# rt1060r1.net
KiCad netlist of a schematic drawn in EAGLE
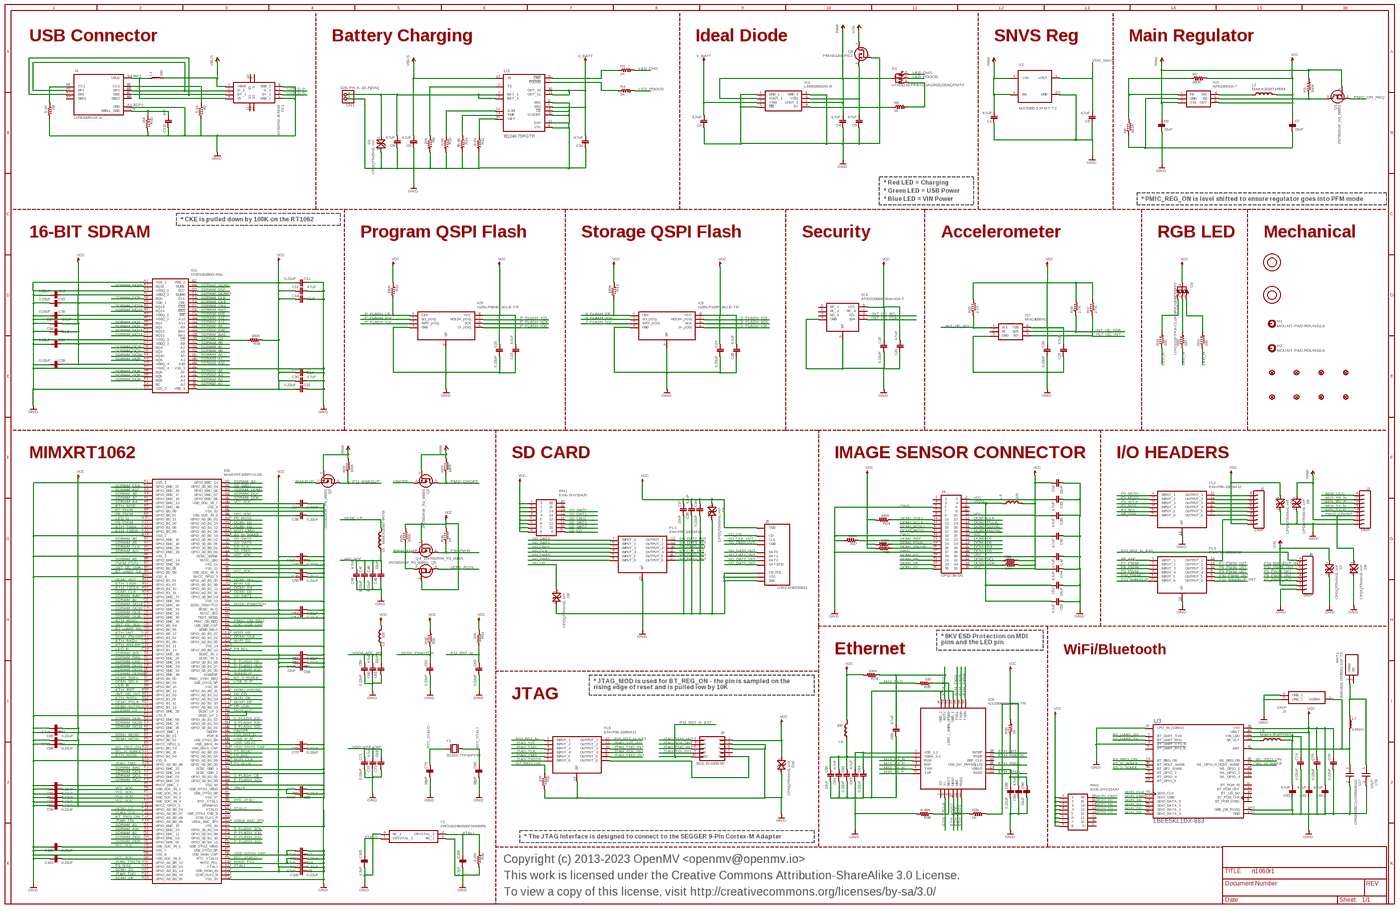
[diagram p0: schematic, sheet 1, overview]
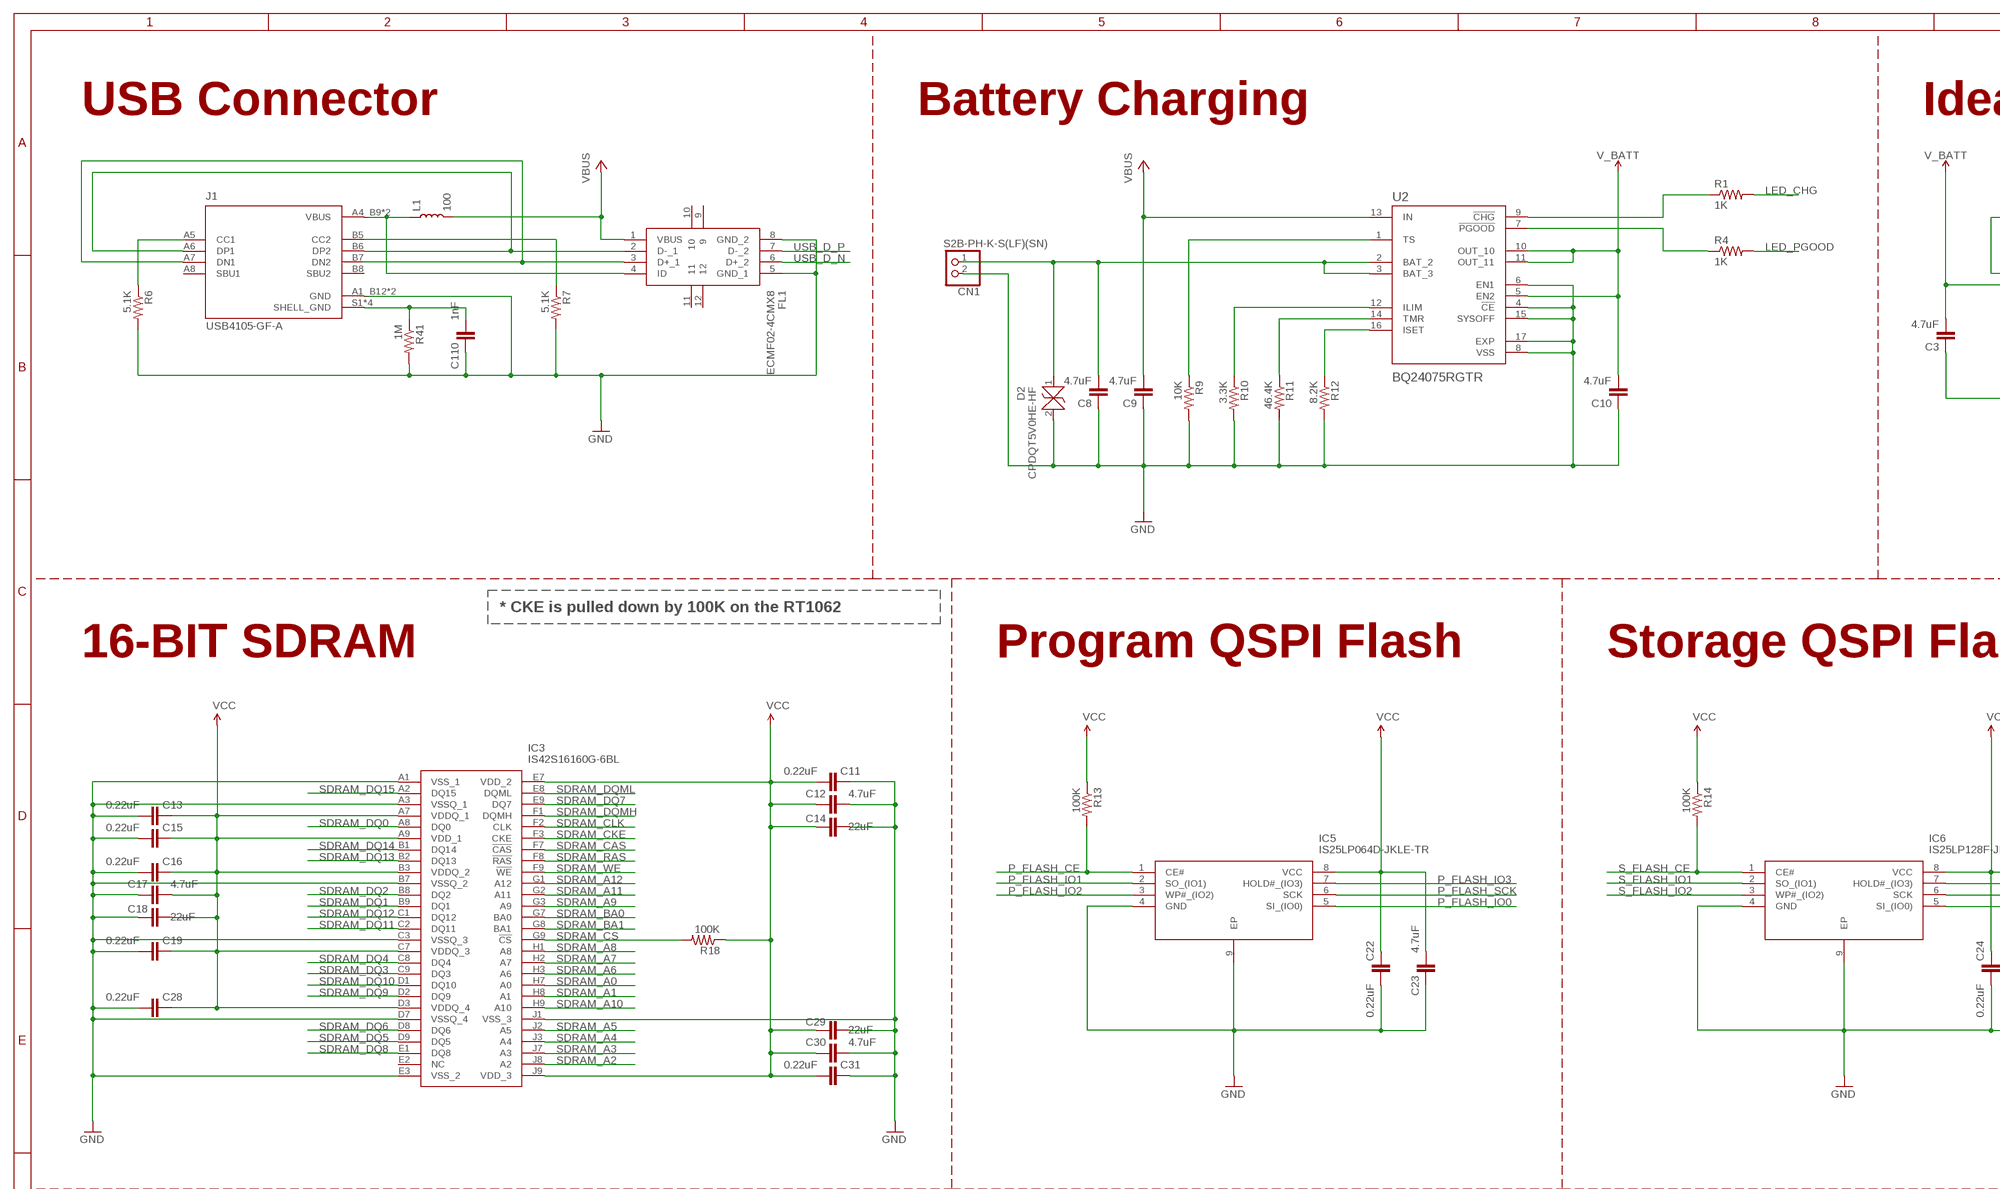
[diagram p1: schematic, sheet 1, part 1 of 4]
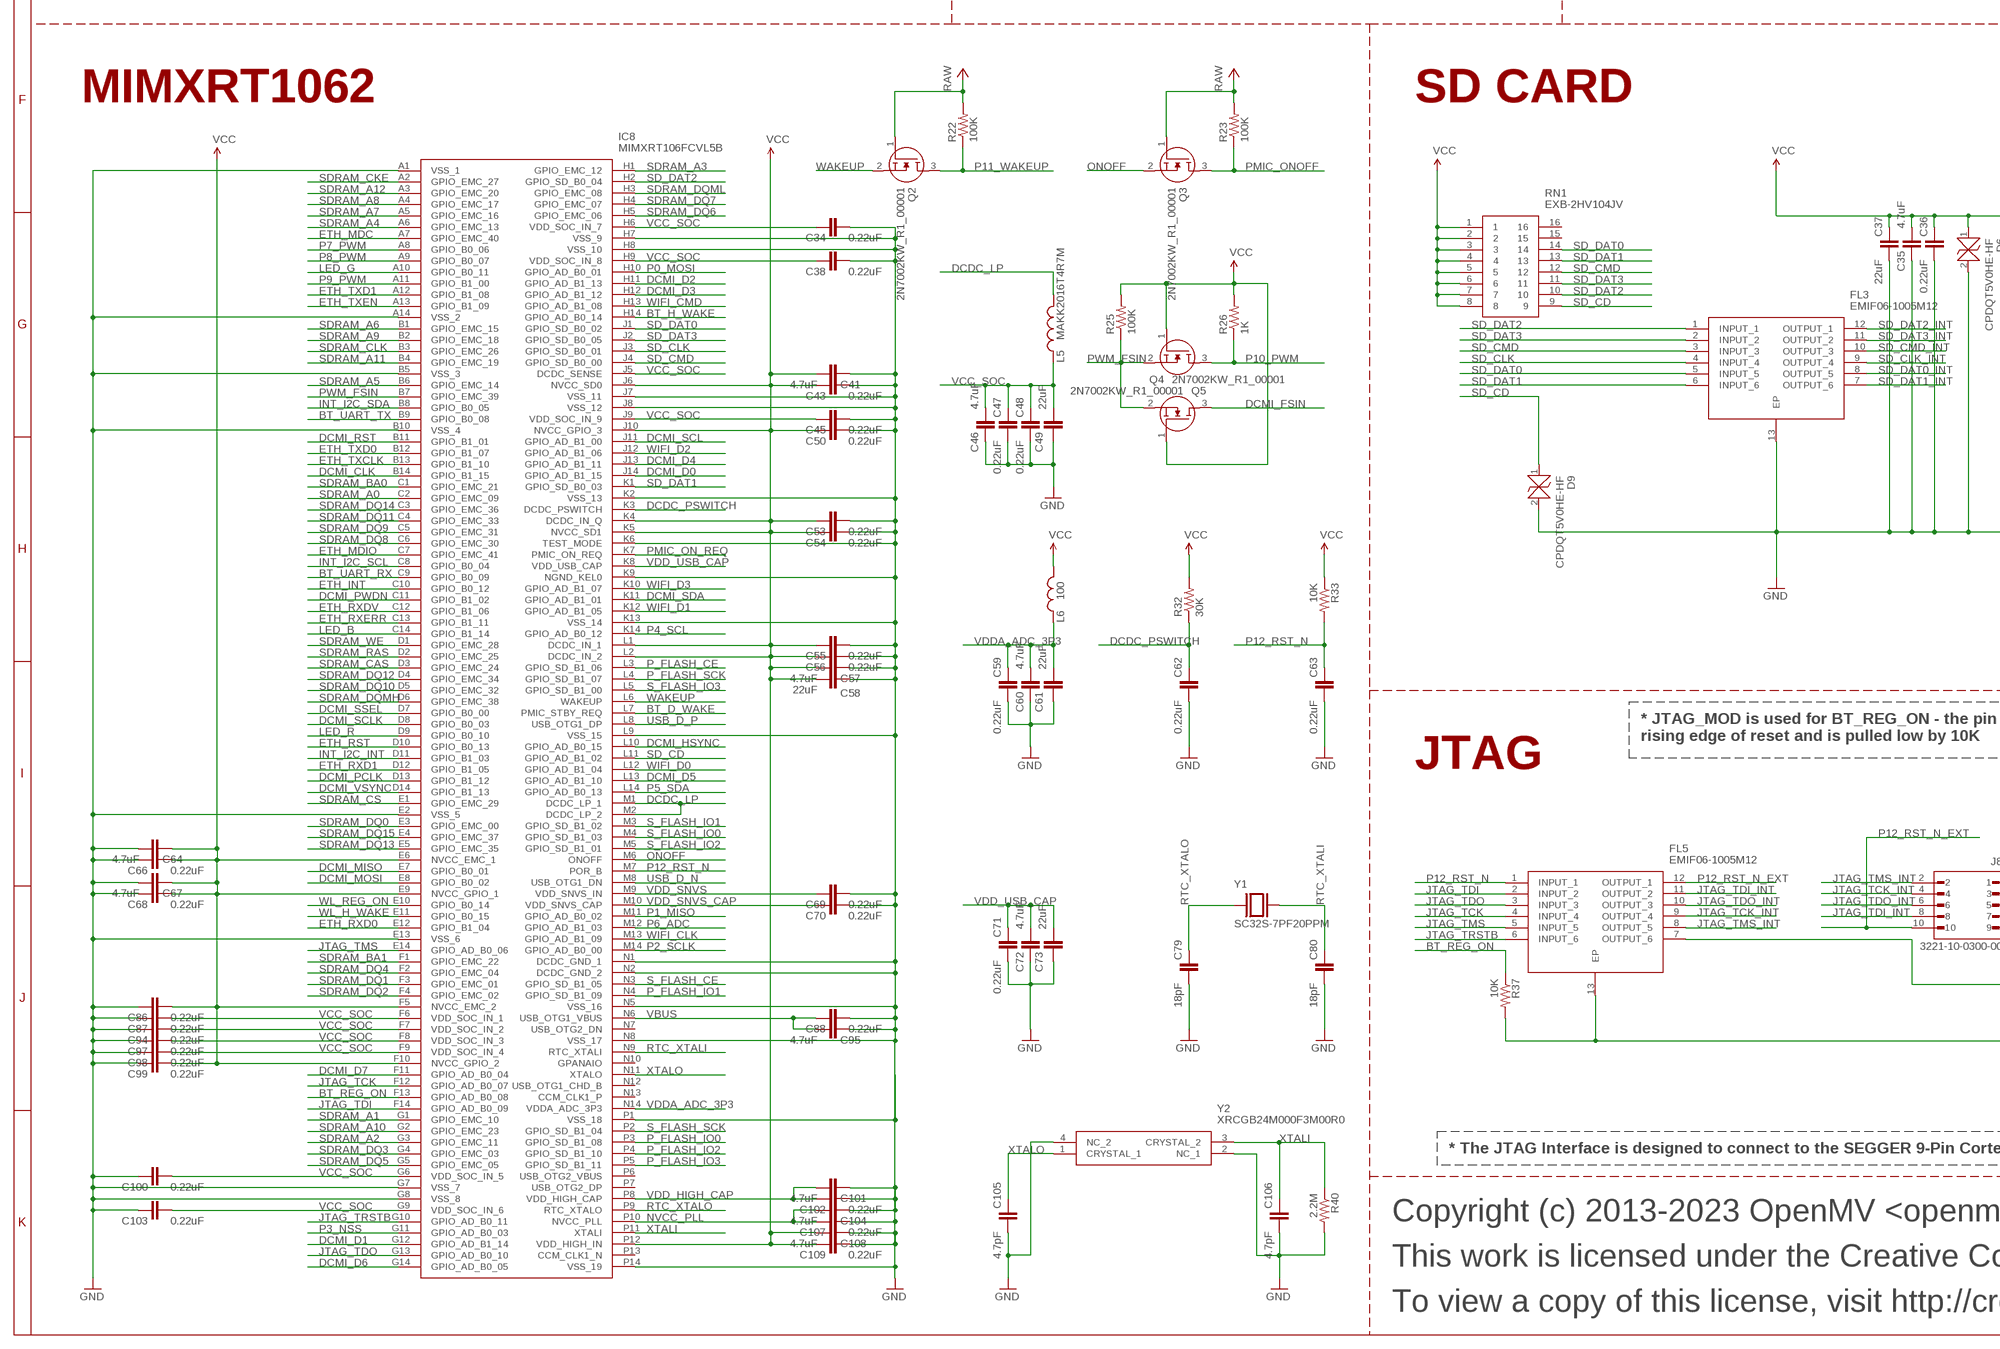
[diagram p2: schematic, sheet 1, part 2 of 4]
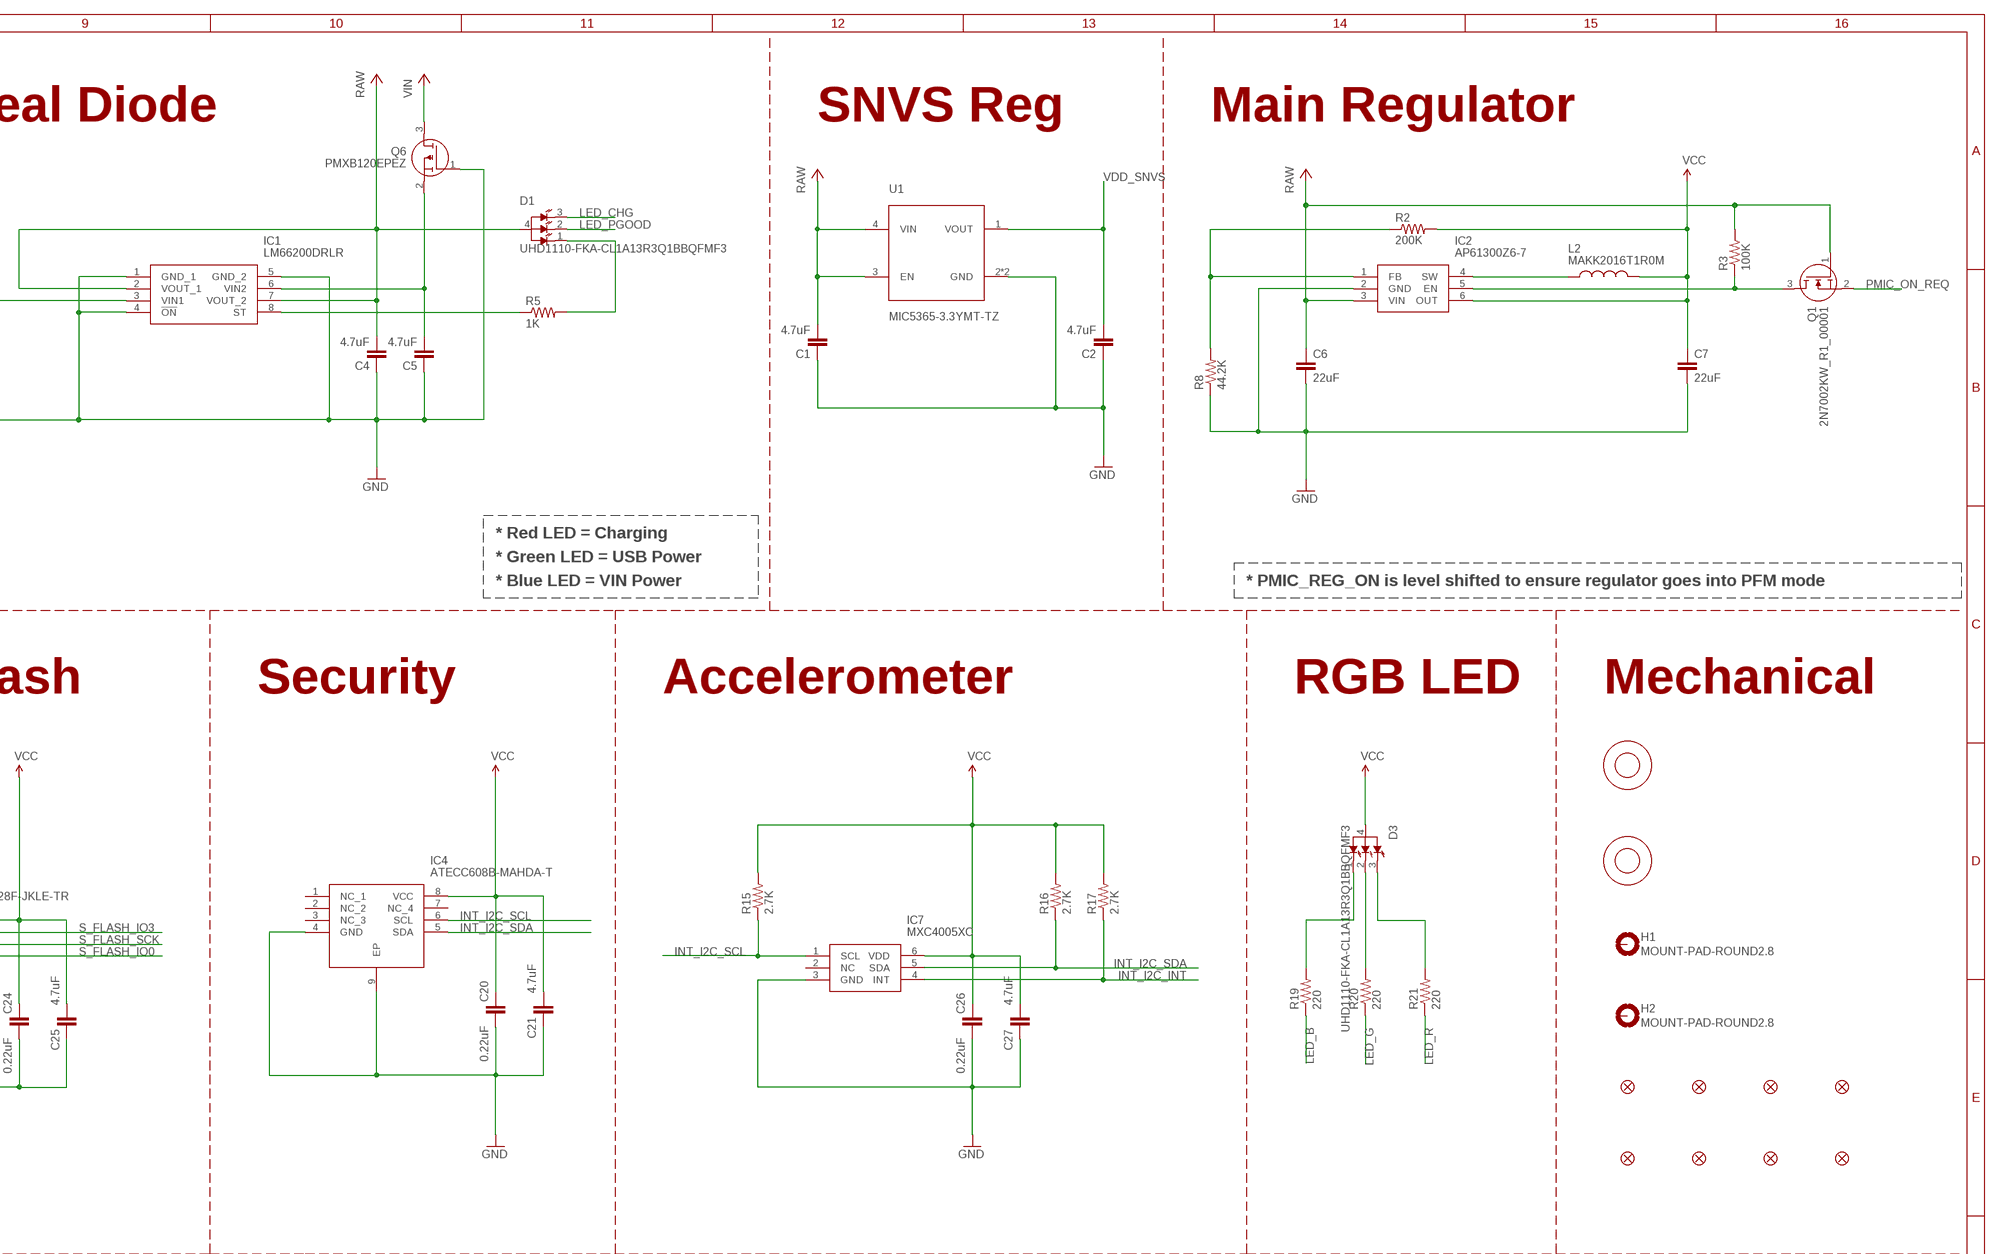
[diagram p3: schematic, sheet 1, part 3 of 4]
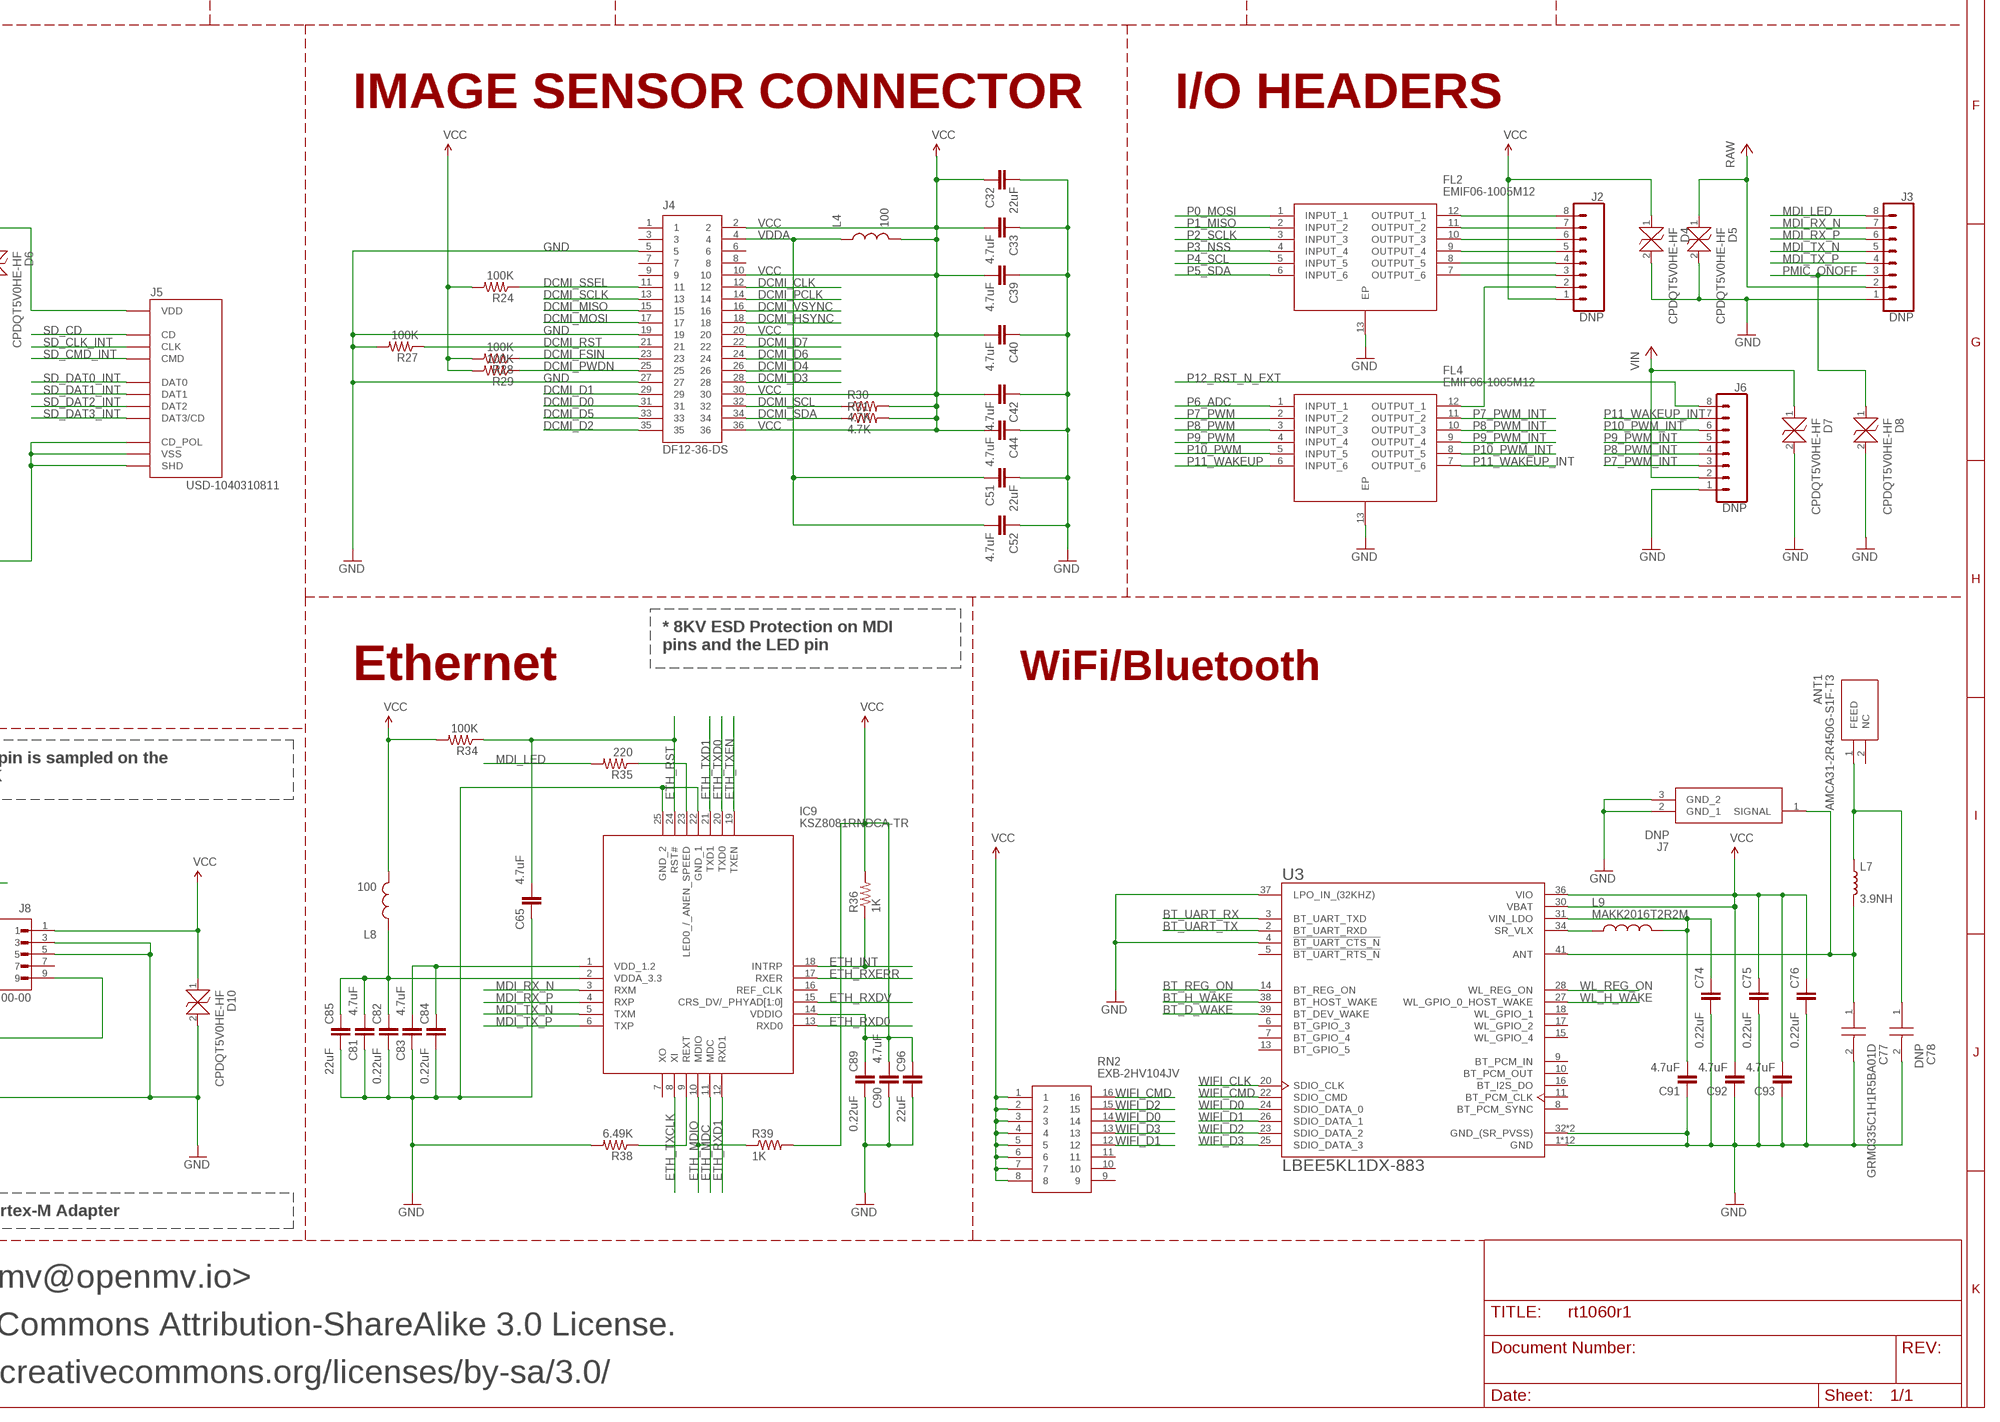
[diagram p4: schematic, sheet 1, part 4 of 4]

(export (version "E")
  (design (tool "Eeschema 10.0.6"))
  (components
    (comp (ref "ANT1")
      (value "AMCA31-2R450G-S1F-T3")
      (footprint "eagle-import:ANTC3216X140N")
      (fields (field (name "MOUSER_PART_NUMBER") "815-CA312R450GS1FT3"))
      (libsource (lib "eagle-import") (part "AMCA31-2R450G-S1F-T3"))
    )
    (comp (ref "C1")
      (value "4.7uF")
      (footprint "eagle-import:0402-CAP")
      (fields (field (name "MPN") "JMK105BBJ475MV-F"))
      (libsource (lib "eagle-import") (part "CAP0402-CAP"))
    )
    (comp (ref "C2")
      (value "4.7uF")
      (footprint "eagle-import:0402-CAP")
      (fields (field (name "MPN") "JMK105BBJ475MV-F"))
      (libsource (lib "eagle-import") (part "CAP0402-CAP"))
    )
    (comp (ref "C3")
      (value "4.7uF")
      (footprint "eagle-import:0402-CAP")
      (fields (field (name "MPN") "JMK105BBJ475MV-F"))
      (libsource (lib "eagle-import") (part "CAP0402-CAP"))
    )
    (comp (ref "C4")
      (value "4.7uF")
      (footprint "eagle-import:0402-CAP")
      (fields (field (name "MPN") "JMK105BBJ475MV-F"))
      (libsource (lib "eagle-import") (part "CAP0402-CAP"))
    )
    (comp (ref "C5")
      (value "4.7uF")
      (footprint "eagle-import:0402-CAP")
      (fields (field (name "MPN") "JMK105BBJ475MV-F"))
      (libsource (lib "eagle-import") (part "CAP0402-CAP"))
    )
    (comp (ref "C6")
      (value "22uF")
      (footprint "eagle-import:0805")
      (fields (field (name "MPN") "CL21A226MQQNNNE"))
      (libsource (lib "eagle-import") (part "22UF-0805-6.3V-20%"))
    )
    (comp (ref "C7")
      (value "22uF")
      (footprint "eagle-import:0805")
      (fields (field (name "MPN") "CL21A226MQQNNNE"))
      (libsource (lib "eagle-import") (part "22UF-0805-6.3V-20%"))
    )
    (comp (ref "C8")
      (value "4.7uF")
      (footprint "eagle-import:0402-CAP")
      (fields (field (name "MPN") "JMK105BBJ475MV-F"))
      (libsource (lib "eagle-import") (part "CAP0402-CAP"))
    )
    (comp (ref "C9")
      (value "4.7uF")
      (footprint "eagle-import:0402-CAP")
      (fields (field (name "MPN") "JMK105BBJ475MV-F"))
      (libsource (lib "eagle-import") (part "CAP0402-CAP"))
    )
    (comp (ref "C10")
      (value "4.7uF")
      (footprint "eagle-import:0402-CAP")
      (fields (field (name "MPN") "JMK105BBJ475MV-F"))
      (libsource (lib "eagle-import") (part "CAP0402-CAP"))
    )
    (comp (ref "C11")
      (value "0.22uF")
      (footprint "eagle-import:C0201")
      (fields (field (name "MPN") "GRM033R60J224ME15D"))
      (libsource (lib "eagle-import") (part "C-EUC0201"))
    )
    (comp (ref "C12")
      (value "4.7uF")
      (footprint "eagle-import:0402-CAP")
      (fields (field (name "MPN") "JMK105BBJ475MV-F"))
      (libsource (lib "eagle-import") (part "CAP0402-CAP"))
    )
    (comp (ref "C13")
      (value "0.22uF")
      (footprint "eagle-import:C0201")
      (fields (field (name "MPN") "GRM033R60J224ME15D"))
      (libsource (lib "eagle-import") (part "C-EUC0201"))
    )
    (comp (ref "C14")
      (value "22uF")
      (footprint "eagle-import:0805")
      (fields (field (name "MPN") "CL21A226MQQNNNE"))
      (libsource (lib "eagle-import") (part "22UF-0805-6.3V-20%"))
    )
    (comp (ref "C15")
      (value "0.22uF")
      (footprint "eagle-import:C0201")
      (fields (field (name "MPN") "GRM033R60J224ME15D"))
      (libsource (lib "eagle-import") (part "C-EUC0201"))
    )
    (comp (ref "C16")
      (value "0.22uF")
      (footprint "eagle-import:C0201")
      (fields (field (name "MPN") "GRM033R60J224ME15D"))
      (libsource (lib "eagle-import") (part "C-EUC0201"))
    )
    (comp (ref "C17")
      (value "4.7uF")
      (footprint "eagle-import:0402-CAP")
      (fields (field (name "MPN") "JMK105BBJ475MV-F"))
      (libsource (lib "eagle-import") (part "CAP0402-CAP"))
    )
    (comp (ref "C18")
      (value "22uF")
      (footprint "eagle-import:0805")
      (fields (field (name "MPN") "CL21A226MQQNNNE"))
      (libsource (lib "eagle-import") (part "22UF-0805-6.3V-20%"))
    )
    (comp (ref "C19")
      (value "0.22uF")
      (footprint "eagle-import:C0201")
      (fields (field (name "MPN") "GRM033R60J224ME15D"))
      (libsource (lib "eagle-import") (part "C-EUC0201"))
    )
    (comp (ref "C20")
      (value "0.22uF")
      (footprint "eagle-import:C0201")
      (fields (field (name "MPN") "GRM033R60J224ME15D"))
      (libsource (lib "eagle-import") (part "C-EUC0201"))
    )
    (comp (ref "C21")
      (value "4.7uF")
      (footprint "eagle-import:0402-CAP")
      (fields (field (name "MPN") "JMK105BBJ475MV-F"))
      (libsource (lib "eagle-import") (part "CAP0402-CAP"))
    )
    (comp (ref "C22")
      (value "0.22uF")
      (footprint "eagle-import:C0201")
      (fields (field (name "MPN") "GRM033R60J224ME15D"))
      (libsource (lib "eagle-import") (part "C-EUC0201"))
    )
    (comp (ref "C23")
      (value "4.7uF")
      (footprint "eagle-import:0402-CAP")
      (fields (field (name "MPN") "JMK105BBJ475MV-F"))
      (libsource (lib "eagle-import") (part "CAP0402-CAP"))
    )
    (comp (ref "C24")
      (value "0.22uF")
      (footprint "eagle-import:C0201")
      (fields (field (name "MPN") "GRM033R60J224ME15D"))
      (libsource (lib "eagle-import") (part "C-EUC0201"))
    )
    (comp (ref "C25")
      (value "4.7uF")
      (footprint "eagle-import:0402-CAP")
      (fields (field (name "MPN") "JMK105BBJ475MV-F"))
      (libsource (lib "eagle-import") (part "CAP0402-CAP"))
    )
    (comp (ref "C26")
      (value "0.22uF")
      (footprint "eagle-import:C0201")
      (fields (field (name "MPN") "GRM033R60J224ME15D"))
      (libsource (lib "eagle-import") (part "C-EUC0201"))
    )
    (comp (ref "C27")
      (value "4.7uF")
      (footprint "eagle-import:0402-CAP")
      (fields (field (name "MPN") "JMK105BBJ475MV-F"))
      (libsource (lib "eagle-import") (part "CAP0402-CAP"))
    )
    (comp (ref "C28")
      (value "0.22uF")
      (footprint "eagle-import:C0201")
      (fields (field (name "MPN") "GRM033R60J224ME15D"))
      (libsource (lib "eagle-import") (part "C-EUC0201"))
    )
    (comp (ref "C29")
      (value "22uF")
      (footprint "eagle-import:0805")
      (fields (field (name "MPN") "CL21A226MQQNNNE"))
      (libsource (lib "eagle-import") (part "22UF-0805-6.3V-20%"))
    )
    (comp (ref "C30")
      (value "4.7uF")
      (footprint "eagle-import:0402-CAP")
      (fields (field (name "MPN") "JMK105BBJ475MV-F"))
      (libsource (lib "eagle-import") (part "CAP0402-CAP"))
    )
    (comp (ref "C31")
      (value "0.22uF")
      (footprint "eagle-import:C0201")
      (fields (field (name "MPN") "GRM033R60J224ME15D"))
      (libsource (lib "eagle-import") (part "C-EUC0201"))
    )
    (comp (ref "C32")
      (value "22uF")
      (footprint "eagle-import:0805")
      (fields (field (name "MPN") "CL21A226MQQNNNE"))
      (libsource (lib "eagle-import") (part "22UF-0805-6.3V-20%"))
    )
    (comp (ref "C33")
      (value "4.7uF")
      (footprint "eagle-import:0402-CAP")
      (fields (field (name "MPN") "JMK105BBJ475MV-F"))
      (libsource (lib "eagle-import") (part "CAP0402-CAP"))
    )
    (comp (ref "C34")
      (value "0.22uF")
      (footprint "eagle-import:C0201")
      (fields (field (name "MPN") "GRM033R60J224ME15D"))
      (libsource (lib "eagle-import") (part "C-EUC0201"))
    )
    (comp (ref "C35")
      (value "4.7uF")
      (footprint "eagle-import:0402-CAP")
      (fields (field (name "MPN") "JMK105BBJ475MV-F"))
      (libsource (lib "eagle-import") (part "CAP0402-CAP"))
    )
    (comp (ref "C36")
      (value "0.22uF")
      (footprint "eagle-import:C0201")
      (fields (field (name "MPN") "GRM033R60J224ME15D"))
      (libsource (lib "eagle-import") (part "C-EUC0201"))
    )
    (comp (ref "C37")
      (value "22uF")
      (footprint "eagle-import:0805")
      (fields (field (name "MPN") "CL21A226MQQNNNE"))
      (libsource (lib "eagle-import") (part "22UF-0805-6.3V-20%"))
    )
    (comp (ref "C38")
      (value "0.22uF")
      (footprint "eagle-import:C0201")
      (fields (field (name "MPN") "GRM033R60J224ME15D"))
      (libsource (lib "eagle-import") (part "C-EUC0201"))
    )
    (comp (ref "C39")
      (value "4.7uF")
      (footprint "eagle-import:0402-CAP")
      (fields (field (name "MPN") "JMK105BBJ475MV-F"))
      (libsource (lib "eagle-import") (part "CAP0402-CAP"))
    )
    (comp (ref "C40")
      (value "4.7uF")
      (footprint "eagle-import:0402-CAP")
      (fields (field (name "MPN") "JMK105BBJ475MV-F"))
      (libsource (lib "eagle-import") (part "CAP0402-CAP"))
    )
    (comp (ref "C41")
      (value "4.7uF")
      (footprint "eagle-import:0402-CAP")
      (fields (field (name "MPN") "JMK105BBJ475MV-F"))
      (libsource (lib "eagle-import") (part "CAP0402-CAP"))
    )
    (comp (ref "C42")
      (value "4.7uF")
      (footprint "eagle-import:0402-CAP")
      (fields (field (name "MPN") "JMK105BBJ475MV-F"))
      (libsource (lib "eagle-import") (part "CAP0402-CAP"))
    )
    (comp (ref "C43")
      (value "0.22uF")
      (footprint "eagle-import:C0201")
      (fields (field (name "MPN") "GRM033R60J224ME15D"))
      (libsource (lib "eagle-import") (part "C-EUC0201"))
    )
    (comp (ref "C44")
      (value "4.7uF")
      (footprint "eagle-import:0402-CAP")
      (fields (field (name "MPN") "JMK105BBJ475MV-F"))
      (libsource (lib "eagle-import") (part "CAP0402-CAP"))
    )
    (comp (ref "C45")
      (value "0.22uF")
      (footprint "eagle-import:C0201")
      (fields (field (name "MPN") "GRM033R60J224ME15D"))
      (libsource (lib "eagle-import") (part "C-EUC0201"))
    )
    (comp (ref "C46")
      (value "4.7uF")
      (footprint "eagle-import:0402-CAP")
      (fields (field (name "MPN") "JMK105BBJ475MV-F"))
      (libsource (lib "eagle-import") (part "CAP0402-CAP"))
    )
    (comp (ref "C47")
      (value "0.22uF")
      (footprint "eagle-import:C0201")
      (fields (field (name "MPN") "GRM033R60J224ME15D"))
      (libsource (lib "eagle-import") (part "C-EUC0201"))
    )
    (comp (ref "C48")
      (value "0.22uF")
      (footprint "eagle-import:C0201")
      (fields (field (name "MPN") "GRM033R60J224ME15D"))
      (libsource (lib "eagle-import") (part "C-EUC0201"))
    )
    (comp (ref "C49")
      (value "22uF")
      (footprint "eagle-import:0805")
      (fields (field (name "MPN") "CL21A226MQQNNNE"))
      (libsource (lib "eagle-import") (part "22UF-0805-6.3V-20%"))
    )
    (comp (ref "C50")
      (value "0.22uF")
      (footprint "eagle-import:C0201")
      (fields (field (name "MPN") "GRM033R60J224ME15D"))
      (libsource (lib "eagle-import") (part "C-EUC0201"))
    )
    (comp (ref "C51")
      (value "22uF")
      (footprint "eagle-import:0805")
      (fields (field (name "MPN") "CL21A226MQQNNNE"))
      (libsource (lib "eagle-import") (part "22UF-0805-6.3V-20%"))
    )
    (comp (ref "C52")
      (value "4.7uF")
      (footprint "eagle-import:0402-CAP")
      (fields (field (name "MPN") "JMK105BBJ475MV-F"))
      (libsource (lib "eagle-import") (part "CAP0402-CAP"))
    )
    (comp (ref "C53")
      (value "0.22uF")
      (footprint "eagle-import:C0201")
      (fields (field (name "MPN") "GRM033R60J224ME15D"))
      (libsource (lib "eagle-import") (part "C-EUC0201"))
    )
    (comp (ref "C54")
      (value "0.22uF")
      (footprint "eagle-import:C0201")
      (fields (field (name "MPN") "GRM033R60J224ME15D"))
      (libsource (lib "eagle-import") (part "C-EUC0201"))
    )
    (comp (ref "C55")
      (value "0.22uF")
      (footprint "eagle-import:C0201")
      (fields (field (name "MPN") "GRM033R60J224ME15D"))
      (libsource (lib "eagle-import") (part "C-EUC0201"))
    )
    (comp (ref "C56")
      (value "0.22uF")
      (footprint "eagle-import:C0201")
      (fields (field (name "MPN") "GRM033R60J224ME15D"))
      (libsource (lib "eagle-import") (part "C-EUC0201"))
    )
    (comp (ref "C57")
      (value "4.7uF")
      (footprint "eagle-import:0402-CAP")
      (fields (field (name "MPN") "JMK105BBJ475MV-F"))
      (libsource (lib "eagle-import") (part "CAP0402-CAP"))
    )
    (comp (ref "C58")
      (value "22uF")
      (footprint "eagle-import:0805")
      (fields (field (name "MPN") "CL21A226MQQNNNE"))
      (libsource (lib "eagle-import") (part "22UF-0805-6.3V-20%"))
    )
    (comp (ref "C59")
      (value "0.22uF")
      (footprint "eagle-import:C0201")
      (fields (field (name "MPN") "GRM033R60J224ME15D"))
      (libsource (lib "eagle-import") (part "C-EUC0201"))
    )
    (comp (ref "C60")
      (value "4.7uF")
      (footprint "eagle-import:0402-CAP")
      (fields (field (name "MPN") "JMK105BBJ475MV-F"))
      (libsource (lib "eagle-import") (part "CAP0402-CAP"))
    )
    (comp (ref "C61")
      (value "22uF")
      (footprint "eagle-import:0805")
      (fields (field (name "MPN") "CL21A226MQQNNNE"))
      (libsource (lib "eagle-import") (part "22UF-0805-6.3V-20%"))
    )
    (comp (ref "C62")
      (value "0.22uF")
      (footprint "eagle-import:C0201")
      (fields (field (name "MPN") "GRM033R60J224ME15D"))
      (libsource (lib "eagle-import") (part "C-EUC0201"))
    )
    (comp (ref "C63")
      (value "0.22uF")
      (footprint "eagle-import:C0201")
      (fields (field (name "MPN") "GRM033R60J224ME15D"))
      (libsource (lib "eagle-import") (part "C-EUC0201"))
    )
    (comp (ref "C64")
      (value "4.7uF")
      (footprint "eagle-import:0402-CAP")
      (fields (field (name "MPN") "JMK105BBJ475MV-F"))
      (libsource (lib "eagle-import") (part "CAP0402-CAP"))
    )
    (comp (ref "C65")
      (value "4.7uF")
      (footprint "eagle-import:0402-CAP")
      (fields (field (name "MPN") "JMK105BBJ475MV-F"))
      (libsource (lib "eagle-import") (part "CAP0402-CAP"))
    )
    (comp (ref "C66")
      (value "0.22uF")
      (footprint "eagle-import:C0201")
      (fields (field (name "MPN") "GRM033R60J224ME15D"))
      (libsource (lib "eagle-import") (part "C-EUC0201"))
    )
    (comp (ref "C67")
      (value "4.7uF")
      (footprint "eagle-import:0402-CAP")
      (fields (field (name "MPN") "JMK105BBJ475MV-F"))
      (libsource (lib "eagle-import") (part "CAP0402-CAP"))
    )
    (comp (ref "C68")
      (value "0.22uF")
      (footprint "eagle-import:C0201")
      (fields (field (name "MPN") "GRM033R60J224ME15D"))
      (libsource (lib "eagle-import") (part "C-EUC0201"))
    )
    (comp (ref "C69")
      (value "0.22uF")
      (footprint "eagle-import:C0201")
      (fields (field (name "MPN") "GRM033R60J224ME15D"))
      (libsource (lib "eagle-import") (part "C-EUC0201"))
    )
    (comp (ref "C70")
      (value "0.22uF")
      (footprint "eagle-import:C0201")
      (fields (field (name "MPN") "GRM033R60J224ME15D"))
      (libsource (lib "eagle-import") (part "C-EUC0201"))
    )
    (comp (ref "C71")
      (value "0.22uF")
      (footprint "eagle-import:C0201")
      (fields (field (name "MPN") "GRM033R60J224ME15D"))
      (libsource (lib "eagle-import") (part "C-EUC0201"))
    )
    (comp (ref "C72")
      (value "4.7uF")
      (footprint "eagle-import:0402-CAP")
      (fields (field (name "MPN") "JMK105BBJ475MV-F"))
      (libsource (lib "eagle-import") (part "CAP0402-CAP"))
    )
    (comp (ref "C73")
      (value "22uF")
      (footprint "eagle-import:0805")
      (fields (field (name "MPN") "CL21A226MQQNNNE"))
      (libsource (lib "eagle-import") (part "22UF-0805-6.3V-20%"))
    )
    (comp (ref "C74")
      (value "0.22uF")
      (footprint "eagle-import:C0201")
      (fields (field (name "MPN") "GRM033R60J224ME15D"))
      (libsource (lib "eagle-import") (part "C-EUC0201"))
    )
    (comp (ref "C75")
      (value "0.22uF")
      (footprint "eagle-import:C0201")
      (fields (field (name "MPN") "GRM033R60J224ME15D"))
      (libsource (lib "eagle-import") (part "C-EUC0201"))
    )
    (comp (ref "C76")
      (value "0.22uF")
      (footprint "eagle-import:C0201")
      (fields (field (name "MPN") "GRM033R60J224ME15D"))
      (libsource (lib "eagle-import") (part "C-EUC0201"))
    )
    (comp (ref "C77")
      (value "GRM0335C1H1R5BA01D")
      (footprint "eagle-import:CAPC0603X33N")
      (fields (field (name "MOUSER_PART_NUMBER") "81-GRM0335C1H1R5BA1D"))
      (libsource (lib "eagle-import") (part "GRM0335C1H1R5BA01D"))
    )
    (comp (ref "C78")
      (value "DNP")
      (footprint "eagle-import:CAPC0603X33N")
      (fields
        (field (name "MANUFACTURER_PART_NUMBER") "GRM0335C1H1R5BA01D")
        (field (name "MOUSER_PART_NUMBER") "81-GRM0335C1H1R5BA1D")
      )
      (libsource (lib "eagle-import") (part "GRM0335C1H1R5BA01D"))
    )
    (comp (ref "C79")
      (value "18pF")
      (footprint "eagle-import:C0201")
      (fields (field (name "MPN") "GRM0335C1E180JA01D"))
      (libsource (lib "eagle-import") (part "C-EUC0201"))
    )
    (comp (ref "C80")
      (value "18pF")
      (footprint "eagle-import:C0201")
      (fields (field (name "MPN") "GRM0335C1E180JA01D"))
      (libsource (lib "eagle-import") (part "C-EUC0201"))
    )
    (comp (ref "C81")
      (value "4.7uF")
      (footprint "eagle-import:0402-CAP")
      (fields (field (name "MPN") "JMK105BBJ475MV-F"))
      (libsource (lib "eagle-import") (part "CAP0402-CAP"))
    )
    (comp (ref "C82")
      (value "0.22uF")
      (footprint "eagle-import:C0201")
      (fields (field (name "MPN") "GRM033R60J224ME15D"))
      (libsource (lib "eagle-import") (part "C-EUC0201"))
    )
    (comp (ref "C83")
      (value "4.7uF")
      (footprint "eagle-import:0402-CAP")
      (fields (field (name "MPN") "JMK105BBJ475MV-F"))
      (libsource (lib "eagle-import") (part "CAP0402-CAP"))
    )
    (comp (ref "C84")
      (value "0.22uF")
      (footprint "eagle-import:C0201")
      (fields (field (name "MPN") "GRM033R60J224ME15D"))
      (libsource (lib "eagle-import") (part "C-EUC0201"))
    )
    (comp (ref "C85")
      (value "22uF")
      (footprint "eagle-import:0805")
      (fields (field (name "MPN") "CL21A226MQQNNNE"))
      (libsource (lib "eagle-import") (part "22UF-0805-6.3V-20%"))
    )
    (comp (ref "C86")
      (value "0.22uF")
      (footprint "eagle-import:C0201")
      (fields (field (name "MPN") "GRM033R60J224ME15D"))
      (libsource (lib "eagle-import") (part "C-EUC0201"))
    )
    (comp (ref "C87")
      (value "0.22uF")
      (footprint "eagle-import:C0201")
      (fields (field (name "MPN") "GRM033R60J224ME15D"))
      (libsource (lib "eagle-import") (part "C-EUC0201"))
    )
    (comp (ref "C88")
      (value "0.22uF")
      (footprint "eagle-import:C0201")
      (fields (field (name "MPN") "GRM033R60J224ME15D"))
      (libsource (lib "eagle-import") (part "C-EUC0201"))
    )
    (comp (ref "C89")
      (value "0.22uF")
      (footprint "eagle-import:C0201")
      (fields (field (name "MPN") "GRM033R60J224ME15D"))
      (libsource (lib "eagle-import") (part "C-EUC0201"))
    )
    (comp (ref "C90")
      (value "4.7uF")
      (footprint "eagle-import:0402-CAP")
      (fields (field (name "MPN") "JMK105BBJ475MV-F"))
      (libsource (lib "eagle-import") (part "CAP0402-CAP"))
    )
    (comp (ref "C91")
      (value "4.7uF")
      (footprint "eagle-import:0402-CAP")
      (fields (field (name "MPN") "JMK105BBJ475MV-F"))
      (libsource (lib "eagle-import") (part "CAP0402-CAP"))
    )
    (comp (ref "C92")
      (value "4.7uF")
      (footprint "eagle-import:0402-CAP")
      (fields (field (name "MPN") "JMK105BBJ475MV-F"))
      (libsource (lib "eagle-import") (part "CAP0402-CAP"))
    )
    (comp (ref "C93")
      (value "4.7uF")
      (footprint "eagle-import:0402-CAP")
      (fields (field (name "MPN") "JMK105BBJ475MV-F"))
      (libsource (lib "eagle-import") (part "CAP0402-CAP"))
    )
    (comp (ref "C94")
      (value "0.22uF")
      (footprint "eagle-import:C0201")
      (fields (field (name "MPN") "GRM033R60J224ME15D"))
      (libsource (lib "eagle-import") (part "C-EUC0201"))
    )
    (comp (ref "C95")
      (value "4.7uF")
      (footprint "eagle-import:0402-CAP")
      (fields (field (name "MPN") "JMK105BBJ475MV-F"))
      (libsource (lib "eagle-import") (part "CAP0402-CAP"))
    )
    (comp (ref "C96")
      (value "22uF")
      (footprint "eagle-import:0805")
      (fields (field (name "MPN") "CL21A226MQQNNNE"))
      (libsource (lib "eagle-import") (part "22UF-0805-6.3V-20%"))
    )
    (comp (ref "C97")
      (value "0.22uF")
      (footprint "eagle-import:C0201")
      (fields (field (name "MPN") "GRM033R60J224ME15D"))
      (libsource (lib "eagle-import") (part "C-EUC0201"))
    )
    (comp (ref "C98")
      (value "0.22uF")
      (footprint "eagle-import:C0201")
      (fields (field (name "MPN") "GRM033R60J224ME15D"))
      (libsource (lib "eagle-import") (part "C-EUC0201"))
    )
    (comp (ref "C99")
      (value "0.22uF")
      (footprint "eagle-import:C0201")
      (fields (field (name "MPN") "GRM033R60J224ME15D"))
      (libsource (lib "eagle-import") (part "C-EUC0201"))
    )
    (comp (ref "C100")
      (value "0.22uF")
      (footprint "eagle-import:C0201")
      (fields (field (name "MPN") "GRM033R60J224ME15D"))
      (libsource (lib "eagle-import") (part "C-EUC0201"))
    )
    (comp (ref "C101")
      (value "4.7uF")
      (footprint "eagle-import:0402-CAP")
      (fields (field (name "MPN") "JMK105BBJ475MV-F"))
      (libsource (lib "eagle-import") (part "CAP0402-CAP"))
    )
    (comp (ref "C102")
      (value "0.22uF")
      (footprint "eagle-import:C0201")
      (fields (field (name "MPN") "GRM033R60J224ME15D"))
      (libsource (lib "eagle-import") (part "C-EUC0201"))
    )
    (comp (ref "C103")
      (value "0.22uF")
      (footprint "eagle-import:C0201")
      (fields (field (name "MPN") "GRM033R60J224ME15D"))
      (libsource (lib "eagle-import") (part "C-EUC0201"))
    )
    (comp (ref "C104")
      (value "4.7uF")
      (footprint "eagle-import:0402-CAP")
      (fields (field (name "MPN") "JMK105BBJ475MV-F"))
      (libsource (lib "eagle-import") (part "CAP0402-CAP"))
    )
    (comp (ref "C105")
      (value "4.7pF")
      (footprint "eagle-import:C0201")
      (fields (field (name "MPN") "GRM0335C1E4R7CA01D"))
      (libsource (lib "eagle-import") (part "C-EUC0201"))
    )
    (comp (ref "C106")
      (value "4.7pF")
      (footprint "eagle-import:C0201")
      (fields (field (name "MPN") "GRM0335C1E4R7CA01D"))
      (libsource (lib "eagle-import") (part "C-EUC0201"))
    )
    (comp (ref "C107")
      (value "0.22uF")
      (footprint "eagle-import:C0201")
      (fields (field (name "MPN") "GRM033R60J224ME15D"))
      (libsource (lib "eagle-import") (part "C-EUC0201"))
    )
    (comp (ref "C108")
      (value "4.7uF")
      (footprint "eagle-import:0402-CAP")
      (fields (field (name "MPN") "JMK105BBJ475MV-F"))
      (libsource (lib "eagle-import") (part "CAP0402-CAP"))
    )
    (comp (ref "C109")
      (value "0.22uF")
      (footprint "eagle-import:C0201")
      (fields (field (name "MPN") "GRM033R60J224ME15D"))
      (libsource (lib "eagle-import") (part "C-EUC0201"))
    )
    (comp (ref "C110")
      (value "1nF")
      (footprint "eagle-import:0402-CAP")
      (fields (field (name "MPN") "VJ0402Y102JXACW1BC"))
      (libsource (lib "eagle-import") (part "CAP0402-CAP"))
    )
    (comp (ref "CN1")
      (value "S2B-PH-K-S(LF)(SN)")
      (footprint "eagle-import:JST-PH-2-THM-RA")
      (libsource (lib "eagle-import") (part "JST_2PIN-THM-RA"))
    )
    (comp (ref "D1")
      (value "UHD1110-FKA-CL1A13R3Q1BBQFMF3")
      (footprint "eagle-import:LED_UHD1110-FKA-CL1A13R3Q1BBQFMF3")
      (fields (field (name "MF") "Cree Inc.") (field (name "MPN") "UHD1110-FKA-CL1A13r3q1BBQFMF3"))
      (libsource (lib "eagle-import") (part "UHD1110-FKA-CL1A13R3Q1BBQFMF3"))
    )
    (comp (ref "D2")
      (value "CPDQT5V0HE-HF")
      (footprint "eagle-import:CPDQT5V0HEHF")
      (libsource (lib "eagle-import") (part "CPDQT5V0HE-HF"))
    )
    (comp (ref "D3")
      (value "UHD1110-FKA-CL1A13R3Q1BBQFMF3")
      (footprint "eagle-import:LED_UHD1110-FKA-CL1A13R3Q1BBQFMF3")
      (fields (field (name "MF") "Cree Inc.") (field (name "MPN") "UHD1110-FKA-CL1A13r3q1BBQFMF3"))
      (libsource (lib "eagle-import") (part "UHD1110-FKA-CL1A13R3Q1BBQFMF3"))
    )
    (comp (ref "D4")
      (value "CPDQT5V0HE-HF")
      (footprint "eagle-import:CPDQT5V0HEHF")
      (libsource (lib "eagle-import") (part "CPDQT5V0HE-HF"))
    )
    (comp (ref "D5")
      (value "CPDQT5V0HE-HF")
      (footprint "eagle-import:CPDQT5V0HEHF")
      (libsource (lib "eagle-import") (part "CPDQT5V0HE-HF"))
    )
    (comp (ref "D6")
      (value "CPDQT5V0HE-HF")
      (footprint "eagle-import:CPDQT5V0HEHF")
      (libsource (lib "eagle-import") (part "CPDQT5V0HE-HF"))
    )
    (comp (ref "D7")
      (value "CPDQT5V0HE-HF")
      (footprint "eagle-import:CPDQT5V0HEHF")
      (libsource (lib "eagle-import") (part "CPDQT5V0HE-HF"))
    )
    (comp (ref "D8")
      (value "CPDQT5V0HE-HF")
      (footprint "eagle-import:CPDQT5V0HEHF")
      (libsource (lib "eagle-import") (part "CPDQT5V0HE-HF"))
    )
    (comp (ref "D9")
      (value "CPDQT5V0HE-HF")
      (footprint "eagle-import:CPDQT5V0HEHF")
      (libsource (lib "eagle-import") (part "CPDQT5V0HE-HF"))
    )
    (comp (ref "D10")
      (value "CPDQT5V0HE-HF")
      (footprint "eagle-import:CPDQT5V0HEHF")
      (libsource (lib "eagle-import") (part "CPDQT5V0HE-HF"))
    )
    (comp (ref "FD1")
      (value "FIDUCIAL1X2")
      (footprint "eagle-import:FIDUCIAL-1X2")
      (libsource (lib "eagle-import") (part "FIDUCIAL1X2"))
    )
    (comp (ref "FD2")
      (value "FIDUCIAL1X2")
      (footprint "eagle-import:FIDUCIAL-1X2")
      (libsource (lib "eagle-import") (part "FIDUCIAL1X2"))
    )
    (comp (ref "FD3")
      (value "FIDUCIAL1X2")
      (footprint "eagle-import:FIDUCIAL-1X2")
      (libsource (lib "eagle-import") (part "FIDUCIAL1X2"))
    )
    (comp (ref "FD4")
      (value "FIDUCIAL1X2")
      (footprint "eagle-import:FIDUCIAL-1X2")
      (libsource (lib "eagle-import") (part "FIDUCIAL1X2"))
    )
    (comp (ref "FD5")
      (value "FIDUCIAL1X2")
      (footprint "eagle-import:FIDUCIAL-1X2")
      (libsource (lib "eagle-import") (part "FIDUCIAL1X2"))
    )
    (comp (ref "FD6")
      (value "FIDUCIAL1X2")
      (footprint "eagle-import:FIDUCIAL-1X2")
      (libsource (lib "eagle-import") (part "FIDUCIAL1X2"))
    )
    (comp (ref "FD7")
      (value "FIDUCIAL1X2")
      (footprint "eagle-import:FIDUCIAL-1X2")
      (libsource (lib "eagle-import") (part "FIDUCIAL1X2"))
    )
    (comp (ref "FD8")
      (value "FIDUCIAL1X2")
      (footprint "eagle-import:FIDUCIAL-1X2")
      (libsource (lib "eagle-import") (part "FIDUCIAL1X2"))
    )
    (comp (ref "FL1")
      (value "ECMF02-4CMX8")
      (footprint "eagle-import:ECMF024CMX8")
      (fields (field (name "MOUSER_PART_NUMBER") "511-ECMF02-4CMX8"))
      (libsource (lib "eagle-import") (part "ECMF02-4CMX8"))
    )
    (comp (ref "FL2")
      (value "EMIF06-1005M12")
      (footprint "eagle-import:SON40P150X250X65-13N")
      (fields (field (name "MOUSER_PART_NUMBER") "511-EMIF06-1005M12"))
      (libsource (lib "eagle-import") (part "EMIF06-1005M12"))
    )
    (comp (ref "FL3")
      (value "EMIF06-1005M12")
      (footprint "eagle-import:SON40P150X250X65-13N")
      (fields (field (name "MOUSER_PART_NUMBER") "511-EMIF06-1005M12"))
      (libsource (lib "eagle-import") (part "EMIF06-1005M12"))
    )
    (comp (ref "FL4")
      (value "EMIF06-1005M12")
      (footprint "eagle-import:SON40P150X250X65-13N")
      (fields (field (name "MOUSER_PART_NUMBER") "511-EMIF06-1005M12"))
      (libsource (lib "eagle-import") (part "EMIF06-1005M12"))
    )
    (comp (ref "FL5")
      (value "EMIF06-1005M12")
      (footprint "eagle-import:SON40P150X250X65-13N")
      (fields (field (name "MOUSER_PART_NUMBER") "511-EMIF06-1005M12"))
      (libsource (lib "eagle-import") (part "EMIF06-1005M12"))
    )
    (comp (ref "H1")
      (value "MOUNT-PAD-ROUND2.8")
      (footprint "eagle-import:2,8-PAD")
      (libsource (lib "eagle-import") (part "MOUNT-PAD-ROUND2.8"))
    )
    (comp (ref "H2")
      (value "MOUNT-PAD-ROUND2.8")
      (footprint "eagle-import:2,8-PAD")
      (libsource (lib "eagle-import") (part "MOUNT-PAD-ROUND2.8"))
    )
    (comp (ref "IC1")
      (value "LM66200DRLR")
      (footprint "eagle-import:SOTFL50P160X60-8N")
      (fields (field (name "MOUSER_PART_NUMBER") "595-LM66200DRLR"))
      (libsource (lib "eagle-import") (part "LM66200DRLR"))
    )
    (comp (ref "IC2")
      (value "AP61300Z6-7")
      (footprint "eagle-import:SOTFL50P162X60-6N")
      (fields (field (name "MOUSER_PART_NUMBER") "621-AP61300Z6-7"))
      (libsource (lib "eagle-import") (part "AP61300Z6-7"))
    )
    (comp (ref "IC3")
      (value "IS42S16160G-6BL")
      (footprint "eagle-import:BGA54C80P9X9_800X800X120")
      (fields (field (name "MOUSER_PART_NUMBER") "870-IS42S16160G-6BL"))
      (libsource (lib "eagle-import") (part "IS42S16160G-6BL"))
    )
    (comp (ref "IC4")
      (value "ATECC608B-MAHDA-T")
      (footprint "eagle-import:SON50P300X200X60-9N")
      (fields (field (name "MOUSER_PART_NUMBER") "579-TECC608B-MAHDA-T"))
      (libsource (lib "eagle-import") (part "ATECC608B-MAHDA-T"))
    )
    (comp (ref "IC5")
      (value "IS25LP064D-JKLE-TR")
      (footprint "eagle-import:SON127P500X595X80-9N")
      (fields (field (name "MOUSER_PART_NUMBER") "870-5LP064D-JKLE-TR"))
      (libsource (lib "eagle-import") (part "IS25LP064D-JKLE-TR"))
    )
    (comp (ref "IC6")
      (value "IS25LP128F-JKLE-TR")
      (footprint "eagle-import:SON127P500X595X80-9N")
      (fields (field (name "MOUSER_PART_NUMBER") "870-IS25LP128FJKLETR"))
      (libsource (lib "eagle-import") (part "IS25LP128F-JKLE-TR"))
    )
    (comp (ref "IC7")
      (value "MXC4005XC")
      (footprint "eagle-import:MXC4005XC")
      (fields (field (name "MOUSER_PART_NUMBER") "438-MXC4005XC"))
      (libsource (lib "eagle-import") (part "MXC4005XC"))
    )
    (comp (ref "IC8")
      (value "MIMXRT106FCVL5B")
      (footprint "eagle-import:BGA196C65P14X14_1000X1000X143")
      (description "Processors - Application Specialized MIMXRT106FCVL5B/LFBGA196///STANDARD MARKING * TRAY")
      (fields
        (field (name "MANUFACTURER_PART_NUMBER") "MIMXRT1052DVL6B")
        (field (name "MOUSER_PART_NUMBER") "771-MIMXRT1052DVL6B")
        (field (name "MANUFACTURER_PART_NUMBER_1") "MIMXRT106FCVL5B")
        (field (name "MOUSER_PART_NUMBER_1") "771-MIMXRT106FCVL5B")
        (field (name "MOUSER_PRICE-STOCK") "https://www.mouser.co.uk/ProductDetail/NXP-Semiconductors/MIMXRT106FCVL5B")
      )
      (libsource (lib "eagle-import") (part "MIMXRT1052DVL6B"))
    )
    (comp (ref "IC9")
      (value "KSZ8081RNDCA-TR")
      (footprint "eagle-import:QFN50P400X400X90-25N")
      (fields (field (name "MOUSER_PART_NUMBER") "998-KSZ8081RNDCATR"))
      (libsource (lib "eagle-import") (part "KSZ8081RNDCA-TR"))
    )
    (comp (ref "J1")
      (value "USB4105-GF-A")
      (footprint "eagle-import:GCT_USB4105-GF-A")
      (fields (field (name "MF") "GCT"))
      (libsource (lib "eagle-import") (part "USB4105-GF-A"))
    )
    (comp (ref "J2")
      (value "DNP")
      (footprint "eagle-import:1X08")
      (libsource (lib "eagle-import") (part "CONN_08{dblquote}"))
    )
    (comp (ref "J3")
      (value "DNP")
      (footprint "eagle-import:1X08")
      (libsource (lib "eagle-import") (part "CONN_08{dblquote}"))
    )
    (comp (ref "J4")
      (value "DF12-36-DS")
      (footprint "eagle-import:DF12-36-DS")
      (fields (field (name "MPN") "DF12NB-36DS-0.5V(51)"))
      (libsource (lib "eagle-import") (part "DF12-36-DS"))
    )
    (comp (ref "J5")
      (value "USD-1040310811")
      (footprint "eagle-import:1040310811")
      (fields (field (name "MPN") "104031-0811"))
      (libsource (lib "eagle-import") (part "USD-1040310811"))
    )
    (comp (ref "J6")
      (value "DNP")
      (footprint "eagle-import:1X08")
      (libsource (lib "eagle-import") (part "CONN_08{dblquote}"))
    )
    (comp (ref "J7")
      (value "DNP")
      (footprint "eagle-import:23370191")
      (fields
        (field (name "MANUFACTURER_PART_NUMBER") "2337019-1")
        (field (name "MOUSER_PART_NUMBER") "571-2337019-1")
      )
      (libsource (lib "eagle-import") (part "2337019-1"))
    )
    (comp (ref "J8")
      (value "3221-10-0300-00")
      (footprint "eagle-import:CNC_3221-10-0300-00")
      (fields (field (name "MF") "CNC Tech"))
      (libsource (lib "eagle-import") (part "3221-10-0300-00"))
    )
    (comp (ref "L1")
      (value "100")
      (footprint "eagle-import:0603")
      (fields (field (name "MPN") "MFBM1V1608-101-R"))
      (libsource (lib "eagle-import") (part "INDUCTOR-0603-33NH"))
    )
    (comp (ref "L2")
      (value "MAKK2016T1R0M")
      (footprint "eagle-import:INDC2016X100N")
      (fields (field (name "MF") "Taiyo Yuden"))
      (libsource (lib "eagle-import") (part "MAKK2016T1R0M"))
    )
    (comp (ref "L4")
      (value "100")
      (footprint "eagle-import:C0402")
      (fields (field (name "MPN") "MFBM1V1005-101-R"))
      (libsource (lib "eagle-import") (part "INDUCTOR0402"))
    )
    (comp (ref "L5")
      (value "MAKK2016T4R7M")
      (footprint "eagle-import:INDC2016X100N")
      (fields (field (name "MF") "Taiyo Yuden"))
      (libsource (lib "eagle-import") (part "MAKK2016T4R7M"))
    )
    (comp (ref "L6")
      (value "100")
      (footprint "eagle-import:C0402")
      (fields (field (name "MPN") "MFBM1V1005-101-R"))
      (libsource (lib "eagle-import") (part "INDUCTOR0402"))
    )
    (comp (ref "L7")
      (value "3.9NH")
      (footprint "eagle-import:0402")
      (fields (field (name "MPN") "L-07C3N9SV6T"))
      (libsource (lib "eagle-import") (part "INDUCTOR-0402-3.9NH"))
    )
    (comp (ref "L8")
      (value "100")
      (footprint "eagle-import:C0402")
      (fields (field (name "MPN") "MFBM1V1005-101-R"))
      (libsource (lib "eagle-import") (part "INDUCTOR0402"))
    )
    (comp (ref "L9")
      (value "MAKK2016T2R2M")
      (footprint "eagle-import:INDC2016X100N")
      (fields (field (name "MF") "Taiyo Yuden"))
      (libsource (lib "eagle-import") (part "MAKK2016T2R2M"))
    )
    (comp (ref "M1")
      (value "9774030151R")
      (footprint "eagle-import:9774030151R")
      (libsource (lib "eagle-import") (part "9774030151R"))
    )
    (comp (ref "M2")
      (value "9774030151R")
      (footprint "eagle-import:9774030151R")
      (libsource (lib "eagle-import") (part "9774030151R"))
    )
    (comp (ref "Q1")
      (value "2N7002KW_R1_00001")
      (footprint "eagle-import:SOT65P210X110-3N")
      (fields (field (name "MOUSER_PART_NUMBER") "241-2N7002KWR100001"))
      (libsource (lib "eagle-import") (part "2N7002KW_R1_00001"))
    )
    (comp (ref "Q2")
      (value "2N7002KW_R1_00001")
      (footprint "eagle-import:SOT65P210X110-3N")
      (fields (field (name "MOUSER_PART_NUMBER") "241-2N7002KWR100001"))
      (libsource (lib "eagle-import") (part "2N7002KW_R1_00001"))
    )
    (comp (ref "Q3")
      (value "2N7002KW_R1_00001")
      (footprint "eagle-import:SOT65P210X110-3N")
      (fields (field (name "MOUSER_PART_NUMBER") "241-2N7002KWR100001"))
      (libsource (lib "eagle-import") (part "2N7002KW_R1_00001"))
    )
    (comp (ref "Q4")
      (value "2N7002KW_R1_00001")
      (footprint "eagle-import:SOT65P210X110-3N")
      (fields (field (name "MOUSER_PART_NUMBER") "241-2N7002KWR100001"))
      (libsource (lib "eagle-import") (part "2N7002KW_R1_00001"))
    )
    (comp (ref "Q5")
      (value "2N7002KW_R1_00001")
      (footprint "eagle-import:SOT65P210X110-3N")
      (fields (field (name "MOUSER_PART_NUMBER") "241-2N7002KWR100001"))
      (libsource (lib "eagle-import") (part "2N7002KW_R1_00001"))
    )
    (comp (ref "Q6")
      (value "PMXB120EPEZ")
      (footprint "eagle-import:PMXB120EPEZ")
      (fields (field (name "MOUSER_PART_NUMBER") "771-PMXB120EPEZ"))
      (libsource (lib "eagle-import") (part "PMXB120EPEZ"))
    )
    (comp (ref "R1")
      (value "1K")
      (footprint "eagle-import:0402-RES")
      (fields (field (name "MPN") "CRCW04021K00FKEDC"))
      (libsource (lib "eagle-import") (part "RESISTOR0402-RES"))
    )
    (comp (ref "R2")
      (value "200K")
      (footprint "eagle-import:0402-RES")
      (fields (field (name "MPN") "CRCW0402200KFKEDC"))
      (libsource (lib "eagle-import") (part "RESISTOR0402-RES"))
    )
    (comp (ref "R3")
      (value "100K")
      (footprint "eagle-import:0402-RES")
      (fields (field (name "MPN") "AC0402FR-07100KL"))
      (libsource (lib "eagle-import") (part "RESISTOR0402-RES"))
    )
    (comp (ref "R4")
      (value "1K")
      (footprint "eagle-import:0402-RES")
      (fields (field (name "MPN") "CRCW04021K00FKEDC"))
      (libsource (lib "eagle-import") (part "RESISTOR0402-RES"))
    )
    (comp (ref "R5")
      (value "1K")
      (footprint "eagle-import:0402-RES")
      (fields (field (name "MPN") "CRCW04021K00FKEDC"))
      (libsource (lib "eagle-import") (part "RESISTOR0402-RES"))
    )
    (comp (ref "R6")
      (value "5.1K")
      (footprint "eagle-import:0402-RES")
      (fields (field (name "MPN") "RC0402JR-075K1L"))
      (libsource (lib "eagle-import") (part "RESISTOR0402-RES"))
    )
    (comp (ref "R7")
      (value "5.1K")
      (footprint "eagle-import:0402-RES")
      (fields (field (name "MPN") "RC0402JR-075K1L"))
      (libsource (lib "eagle-import") (part "RESISTOR0402-RES"))
    )
    (comp (ref "R8")
      (value "44.2K")
      (footprint "eagle-import:0402-RES")
      (fields (field (name "MPN") "AC0402FR-0744K2L"))
      (libsource (lib "eagle-import") (part "RESISTOR0402-RES"))
    )
    (comp (ref "R9")
      (value "10K")
      (footprint "eagle-import:0402-RES")
      (fields (field (name "MPN") "AC0402FR-1310KL"))
      (libsource (lib "eagle-import") (part "RESISTOR0402-RES"))
    )
    (comp (ref "R10")
      (value "3.3K")
      (footprint "eagle-import:0402-RES")
      (fields (field (name "MPN") "CRCW04023K30FKEDC"))
      (libsource (lib "eagle-import") (part "RESISTOR0402-RES"))
    )
    (comp (ref "R11")
      (value "46.4K")
      (footprint "eagle-import:0402-RES")
      (fields (field (name "MPN") "WR04X4642FTL"))
      (libsource (lib "eagle-import") (part "RESISTOR0402-RES"))
    )
    (comp (ref "R12")
      (value "8.2K")
      (footprint "eagle-import:0402-RES")
      (fields (field (name "MPN") "RC0402JR-078K2L"))
      (libsource (lib "eagle-import") (part "RESISTOR0402-RES"))
    )
    (comp (ref "R13")
      (value "100K")
      (footprint "eagle-import:0402-RES")
      (fields (field (name "MPN") "AC0402FR-07100KL"))
      (libsource (lib "eagle-import") (part "RESISTOR0402-RES"))
    )
    (comp (ref "R14")
      (value "100K")
      (footprint "eagle-import:0402-RES")
      (fields (field (name "MPN") "AC0402FR-07100KL"))
      (libsource (lib "eagle-import") (part "RESISTOR0402-RES"))
    )
    (comp (ref "R15")
      (value "2.7K")
      (footprint "eagle-import:0402-RES")
      (fields (field (name "MPN") "AC0402JR-072K7L"))
      (libsource (lib "eagle-import") (part "RESISTOR0402-RES"))
    )
    (comp (ref "R16")
      (value "2.7K")
      (footprint "eagle-import:0402-RES")
      (fields (field (name "MPN") "AC0402JR-072K7L"))
      (libsource (lib "eagle-import") (part "RESISTOR0402-RES"))
    )
    (comp (ref "R17")
      (value "2.7K")
      (footprint "eagle-import:0402-RES")
      (fields (field (name "MPN") "AC0402JR-072K7L"))
      (libsource (lib "eagle-import") (part "RESISTOR0402-RES"))
    )
    (comp (ref "R18")
      (value "100K")
      (footprint "eagle-import:0402-RES")
      (fields (field (name "MPN") "AC0402FR-07100KL"))
      (libsource (lib "eagle-import") (part "RESISTOR0402-RES"))
    )
    (comp (ref "R19")
      (value "220")
      (footprint "eagle-import:0402-RES")
      (fields (field (name "MPN") "CRGCQ0402F220R"))
      (libsource (lib "eagle-import") (part "RESISTOR0402-RES"))
    )
    (comp (ref "R20")
      (value "220")
      (footprint "eagle-import:0402-RES")
      (fields (field (name "MPN") "CRGCQ0402F220R"))
      (libsource (lib "eagle-import") (part "RESISTOR0402-RES"))
    )
    (comp (ref "R21")
      (value "220")
      (footprint "eagle-import:0402-RES")
      (fields (field (name "MPN") "CRGCQ0402F220R"))
      (libsource (lib "eagle-import") (part "RESISTOR0402-RES"))
    )
    (comp (ref "R22")
      (value "100K")
      (footprint "eagle-import:0402-RES")
      (fields (field (name "MPN") "AC0402FR-07100KL"))
      (libsource (lib "eagle-import") (part "RESISTOR0402-RES"))
    )
    (comp (ref "R23")
      (value "100K")
      (footprint "eagle-import:0402-RES")
      (fields (field (name "MPN") "AC0402FR-07100KL"))
      (libsource (lib "eagle-import") (part "RESISTOR0402-RES"))
    )
    (comp (ref "R24")
      (value "100K")
      (footprint "eagle-import:0402-RES")
      (fields (field (name "MPN") "AC0402FR-07100KL"))
      (libsource (lib "eagle-import") (part "RESISTOR0402-RES"))
    )
    (comp (ref "R25")
      (value "100K")
      (footprint "eagle-import:0402-RES")
      (fields (field (name "MPN") "AC0402FR-07100KL"))
      (libsource (lib "eagle-import") (part "RESISTOR0402-RES"))
    )
    (comp (ref "R26")
      (value "1K")
      (footprint "eagle-import:0402-RES")
      (fields (field (name "MPN") "CRCW04021K00FKEDC"))
      (libsource (lib "eagle-import") (part "RESISTOR0402-RES"))
    )
    (comp (ref "R27")
      (value "100K")
      (footprint "eagle-import:0402-RES")
      (fields (field (name "MPN") "AC0402FR-07100KL"))
      (libsource (lib "eagle-import") (part "RESISTOR0402-RES"))
    )
    (comp (ref "R28")
      (value "100K")
      (footprint "eagle-import:0402-RES")
      (fields (field (name "MPN") "AC0402FR-07100KL"))
      (libsource (lib "eagle-import") (part "RESISTOR0402-RES"))
    )
    (comp (ref "R29")
      (value "100K")
      (footprint "eagle-import:0402-RES")
      (fields (field (name "MPN") "AC0402FR-07100KL"))
      (libsource (lib "eagle-import") (part "RESISTOR0402-RES"))
    )
    (comp (ref "R30")
      (value "4.7K")
      (footprint "eagle-import:0402-RES")
      (fields (field (name "MPN") "AC0402FR-074K7L"))
      (libsource (lib "eagle-import") (part "RESISTOR0402-RES"))
    )
    (comp (ref "R31")
      (value "4.7K")
      (footprint "eagle-import:0402-RES")
      (fields (field (name "MPN") "AC0402FR-074K7L"))
      (libsource (lib "eagle-import") (part "RESISTOR0402-RES"))
    )
    (comp (ref "R32")
      (value "30K")
      (footprint "eagle-import:0402-RES")
      (fields (field (name "MPN") "0402WGF3002TCE"))
      (libsource (lib "eagle-import") (part "RESISTOR0402-RES"))
    )
    (comp (ref "R33")
      (value "10K")
      (footprint "eagle-import:0402-RES")
      (fields (field (name "MPN") "AC0402FR-1310KL"))
      (libsource (lib "eagle-import") (part "RESISTOR0402-RES"))
    )
    (comp (ref "R34")
      (value "100K")
      (footprint "eagle-import:0402-RES")
      (fields (field (name "MPN") "AC0402FR-07100KL"))
      (libsource (lib "eagle-import") (part "RESISTOR0402-RES"))
    )
    (comp (ref "R35")
      (value "220")
      (footprint "eagle-import:0402-RES")
      (fields (field (name "MPN") "CRGCQ0402F220R"))
      (libsource (lib "eagle-import") (part "RESISTOR0402-RES"))
    )
    (comp (ref "R36")
      (value "1K")
      (footprint "eagle-import:0402-RES")
      (fields (field (name "MPN") "CRCW04021K00FKEDC"))
      (libsource (lib "eagle-import") (part "RESISTOR0402-RES"))
    )
    (comp (ref "R37")
      (value "10K")
      (footprint "eagle-import:0402-RES")
      (fields (field (name "MPN") "AC0402FR-1310KL"))
      (libsource (lib "eagle-import") (part "RESISTOR0402-RES"))
    )
    (comp (ref "R38")
      (value "6.49K")
      (footprint "eagle-import:0402-RES")
      (fields (field (name "MPN") "CR0402-FX-6491GLF"))
      (libsource (lib "eagle-import") (part "RESISTOR0402-RES"))
    )
    (comp (ref "R39")
      (value "1K")
      (footprint "eagle-import:0402-RES")
      (fields (field (name "MPN") "CRCW04021K00FKEDC"))
      (libsource (lib "eagle-import") (part "RESISTOR0402-RES"))
    )
    (comp (ref "R40")
      (value "2.2M")
      (footprint "eagle-import:0402-RES")
      (fields (field (name "MPN") "RC0402FR-072M2L"))
      (libsource (lib "eagle-import") (part "RESISTOR0402-RES"))
    )
    (comp (ref "R41")
      (value "1M")
      (footprint "eagle-import:0402-RES")
      (fields (field (name "MPN") "CRCW04021M00FKEDC"))
      (libsource (lib "eagle-import") (part "RESISTOR0402-RES"))
    )
    (comp (ref "RN1")
      (value "EXB-2HV104JV")
      (footprint "eagle-import:EXB2HV104JV")
      (fields (field (name "MOUSER_PART_NUMBER") "667-EXB-2HV104JV"))
      (libsource (lib "eagle-import") (part "EXB-2HV104JV"))
    )
    (comp (ref "RN2")
      (value "EXB-2HV104JV")
      (footprint "eagle-import:EXB2HV104JV")
      (fields (field (name "MOUSER_PART_NUMBER") "667-EXB-2HV104JV"))
      (libsource (lib "eagle-import") (part "EXB-2HV104JV"))
    )
    (comp (ref "U1")
      (value "MIC5365-3.3YMT-TZ")
      (footprint "eagle-import:VREG_MIC5365-3.3YMT-TZ")
      (libsource (lib "eagle-import") (part "MIC5365-3.3YMT-TZ"))
    )
    (comp (ref "U2")
      (value "BQ24075RGTR")
      (footprint "eagle-import:QFN50P300X300X100-17N")
      (fields (field (name "MF") "Texas Instruments"))
      (libsource (lib "eagle-import") (part "BQ24075RGTR"))
    )
    (comp (ref "U3")
      (value "LBEE5KL1DX-883")
      (footprint "eagle-import:XCVR_LBEE5KL1DX-TEMP")
      (fields (field (name "MF") "Murata Electronics") (field (name "MP") "LBEE5KL1DX-TEMP"))
      (libsource (lib "eagle-import") (part "LBEE5KL1DX-TEMP"))
    )
    (comp (ref "Y1")
      (value "SC32S-7PF20PPM")
      (footprint "eagle-import:XTAL_ABS07-32.768KHZ-7-T")
      (fields (field (name "MF") "Abracon") (field (name "MP") "ABS07-32.768KHZ-7-T"))
      (libsource (lib "eagle-import") (part "ABS07-32.768KHZ-7-T"))
    )
    (comp (ref "Y2")
      (value "XRCGB24M000F3M00R0")
      (footprint "eagle-import:XRCGB24M000F3M00R0")
      (fields (field (name "MOUSER_PART_NUMBER") "81-XRCGB24M000F3M0R0"))
      (libsource (lib "eagle-import") (part "XRCGB24M000F3M00R0"))
    )
  )
  (nets
    (net (code "1") (name "/BT_D_WAKE") (class "Default")
      (node (ref "IC8") (pin "L7") (pinfunction "PMIC_STBY_REQ_L7") (pintype "bidirectional"))
      (node (ref "U3") (pin "39") (pinfunction "BT_DEV_WAKE_39") (pintype "bidirectional"))
    )
    (net (code "2") (name "/BT_H_WAKE") (class "Default")
      (node (ref "IC8") (pin "H14") (pinfunction "GPIO_AD_B0_14_H14") (pintype "bidirectional"))
      (node (ref "U3") (pin "38") (pinfunction "BT_HOST_WAKE_38") (pintype "bidirectional"))
    )
    (net (code "3") (name "/BT_REG_ON") (class "Default")
      (node (ref "IC8") (pin "F13") (pinfunction "GPIO_AD_B0_08_F13") (pintype "bidirectional"))
      (node (ref "R37") (pin "1") (pinfunction "1_1") (pintype "passive"))
      (node (ref "U3") (pin "14") (pinfunction "BT_REG_ON_14") (pintype "input"))
    )
    (net (code "4") (name "/BT_UART_RX") (class "Default")
      (node (ref "IC8") (pin "C9") (pinfunction "GPIO_B0_09_C9") (pintype "bidirectional"))
      (node (ref "U3") (pin "3") (pinfunction "BT_UART_TXD_3") (pintype "output"))
    )
    (net (code "5") (name "/BT_UART_TX") (class "Default")
      (node (ref "IC8") (pin "B9") (pinfunction "GPIO_B0_08_B9") (pintype "bidirectional"))
      (node (ref "U3") (pin "2") (pinfunction "BT_UART_RXD_2") (pintype "input"))
    )
    (net (code "6") (name "/DCDC_LP") (class "Default")
      (node (ref "IC8") (pin "M1") (pinfunction "DCDC_LP_1_M1") (pintype "bidirectional"))
      (node (ref "IC8") (pin "M2") (pinfunction "DCDC_LP_2_M2") (pintype "bidirectional"))
      (node (ref "L5") (pin "2") (pinfunction "2_2") (pintype "passive"))
    )
    (net (code "7") (name "/DCDC_PSWITCH") (class "Default")
      (node (ref "C62") (pin "1") (pinfunction "1_1") (pintype "passive"))
      (node (ref "IC8") (pin "K3") (pinfunction "DCDC_PSWITCH_K3") (pintype "bidirectional"))
      (node (ref "R32") (pin "1") (pinfunction "1_1") (pintype "passive"))
    )
    (net (code "8") (name "/DCMI_CLK") (class "Default")
      (node (ref "IC8") (pin "B14") (pinfunction "GPIO_B1_15_B14") (pintype "bidirectional"))
      (node (ref "J4") (pin "12") (pinfunction "12_12") (pintype "bidirectional"))
    )
    (net (code "9") (name "/DCMI_D0") (class "Default")
      (node (ref "IC8") (pin "J14") (pinfunction "GPIO_AD_B1_15_J14") (pintype "bidirectional"))
      (node (ref "J4") (pin "31") (pinfunction "31_31") (pintype "bidirectional"))
    )
    (net (code "10") (name "/DCMI_D1") (class "Default")
      (node (ref "IC8") (pin "G12") (pinfunction "GPIO_AD_B1_14_G12") (pintype "bidirectional"))
      (node (ref "J4") (pin "29") (pinfunction "29_29") (pintype "bidirectional"))
    )
    (net (code "11") (name "/DCMI_D2") (class "Default")
      (node (ref "IC8") (pin "H11") (pinfunction "GPIO_AD_B1_13_H11") (pintype "bidirectional"))
      (node (ref "J4") (pin "35") (pinfunction "35_35") (pintype "bidirectional"))
    )
    (net (code "12") (name "/DCMI_D3") (class "Default")
      (node (ref "IC8") (pin "H12") (pinfunction "GPIO_AD_B1_12_H12") (pintype "bidirectional"))
      (node (ref "J4") (pin "28") (pinfunction "28_28") (pintype "bidirectional"))
    )
    (net (code "13") (name "/DCMI_D4") (class "Default")
      (node (ref "IC8") (pin "J13") (pinfunction "GPIO_AD_B1_11_J13") (pintype "bidirectional"))
      (node (ref "J4") (pin "26") (pinfunction "26_26") (pintype "bidirectional"))
    )
    (net (code "14") (name "/DCMI_D5") (class "Default")
      (node (ref "IC8") (pin "L13") (pinfunction "GPIO_AD_B1_10_L13") (pintype "bidirectional"))
      (node (ref "J4") (pin "33") (pinfunction "33_33") (pintype "bidirectional"))
    )
    (net (code "15") (name "/DCMI_D6") (class "Default")
      (node (ref "IC8") (pin "G14") (pinfunction "GPIO_AD_B0_05_G14") (pintype "bidirectional"))
      (node (ref "J4") (pin "24") (pinfunction "24_24") (pintype "bidirectional"))
    )
    (net (code "16") (name "/DCMI_D7") (class "Default")
      (node (ref "IC8") (pin "F11") (pinfunction "GPIO_AD_B0_04_F11") (pintype "bidirectional"))
      (node (ref "J4") (pin "22") (pinfunction "22_22") (pintype "bidirectional"))
    )
    (net (code "17") (name "/DCMI_FSIN") (class "Default")
      (node (ref "J4") (pin "23") (pinfunction "23_23") (pintype "bidirectional"))
      (node (ref "Q5") (pin "3") (pinfunction "D_3") (pintype "bidirectional"))
      (node (ref "R28") (pin "1") (pinfunction "1_1") (pintype "passive"))
    )
    (net (code "18") (name "/DCMI_HSYNC") (class "Default")
      (node (ref "IC8") (pin "L10") (pinfunction "GPIO_AD_B0_15_L10") (pintype "bidirectional"))
      (node (ref "J4") (pin "18") (pinfunction "18_18") (pintype "bidirectional"))
    )
    (net (code "19") (name "/DCMI_MISO") (class "Default")
      (node (ref "IC8") (pin "E7") (pinfunction "GPIO_B0_01_E7") (pintype "bidirectional"))
      (node (ref "J4") (pin "15") (pinfunction "15_15") (pintype "bidirectional"))
    )
    (net (code "20") (name "/DCMI_MOSI") (class "Default")
      (node (ref "IC8") (pin "E8") (pinfunction "GPIO_B0_02_E8") (pintype "bidirectional"))
      (node (ref "J4") (pin "17") (pinfunction "17_17") (pintype "bidirectional"))
    )
    (net (code "21") (name "/DCMI_PCLK") (class "Default")
      (node (ref "IC8") (pin "D13") (pinfunction "GPIO_B1_12_D13") (pintype "bidirectional"))
      (node (ref "J4") (pin "14") (pinfunction "14_14") (pintype "bidirectional"))
    )
    (net (code "22") (name "/DCMI_PWDN") (class "Default")
      (node (ref "IC8") (pin "C11") (pinfunction "GPIO_B1_02_C11") (pintype "bidirectional"))
      (node (ref "J4") (pin "25") (pinfunction "25_25") (pintype "bidirectional"))
      (node (ref "R29") (pin "1") (pinfunction "1_1") (pintype "passive"))
    )
    (net (code "23") (name "/DCMI_RST") (class "Default")
      (node (ref "IC8") (pin "B11") (pinfunction "GPIO_B1_01_B11") (pintype "bidirectional"))
      (node (ref "J4") (pin "21") (pinfunction "21_21") (pintype "bidirectional"))
      (node (ref "R27") (pin "1") (pinfunction "1_1") (pintype "passive"))
    )
    (net (code "24") (name "/DCMI_SCL") (class "Default")
      (node (ref "IC8") (pin "J11") (pinfunction "GPIO_AD_B1_00_J11") (pintype "bidirectional"))
      (node (ref "J4") (pin "32") (pinfunction "32_32") (pintype "bidirectional"))
      (node (ref "R30") (pin "1") (pinfunction "1_1") (pintype "passive"))
    )
    (net (code "25") (name "/DCMI_SCLK") (class "Default")
      (node (ref "IC8") (pin "D8") (pinfunction "GPIO_B0_03_D8") (pintype "bidirectional"))
      (node (ref "J4") (pin "13") (pinfunction "13_13") (pintype "bidirectional"))
    )
    (net (code "26") (name "/DCMI_SDA") (class "Default")
      (node (ref "IC8") (pin "K11") (pinfunction "GPIO_AD_B1_01_K11") (pintype "bidirectional"))
      (node (ref "J4") (pin "34") (pinfunction "34_34") (pintype "bidirectional"))
      (node (ref "R31") (pin "1") (pinfunction "1_1") (pintype "passive"))
    )
    (net (code "27") (name "/DCMI_SSEL") (class "Default")
      (node (ref "IC8") (pin "D7") (pinfunction "GPIO_B0_00_D7") (pintype "bidirectional"))
      (node (ref "J4") (pin "11") (pinfunction "11_11") (pintype "bidirectional"))
      (node (ref "R24") (pin "1") (pinfunction "1_1") (pintype "passive"))
    )
    (net (code "28") (name "/DCMI_VSYNC") (class "Default")
      (node (ref "IC8") (pin "D14") (pinfunction "GPIO_B1_13_D14") (pintype "bidirectional"))
      (node (ref "J4") (pin "16") (pinfunction "16_16") (pintype "bidirectional"))
    )
    (net (code "29") (name "/ETH_INT") (class "Default")
      (node (ref "IC8") (pin "C10") (pinfunction "GPIO_B0_12_C10") (pintype "bidirectional"))
      (node (ref "IC9") (pin "18") (pinfunction "INTRP_18") (pintype "bidirectional"))
      (node (ref "R36") (pin "1") (pinfunction "1_1") (pintype "passive"))
    )
    (net (code "30") (name "/ETH_MDC") (class "Default")
      (node (ref "IC8") (pin "A7") (pinfunction "GPIO_EMC_40_A7") (pintype "bidirectional"))
      (node (ref "IC9") (pin "11") (pinfunction "MDC_11") (pintype "bidirectional"))
    )
    (net (code "31") (name "/ETH_MDIO") (class "Default")
      (node (ref "IC8") (pin "C7") (pinfunction "GPIO_EMC_41_C7") (pintype "bidirectional"))
      (node (ref "IC9") (pin "10") (pinfunction "MDIO_10") (pintype "bidirectional"))
      (node (ref "R39") (pin "1") (pinfunction "1_1") (pintype "passive"))
    )
    (net (code "32") (name "/ETH_RST") (class "Default")
      (node (ref "C65") (pin "2") (pinfunction "2_2") (pintype "passive"))
      (node (ref "IC8") (pin "D10") (pinfunction "GPIO_B0_13_D10") (pintype "bidirectional"))
      (node (ref "IC9") (pin "24") (pinfunction "RST#_24") (pintype "bidirectional"))
      (node (ref "R34") (pin "1") (pinfunction "1_1") (pintype "passive"))
    )
    (net (code "33") (name "/ETH_RXD0") (class "Default")
      (node (ref "IC8") (pin "E12") (pinfunction "GPIO_B1_04_E12") (pintype "bidirectional"))
      (node (ref "IC9") (pin "13") (pinfunction "RXD0_13") (pintype "bidirectional"))
    )
    (net (code "34") (name "/ETH_RXD1") (class "Default")
      (node (ref "IC8") (pin "D12") (pinfunction "GPIO_B1_05_D12") (pintype "bidirectional"))
      (node (ref "IC9") (pin "12") (pinfunction "RXD1_12") (pintype "bidirectional"))
    )
    (net (code "35") (name "/ETH_RXDV") (class "Default")
      (node (ref "IC8") (pin "C12") (pinfunction "GPIO_B1_06_C12") (pintype "bidirectional"))
      (node (ref "IC9") (pin "15") (pinfunction "CRS_DV/_PHYAD[1:0]_15") (pintype "bidirectional"))
    )
    (net (code "36") (name "/ETH_RXERR") (class "Default")
      (node (ref "IC8") (pin "C13") (pinfunction "GPIO_B1_11_C13") (pintype "bidirectional"))
      (node (ref "IC9") (pin "17") (pinfunction "RXER_17") (pintype "bidirectional"))
    )
    (net (code "37") (name "/ETH_TXCLK") (class "Default")
      (node (ref "IC8") (pin "B13") (pinfunction "GPIO_B1_10_B13") (pintype "bidirectional"))
      (node (ref "IC9") (pin "8") (pinfunction "XI_8") (pintype "bidirectional"))
    )
    (net (code "38") (name "/ETH_TXD0") (class "Default")
      (node (ref "IC8") (pin "B12") (pinfunction "GPIO_B1_07_B12") (pintype "bidirectional"))
      (node (ref "IC9") (pin "20") (pinfunction "TXD0_20") (pintype "bidirectional"))
    )
    (net (code "39") (name "/ETH_TXD1") (class "Default")
      (node (ref "IC8") (pin "A12") (pinfunction "GPIO_B1_08_A12") (pintype "bidirectional"))
      (node (ref "IC9") (pin "21") (pinfunction "TXD1_21") (pintype "bidirectional"))
    )
    (net (code "40") (name "/ETH_TXEN") (class "Default")
      (node (ref "IC8") (pin "A13") (pinfunction "GPIO_B1_09_A13") (pintype "bidirectional"))
      (node (ref "IC9") (pin "19") (pinfunction "TXEN_19") (pintype "bidirectional"))
    )
    (net (code "41") (name "/INT_I2C_INT") (class "Default")
      (node (ref "IC7") (pin "4") (pinfunction "INT_4") (pintype "bidirectional"))
      (node (ref "IC8") (pin "D11") (pinfunction "GPIO_B1_03_D11") (pintype "bidirectional"))
      (node (ref "R17") (pin "1") (pinfunction "1_1") (pintype "passive"))
    )
    (net (code "42") (name "/INT_I2C_SCL") (class "Default")
      (node (ref "IC4") (pin "6") (pinfunction "SCL_6") (pintype "bidirectional"))
      (node (ref "IC7") (pin "1") (pinfunction "SCL_1") (pintype "bidirectional"))
      (node (ref "IC8") (pin "C8") (pinfunction "GPIO_B0_04_C8") (pintype "bidirectional"))
      (node (ref "R15") (pin "1") (pinfunction "1_1") (pintype "passive"))
    )
    (net (code "43") (name "/INT_I2C_SDA") (class "Default")
      (node (ref "IC4") (pin "5") (pinfunction "SDA_5") (pintype "bidirectional"))
      (node (ref "IC7") (pin "5") (pinfunction "SDA_5") (pintype "bidirectional"))
      (node (ref "IC8") (pin "B8") (pinfunction "GPIO_B0_05_B8") (pintype "bidirectional"))
      (node (ref "R16") (pin "1") (pinfunction "1_1") (pintype "passive"))
    )
    (net (code "44") (name "/JTAG_TCK") (class "Default")
      (node (ref "FL5") (pin "4") (pinfunction "INPUT_4_4") (pintype "bidirectional"))
      (node (ref "IC8") (pin "F12") (pinfunction "GPIO_AD_B0_07_F12") (pintype "bidirectional"))
    )
    (net (code "45") (name "/JTAG_TCK_INT") (class "Default")
      (node (ref "FL5") (pin "9") (pinfunction "OUTPUT_4_9") (pintype "bidirectional"))
      (node (ref "J8") (pin "4") (pinfunction "4_4") (pintype "passive"))
    )
    (net (code "46") (name "/JTAG_TDI") (class "Default")
      (node (ref "FL5") (pin "2") (pinfunction "INPUT_2_2") (pintype "bidirectional"))
      (node (ref "IC8") (pin "F14") (pinfunction "GPIO_AD_B0_09_F14") (pintype "bidirectional"))
    )
    (net (code "47") (name "/JTAG_TDI_INT") (class "Default")
      (node (ref "FL5") (pin "11") (pinfunction "OUTPUT_2_11") (pintype "bidirectional"))
      (node (ref "J8") (pin "8") (pinfunction "8_8") (pintype "passive"))
    )
    (net (code "48") (name "/JTAG_TDO") (class "Default")
      (node (ref "FL5") (pin "3") (pinfunction "INPUT_3_3") (pintype "bidirectional"))
      (node (ref "IC8") (pin "G13") (pinfunction "GPIO_AD_B0_10_G13") (pintype "bidirectional"))
    )
    (net (code "49") (name "/JTAG_TDO_INT") (class "Default")
      (node (ref "FL5") (pin "10") (pinfunction "OUTPUT_3_10") (pintype "bidirectional"))
      (node (ref "J8") (pin "6") (pinfunction "6_6") (pintype "passive"))
    )
    (net (code "50") (name "/JTAG_TMS") (class "Default")
      (node (ref "FL5") (pin "5") (pinfunction "INPUT_5_5") (pintype "bidirectional"))
      (node (ref "IC8") (pin "E14") (pinfunction "GPIO_AD_B0_06_E14") (pintype "bidirectional"))
    )
    (net (code "51") (name "/JTAG_TMS_INT") (class "Default")
      (node (ref "FL5") (pin "8") (pinfunction "OUTPUT_5_8") (pintype "bidirectional"))
      (node (ref "J8") (pin "2") (pinfunction "2_2") (pintype "passive"))
    )
    (net (code "52") (name "/JTAG_TRSTB") (class "Default")
      (node (ref "FL5") (pin "6") (pinfunction "INPUT_6_6") (pintype "bidirectional"))
      (node (ref "IC8") (pin "G10") (pinfunction "GPIO_AD_B0_11_G10") (pintype "bidirectional"))
    )
    (net (code "53") (name "/LED_B") (class "Default")
      (node (ref "IC8") (pin "C14") (pinfunction "GPIO_B1_14_C14") (pintype "bidirectional"))
      (node (ref "R19") (pin "1") (pinfunction "1_1") (pintype "passive"))
    )
    (net (code "54") (name "/LED_CHG") (class "Default")
      (node (ref "D1") (pin "3") (pinfunction "RED_3") (pintype "passive"))
      (node (ref "R1") (pin "2") (pinfunction "2_2") (pintype "passive"))
    )
    (net (code "55") (name "/LED_G") (class "Default")
      (node (ref "IC8") (pin "A10") (pinfunction "GPIO_B0_11_A10") (pintype "bidirectional"))
      (node (ref "R20") (pin "1") (pinfunction "1_1") (pintype "passive"))
    )
    (net (code "56") (name "/LED_PGOOD") (class "Default")
      (node (ref "D1") (pin "2") (pinfunction "GREEN_2") (pintype "passive"))
      (node (ref "R4") (pin "2") (pinfunction "2_2") (pintype "passive"))
    )
    (net (code "57") (name "/LED_R") (class "Default")
      (node (ref "IC8") (pin "D9") (pinfunction "GPIO_B0_10_D9") (pintype "bidirectional"))
      (node (ref "R21") (pin "1") (pinfunction "1_1") (pintype "passive"))
    )
    (net (code "58") (name "/MDI_LED") (class "Default")
      (node (ref "J3") (pin "8") (pinfunction "8_8") (pintype "passive"))
      (node (ref "R35") (pin "2") (pinfunction "2_2") (pintype "passive"))
    )
    (net (code "59") (name "/MDI_RX_N") (class "Default")
      (node (ref "IC9") (pin "3") (pinfunction "RXM_3") (pintype "bidirectional"))
      (node (ref "J3") (pin "7") (pinfunction "7_7") (pintype "passive"))
    )
    (net (code "60") (name "/MDI_RX_P") (class "Default")
      (node (ref "IC9") (pin "4") (pinfunction "RXP_4") (pintype "bidirectional"))
      (node (ref "J3") (pin "6") (pinfunction "6_6") (pintype "passive"))
    )
    (net (code "61") (name "/MDI_TX_N") (class "Default")
      (node (ref "IC9") (pin "5") (pinfunction "TXM_5") (pintype "bidirectional"))
      (node (ref "J3") (pin "5") (pinfunction "5_5") (pintype "passive"))
    )
    (net (code "62") (name "/MDI_TX_P") (class "Default")
      (node (ref "IC9") (pin "6") (pinfunction "TXP_6") (pintype "bidirectional"))
      (node (ref "J3") (pin "4") (pinfunction "4_4") (pintype "passive"))
    )
    (net (code "63") (name "/NVCC_PLL") (class "Default")
      (node (ref "C104") (pin "2") (pinfunction "2_2") (pintype "passive"))
      (node (ref "C107") (pin "1") (pinfunction "1_1") (pintype "passive"))
      (node (ref "IC8") (pin "P10") (pinfunction "NVCC_PLL_P10") (pintype "bidirectional"))
    )
    (net (code "64") (name "/ONOFF") (class "Default")
      (node (ref "IC8") (pin "M6") (pinfunction "ONOFF_M6") (pintype "bidirectional"))
      (node (ref "Q3") (pin "2") (pinfunction "S_2") (pintype "bidirectional"))
    )
    (net (code "65") (name "/P0_MOSI") (class "Default")
      (node (ref "FL2") (pin "1") (pinfunction "INPUT_1_1") (pintype "bidirectional"))
      (node (ref "IC8") (pin "H10") (pinfunction "GPIO_AD_B0_01_H10") (pintype "bidirectional"))
    )
    (net (code "66") (name "/P1_MISO") (class "Default")
      (node (ref "FL2") (pin "2") (pinfunction "INPUT_2_2") (pintype "bidirectional"))
      (node (ref "IC8") (pin "M11") (pinfunction "GPIO_AD_B0_02_M11") (pintype "bidirectional"))
    )
    (net (code "67") (name "/P2_SCLK") (class "Default")
      (node (ref "FL2") (pin "3") (pinfunction "INPUT_3_3") (pintype "bidirectional"))
      (node (ref "IC8") (pin "M14") (pinfunction "GPIO_AD_B0_00_M14") (pintype "bidirectional"))
    )
    (net (code "68") (name "/P3_NSS") (class "Default")
      (node (ref "FL2") (pin "4") (pinfunction "INPUT_4_4") (pintype "bidirectional"))
      (node (ref "IC8") (pin "G11") (pinfunction "GPIO_AD_B0_03_G11") (pintype "bidirectional"))
    )
    (net (code "69") (name "/P4_SCL") (class "Default")
      (node (ref "FL2") (pin "5") (pinfunction "INPUT_5_5") (pintype "bidirectional"))
      (node (ref "IC8") (pin "K14") (pinfunction "GPIO_AD_B0_12_K14") (pintype "bidirectional"))
    )
    (net (code "70") (name "/P5_SDA") (class "Default")
      (node (ref "FL2") (pin "6") (pinfunction "INPUT_6_6") (pintype "bidirectional"))
      (node (ref "IC8") (pin "L14") (pinfunction "GPIO_AD_B0_13_L14") (pintype "bidirectional"))
    )
    (net (code "71") (name "/P6_ADC") (class "Default")
      (node (ref "FL4") (pin "1") (pinfunction "INPUT_1_1") (pintype "bidirectional"))
      (node (ref "IC8") (pin "M12") (pinfunction "GPIO_AD_B1_03_M12") (pintype "bidirectional"))
    )
    (net (code "72") (name "/P7_PWM") (class "Default")
      (node (ref "FL4") (pin "2") (pinfunction "INPUT_2_2") (pintype "bidirectional"))
      (node (ref "IC8") (pin "A8") (pinfunction "GPIO_B0_06_A8") (pintype "bidirectional"))
    )
    (net (code "73") (name "/P7_PWM_INT") (class "Default")
      (node (ref "FL4") (pin "11") (pinfunction "OUTPUT_2_11") (pintype "bidirectional"))
      (node (ref "J6") (pin "3") (pinfunction "3_3") (pintype "passive"))
    )
    (net (code "74") (name "/P8_PWM") (class "Default")
      (node (ref "FL4") (pin "3") (pinfunction "INPUT_3_3") (pintype "bidirectional"))
      (node (ref "IC8") (pin "A9") (pinfunction "GPIO_B0_07_A9") (pintype "bidirectional"))
    )
    (net (code "75") (name "/P8_PWM_INT") (class "Default")
      (node (ref "FL4") (pin "10") (pinfunction "OUTPUT_3_10") (pintype "bidirectional"))
      (node (ref "J6") (pin "4") (pinfunction "4_4") (pintype "passive"))
    )
    (net (code "76") (name "/P9_PWM") (class "Default")
      (node (ref "FL4") (pin "4") (pinfunction "INPUT_4_4") (pintype "bidirectional"))
      (node (ref "IC8") (pin "A11") (pinfunction "GPIO_B1_00_A11") (pintype "bidirectional"))
    )
    (net (code "77") (name "/P9_PWM_INT") (class "Default")
      (node (ref "FL4") (pin "9") (pinfunction "OUTPUT_4_9") (pintype "bidirectional"))
      (node (ref "J6") (pin "5") (pinfunction "5_5") (pintype "passive"))
    )
    (net (code "78") (name "/P10_PWM") (class "Default")
      (node (ref "FL4") (pin "5") (pinfunction "INPUT_5_5") (pintype "bidirectional"))
      (node (ref "Q4") (pin "3") (pinfunction "D_3") (pintype "bidirectional"))
      (node (ref "R26") (pin "1") (pinfunction "1_1") (pintype "passive"))
    )
    (net (code "79") (name "/P10_PWM_INT") (class "Default")
      (node (ref "FL4") (pin "8") (pinfunction "OUTPUT_5_8") (pintype "bidirectional"))
      (node (ref "J6") (pin "6") (pinfunction "6_6") (pintype "passive"))
    )
    (net (code "80") (name "/P11_WAKEUP") (class "Default")
      (node (ref "FL4") (pin "6") (pinfunction "INPUT_6_6") (pintype "bidirectional"))
      (node (ref "Q2") (pin "3") (pinfunction "D_3") (pintype "bidirectional"))
      (node (ref "R22") (pin "1") (pinfunction "1_1") (pintype "passive"))
    )
    (net (code "81") (name "/P11_WAKEUP_INT") (class "Default")
      (node (ref "FL4") (pin "7") (pinfunction "OUTPUT_6_7") (pintype "bidirectional"))
      (node (ref "J6") (pin "7") (pinfunction "7_7") (pintype "passive"))
    )
    (net (code "82") (name "/P12_RST_N") (class "Default")
      (node (ref "C63") (pin "1") (pinfunction "1_1") (pintype "passive"))
      (node (ref "FL5") (pin "1") (pinfunction "INPUT_1_1") (pintype "bidirectional"))
      (node (ref "IC8") (pin "M7") (pinfunction "POR_B_M7") (pintype "bidirectional"))
      (node (ref "R33") (pin "2") (pinfunction "2_2") (pintype "passive"))
    )
    (net (code "83") (name "/P12_RST_N_EXT") (class "Default")
      (node (ref "FL5") (pin "12") (pinfunction "OUTPUT_1_12") (pintype "bidirectional"))
      (node (ref "J6") (pin "8") (pinfunction "8_8") (pintype "passive"))
      (node (ref "J8") (pin "10") (pinfunction "10_10") (pintype "passive"))
    )
    (net (code "84") (name "/PMIC_ONOFF") (class "Default")
      (node (ref "D8") (pin "1") (pinfunction "1_1") (pintype "bidirectional"))
      (node (ref "J3") (pin "3") (pinfunction "3_3") (pintype "passive"))
      (node (ref "Q3") (pin "3") (pinfunction "D_3") (pintype "bidirectional"))
      (node (ref "R23") (pin "1") (pinfunction "1_1") (pintype "passive"))
    )
    (net (code "85") (name "/PMIC_ON_REQ") (class "Default")
      (node (ref "IC8") (pin "K7") (pinfunction "PMIC_ON_REQ_K7") (pintype "bidirectional"))
      (node (ref "Q1") (pin "2") (pinfunction "S_2") (pintype "bidirectional"))
    )
    (net (code "86") (name "/PWM_FSIN") (class "Default")
      (node (ref "IC8") (pin "B7") (pinfunction "GPIO_EMC_39_B7") (pintype "bidirectional"))
      (node (ref "Q4") (pin "2") (pinfunction "S_2") (pintype "bidirectional"))
      (node (ref "Q5") (pin "2") (pinfunction "S_2") (pintype "bidirectional"))
      (node (ref "R25") (pin "1") (pinfunction "1_1") (pintype "passive"))
    )
    (net (code "87") (name "/P_FLASH_CE") (class "Default")
      (node (ref "IC5") (pin "1") (pinfunction "CE#_1") (pintype "bidirectional"))
      (node (ref "IC8") (pin "L3") (pinfunction "GPIO_SD_B1_06_L3") (pintype "bidirectional"))
      (node (ref "R13") (pin "2") (pinfunction "2_2") (pintype "passive"))
    )
    (net (code "88") (name "/P_FLASH_IO0") (class "Default")
      (node (ref "IC5") (pin "5") (pinfunction "SI_(IO0)_5") (pintype "bidirectional"))
      (node (ref "IC8") (pin "P3") (pinfunction "GPIO_SD_B1_08_P3") (pintype "bidirectional"))
    )
    (net (code "89") (name "/P_FLASH_IO1") (class "Default")
      (node (ref "IC5") (pin "2") (pinfunction "SO_(IO1)_2") (pintype "bidirectional"))
      (node (ref "IC8") (pin "N4") (pinfunction "GPIO_SD_B1_09_N4") (pintype "bidirectional"))
    )
    (net (code "90") (name "/P_FLASH_IO2") (class "Default")
      (node (ref "IC5") (pin "3") (pinfunction "WP#_(IO2)_3") (pintype "bidirectional"))
      (node (ref "IC8") (pin "P4") (pinfunction "GPIO_SD_B1_10_P4") (pintype "bidirectional"))
    )
    (net (code "91") (name "/P_FLASH_IO3") (class "Default")
      (node (ref "IC5") (pin "7") (pinfunction "HOLD#_(IO3)_7") (pintype "bidirectional"))
      (node (ref "IC8") (pin "P5") (pinfunction "GPIO_SD_B1_11_P5") (pintype "bidirectional"))
    )
    (net (code "92") (name "/P_FLASH_SCK") (class "Default")
      (node (ref "IC5") (pin "6") (pinfunction "SCK_6") (pintype "bidirectional"))
      (node (ref "IC8") (pin "L4") (pinfunction "GPIO_SD_B1_07_L4") (pintype "bidirectional"))
    )
    (net (code "93") (name "/RTC_XTALI") (class "Default")
      (node (ref "C80") (pin "1") (pinfunction "1_1") (pintype "passive"))
      (node (ref "IC8") (pin "N9") (pinfunction "RTC_XTALI_N9") (pintype "bidirectional"))
      (node (ref "Y1") (pin "2") (pinfunction "2_2") (pintype "passive"))
    )
    (net (code "94") (name "/RTC_XTALO") (class "Default")
      (node (ref "C79") (pin "1") (pinfunction "1_1") (pintype "passive"))
      (node (ref "IC8") (pin "P9") (pinfunction "RTC_XTALO_P9") (pintype "bidirectional"))
      (node (ref "Y1") (pin "1") (pinfunction "1_1") (pintype "passive"))
    )
    (net (code "95") (name "/SDRAM_A0") (class "Default")
      (node (ref "IC3") (pin "H7") (pinfunction "A0_H7") (pintype "bidirectional"))
      (node (ref "IC8") (pin "C2") (pinfunction "GPIO_EMC_09_C2") (pintype "bidirectional"))
    )
    (net (code "96") (name "/SDRAM_A1") (class "Default")
      (node (ref "IC3") (pin "H8") (pinfunction "A1_H8") (pintype "bidirectional"))
      (node (ref "IC8") (pin "G1") (pinfunction "GPIO_EMC_10_G1") (pintype "bidirectional"))
    )
    (net (code "97") (name "/SDRAM_A2") (class "Default")
      (node (ref "IC3") (pin "J8") (pinfunction "A2_J8") (pintype "bidirectional"))
      (node (ref "IC8") (pin "G3") (pinfunction "GPIO_EMC_11_G3") (pintype "bidirectional"))
    )
    (net (code "98") (name "/SDRAM_A3") (class "Default")
      (node (ref "IC3") (pin "J7") (pinfunction "A3_J7") (pintype "bidirectional"))
      (node (ref "IC8") (pin "H1") (pinfunction "GPIO_EMC_12_H1") (pintype "bidirectional"))
    )
    (net (code "99") (name "/SDRAM_A4") (class "Default")
      (node (ref "IC3") (pin "J3") (pinfunction "A4_J3") (pintype "bidirectional"))
      (node (ref "IC8") (pin "A6") (pinfunction "GPIO_EMC_13_A6") (pintype "bidirectional"))
    )
    (net (code "100") (name "/SDRAM_A5") (class "Default")
      (node (ref "IC3") (pin "J2") (pinfunction "A5_J2") (pintype "bidirectional"))
      (node (ref "IC8") (pin "B6") (pinfunction "GPIO_EMC_14_B6") (pintype "bidirectional"))
    )
    (net (code "101") (name "/SDRAM_A6") (class "Default")
      (node (ref "IC3") (pin "H3") (pinfunction "A6_H3") (pintype "bidirectional"))
      (node (ref "IC8") (pin "B1") (pinfunction "GPIO_EMC_15_B1") (pintype "bidirectional"))
    )
    (net (code "102") (name "/SDRAM_A7") (class "Default")
      (node (ref "IC3") (pin "H2") (pinfunction "A7_H2") (pintype "bidirectional"))
      (node (ref "IC8") (pin "A5") (pinfunction "GPIO_EMC_16_A5") (pintype "bidirectional"))
    )
    (net (code "103") (name "/SDRAM_A8") (class "Default")
      (node (ref "IC3") (pin "H1") (pinfunction "A8_H1") (pintype "bidirectional"))
      (node (ref "IC8") (pin "A4") (pinfunction "GPIO_EMC_17_A4") (pintype "bidirectional"))
    )
    (net (code "104") (name "/SDRAM_A9") (class "Default")
      (node (ref "IC3") (pin "G3") (pinfunction "A9_G3") (pintype "bidirectional"))
      (node (ref "IC8") (pin "B2") (pinfunction "GPIO_EMC_18_B2") (pintype "bidirectional"))
    )
    (net (code "105") (name "/SDRAM_A10") (class "Default")
      (node (ref "IC3") (pin "H9") (pinfunction "A10_H9") (pintype "bidirectional"))
      (node (ref "IC8") (pin "G2") (pinfunction "GPIO_EMC_23_G2") (pintype "bidirectional"))
    )
    (net (code "106") (name "/SDRAM_A11") (class "Default")
      (node (ref "IC3") (pin "G2") (pinfunction "A11_G2") (pintype "bidirectional"))
      (node (ref "IC8") (pin "B4") (pinfunction "GPIO_EMC_19_B4") (pintype "bidirectional"))
    )
    (net (code "107") (name "/SDRAM_A12") (class "Default")
      (node (ref "IC3") (pin "G1") (pinfunction "A12_G1") (pintype "bidirectional"))
      (node (ref "IC8") (pin "A3") (pinfunction "GPIO_EMC_20_A3") (pintype "bidirectional"))
    )
    (net (code "108") (name "/SDRAM_BA0") (class "Default")
      (node (ref "IC3") (pin "G7") (pinfunction "BA0_G7") (pintype "bidirectional"))
      (node (ref "IC8") (pin "C1") (pinfunction "GPIO_EMC_21_C1") (pintype "bidirectional"))
    )
    (net (code "109") (name "/SDRAM_BA1") (class "Default")
      (node (ref "IC3") (pin "G8") (pinfunction "BA1_G8") (pintype "bidirectional"))
      (node (ref "IC8") (pin "F1") (pinfunction "GPIO_EMC_22_F1") (pintype "bidirectional"))
    )
    (net (code "110") (name "/SDRAM_CAS") (class "Default")
      (node (ref "IC3") (pin "F7") (pinfunction "~{CAS}_F7") (pintype "bidirectional"))
      (node (ref "IC8") (pin "D3") (pinfunction "GPIO_EMC_24_D3") (pintype "bidirectional"))
    )
    (net (code "111") (name "/SDRAM_CKE") (class "Default")
      (node (ref "IC3") (pin "F3") (pinfunction "CKE_F3") (pintype "bidirectional"))
      (node (ref "IC8") (pin "A2") (pinfunction "GPIO_EMC_27_A2") (pintype "bidirectional"))
    )
    (net (code "112") (name "/SDRAM_CLK") (class "Default")
      (node (ref "IC3") (pin "F2") (pinfunction "CLK_F2") (pintype "bidirectional"))
      (node (ref "IC8") (pin "B3") (pinfunction "GPIO_EMC_26_B3") (pintype "bidirectional"))
    )
    (net (code "113") (name "/SDRAM_CS") (class "Default")
      (node (ref "IC3") (pin "G9") (pinfunction "~{CS}_G9") (pintype "bidirectional"))
      (node (ref "IC8") (pin "E1") (pinfunction "GPIO_EMC_29_E1") (pintype "bidirectional"))
      (node (ref "R18") (pin "2") (pinfunction "2_2") (pintype "passive"))
    )
    (net (code "114") (name "/SDRAM_DQ0") (class "Default")
      (node (ref "IC3") (pin "A8") (pinfunction "DQ0_A8") (pintype "bidirectional"))
      (node (ref "IC8") (pin "E3") (pinfunction "GPIO_EMC_00_E3") (pintype "bidirectional"))
    )
    (net (code "115") (name "/SDRAM_DQ1") (class "Default")
      (node (ref "IC3") (pin "B9") (pinfunction "DQ1_B9") (pintype "bidirectional"))
      (node (ref "IC8") (pin "F3") (pinfunction "GPIO_EMC_01_F3") (pintype "bidirectional"))
    )
    (net (code "116") (name "/SDRAM_DQ2") (class "Default")
      (node (ref "IC3") (pin "B8") (pinfunction "DQ2_B8") (pintype "bidirectional"))
      (node (ref "IC8") (pin "F4") (pinfunction "GPIO_EMC_02_F4") (pintype "bidirectional"))
    )
    (net (code "117") (name "/SDRAM_DQ3") (class "Default")
      (node (ref "IC3") (pin "C9") (pinfunction "DQ3_C9") (pintype "bidirectional"))
      (node (ref "IC8") (pin "G4") (pinfunction "GPIO_EMC_03_G4") (pintype "bidirectional"))
    )
    (net (code "118") (name "/SDRAM_DQ4") (class "Default")
      (node (ref "IC3") (pin "C8") (pinfunction "DQ4_C8") (pintype "bidirectional"))
      (node (ref "IC8") (pin "F2") (pinfunction "GPIO_EMC_04_F2") (pintype "bidirectional"))
    )
    (net (code "119") (name "/SDRAM_DQ5") (class "Default")
      (node (ref "IC3") (pin "D9") (pinfunction "DQ5_D9") (pintype "bidirectional"))
      (node (ref "IC8") (pin "G5") (pinfunction "GPIO_EMC_05_G5") (pintype "bidirectional"))
    )
    (net (code "120") (name "/SDRAM_DQ6") (class "Default")
      (node (ref "IC3") (pin "D8") (pinfunction "DQ6_D8") (pintype "bidirectional"))
      (node (ref "IC8") (pin "H5") (pinfunction "GPIO_EMC_06_H5") (pintype "bidirectional"))
    )
    (net (code "121") (name "/SDRAM_DQ7") (class "Default")
      (node (ref "IC3") (pin "E9") (pinfunction "DQ7_E9") (pintype "bidirectional"))
      (node (ref "IC8") (pin "H4") (pinfunction "GPIO_EMC_07_H4") (pintype "bidirectional"))
    )
    (net (code "122") (name "/SDRAM_DQ8") (class "Default")
      (node (ref "IC3") (pin "E1") (pinfunction "DQ8_E1") (pintype "bidirectional"))
      (node (ref "IC8") (pin "C6") (pinfunction "GPIO_EMC_30_C6") (pintype "bidirectional"))
    )
    (net (code "123") (name "/SDRAM_DQ9") (class "Default")
      (node (ref "IC3") (pin "D2") (pinfunction "DQ9_D2") (pintype "bidirectional"))
      (node (ref "IC8") (pin "C5") (pinfunction "GPIO_EMC_31_C5") (pintype "bidirectional"))
    )
    (net (code "124") (name "/SDRAM_DQ10") (class "Default")
      (node (ref "IC3") (pin "D1") (pinfunction "DQ10_D1") (pintype "bidirectional"))
      (node (ref "IC8") (pin "D5") (pinfunction "GPIO_EMC_32_D5") (pintype "bidirectional"))
    )
    (net (code "125") (name "/SDRAM_DQ11") (class "Default")
      (node (ref "IC3") (pin "C2") (pinfunction "DQ11_C2") (pintype "bidirectional"))
      (node (ref "IC8") (pin "C4") (pinfunction "GPIO_EMC_33_C4") (pintype "bidirectional"))
    )
    (net (code "126") (name "/SDRAM_DQ12") (class "Default")
      (node (ref "IC3") (pin "C1") (pinfunction "DQ12_C1") (pintype "bidirectional"))
      (node (ref "IC8") (pin "D4") (pinfunction "GPIO_EMC_34_D4") (pintype "bidirectional"))
    )
    (net (code "127") (name "/SDRAM_DQ13") (class "Default")
      (node (ref "IC3") (pin "B2") (pinfunction "DQ13_B2") (pintype "bidirectional"))
      (node (ref "IC8") (pin "E5") (pinfunction "GPIO_EMC_35_E5") (pintype "bidirectional"))
    )
    (net (code "128") (name "/SDRAM_DQ14") (class "Default")
      (node (ref "IC3") (pin "B1") (pinfunction "DQ14_B1") (pintype "bidirectional"))
      (node (ref "IC8") (pin "C3") (pinfunction "GPIO_EMC_36_C3") (pintype "bidirectional"))
    )
    (net (code "129") (name "/SDRAM_DQ15") (class "Default")
      (node (ref "IC3") (pin "A2") (pinfunction "DQ15_A2") (pintype "bidirectional"))
      (node (ref "IC8") (pin "E4") (pinfunction "GPIO_EMC_37_E4") (pintype "bidirectional"))
    )
    (net (code "130") (name "/SDRAM_DQMH") (class "Default")
      (node (ref "IC3") (pin "F1") (pinfunction "DQMH_F1") (pintype "bidirectional"))
      (node (ref "IC8") (pin "D6") (pinfunction "GPIO_EMC_38_D6") (pintype "bidirectional"))
    )
    (net (code "131") (name "/SDRAM_DQML") (class "Default")
      (node (ref "IC3") (pin "E8") (pinfunction "DQML_E8") (pintype "bidirectional"))
      (node (ref "IC8") (pin "H3") (pinfunction "GPIO_EMC_08_H3") (pintype "bidirectional"))
    )
    (net (code "132") (name "/SDRAM_RAS") (class "Default")
      (node (ref "IC3") (pin "F8") (pinfunction "~{RAS}_F8") (pintype "bidirectional"))
      (node (ref "IC8") (pin "D2") (pinfunction "GPIO_EMC_25_D2") (pintype "bidirectional"))
    )
    (net (code "133") (name "/SDRAM_WE") (class "Default")
      (node (ref "IC3") (pin "F9") (pinfunction "~{WE}_F9") (pintype "bidirectional"))
      (node (ref "IC8") (pin "D1") (pinfunction "GPIO_EMC_28_D1") (pintype "bidirectional"))
    )
    (net (code "134") (name "/SD_CD") (class "Default")
      (node (ref "D9") (pin "1") (pinfunction "1_1") (pintype "bidirectional"))
      (node (ref "IC8") (pin "L11") (pinfunction "GPIO_AD_B1_02_L11") (pintype "bidirectional"))
      (node (ref "J5") (pin "CD$1") (pinfunction "CD_CD$1") (pintype "power_in"))
      (node (ref "RN1") (pin "9") (pinfunction "9_9") (pintype "bidirectional"))
    )
    (net (code "135") (name "/SD_CLK") (class "Default")
      (node (ref "FL3") (pin "4") (pinfunction "INPUT_4_4") (pintype "bidirectional"))
      (node (ref "IC8") (pin "J3") (pinfunction "GPIO_SD_B0_01_J3") (pintype "bidirectional"))
    )
    (net (code "136") (name "/SD_CLK_INT") (class "Default")
      (node (ref "FL3") (pin "9") (pinfunction "OUTPUT_4_9") (pintype "bidirectional"))
      (node (ref "J5") (pin "P$5") (pinfunction "CLK_P$5") (pintype "bidirectional"))
    )
    (net (code "137") (name "/SD_CMD") (class "Default")
      (node (ref "FL3") (pin "3") (pinfunction "INPUT_3_3") (pintype "bidirectional"))
      (node (ref "IC8") (pin "J4") (pinfunction "GPIO_SD_B0_00_J4") (pintype "bidirectional"))
      (node (ref "RN1") (pin "12") (pinfunction "12_12") (pintype "bidirectional"))
    )
    (net (code "138") (name "/SD_CMD_INT") (class "Default")
      (node (ref "FL3") (pin "10") (pinfunction "OUTPUT_3_10") (pintype "bidirectional"))
      (node (ref "J5") (pin "P$3") (pinfunction "CMD_P$3") (pintype "bidirectional"))
    )
    (net (code "139") (name "/SD_DAT0") (class "Default")
      (node (ref "FL3") (pin "5") (pinfunction "INPUT_5_5") (pintype "bidirectional"))
      (node (ref "IC8") (pin "J1") (pinfunction "GPIO_SD_B0_02_J1") (pintype "bidirectional"))
      (node (ref "RN1") (pin "14") (pinfunction "14_14") (pintype "bidirectional"))
    )
    (net (code "140") (name "/SD_DAT0_INT") (class "Default")
      (node (ref "FL3") (pin "8") (pinfunction "OUTPUT_5_8") (pintype "bidirectional"))
      (node (ref "J5") (pin "P$7") (pinfunction "DAT0_P$7") (pintype "bidirectional"))
    )
    (net (code "141") (name "/SD_DAT1") (class "Default")
      (node (ref "FL3") (pin "6") (pinfunction "INPUT_6_6") (pintype "bidirectional"))
      (node (ref "IC8") (pin "K1") (pinfunction "GPIO_SD_B0_03_K1") (pintype "bidirectional"))
      (node (ref "RN1") (pin "13") (pinfunction "13_13") (pintype "bidirectional"))
    )
    (net (code "142") (name "/SD_DAT1_INT") (class "Default")
      (node (ref "FL3") (pin "7") (pinfunction "OUTPUT_6_7") (pintype "bidirectional"))
      (node (ref "J5") (pin "P$8") (pinfunction "DAT1_P$8") (pintype "bidirectional"))
    )
    (net (code "143") (name "/SD_DAT2") (class "Default")
      (node (ref "FL3") (pin "1") (pinfunction "INPUT_1_1") (pintype "bidirectional"))
      (node (ref "IC8") (pin "H2") (pinfunction "GPIO_SD_B0_04_H2") (pintype "bidirectional"))
      (node (ref "RN1") (pin "10") (pinfunction "10_10") (pintype "bidirectional"))
    )
    (net (code "144") (name "/SD_DAT2_INT") (class "Default")
      (node (ref "FL3") (pin "12") (pinfunction "OUTPUT_1_12") (pintype "bidirectional"))
      (node (ref "J5") (pin "P$1") (pinfunction "DAT2_P$1") (pintype "bidirectional"))
    )
    (net (code "145") (name "/SD_DAT3") (class "Default")
      (node (ref "FL3") (pin "2") (pinfunction "INPUT_2_2") (pintype "bidirectional"))
      (node (ref "IC8") (pin "J2") (pinfunction "GPIO_SD_B0_05_J2") (pintype "bidirectional"))
      (node (ref "RN1") (pin "11") (pinfunction "11_11") (pintype "bidirectional"))
    )
    (net (code "146") (name "/SD_DAT3_INT") (class "Default")
      (node (ref "FL3") (pin "11") (pinfunction "OUTPUT_2_11") (pintype "bidirectional"))
      (node (ref "J5") (pin "P$2") (pinfunction "DAT3/CD_P$2") (pintype "bidirectional"))
    )
    (net (code "147") (name "/S_FLASH_CE") (class "Default")
      (node (ref "IC6") (pin "1") (pinfunction "CE#_1") (pintype "bidirectional"))
      (node (ref "IC8") (pin "N3") (pinfunction "GPIO_SD_B1_05_N3") (pintype "bidirectional"))
      (node (ref "R14") (pin "2") (pinfunction "2_2") (pintype "passive"))
    )
    (net (code "148") (name "/S_FLASH_IO0") (class "Default")
      (node (ref "IC6") (pin "5") (pinfunction "SI_(IO0)_5") (pintype "bidirectional"))
      (node (ref "IC8") (pin "M4") (pinfunction "GPIO_SD_B1_03_M4") (pintype "bidirectional"))
    )
    (net (code "149") (name "/S_FLASH_IO1") (class "Default")
      (node (ref "IC6") (pin "2") (pinfunction "SO_(IO1)_2") (pintype "bidirectional"))
      (node (ref "IC8") (pin "M3") (pinfunction "GPIO_SD_B1_02_M3") (pintype "bidirectional"))
    )
    (net (code "150") (name "/S_FLASH_IO2") (class "Default")
      (node (ref "IC6") (pin "3") (pinfunction "WP#_(IO2)_3") (pintype "bidirectional"))
      (node (ref "IC8") (pin "M5") (pinfunction "GPIO_SD_B1_01_M5") (pintype "bidirectional"))
    )
    (net (code "151") (name "/S_FLASH_IO3") (class "Default")
      (node (ref "IC6") (pin "7") (pinfunction "HOLD#_(IO3)_7") (pintype "bidirectional"))
      (node (ref "IC8") (pin "L5") (pinfunction "GPIO_SD_B1_00_L5") (pintype "bidirectional"))
    )
    (net (code "152") (name "/S_FLASH_SCK") (class "Default")
      (node (ref "IC6") (pin "6") (pinfunction "SCK_6") (pintype "bidirectional"))
      (node (ref "IC8") (pin "P2") (pinfunction "GPIO_SD_B1_04_P2") (pintype "bidirectional"))
    )
    (net (code "153") (name "/USB_D_N") (class "Default")
      (node (ref "FL1") (pin "6") (pinfunction "D+_2_6") (pintype "bidirectional"))
      (node (ref "IC8") (pin "M8") (pinfunction "USB_OTG1_DN_M8") (pintype "bidirectional"))
    )
    (net (code "154") (name "/USB_D_P") (class "Default")
      (node (ref "FL1") (pin "7") (pinfunction "D-_2_7") (pintype "bidirectional"))
      (node (ref "IC8") (pin "L8") (pinfunction "USB_OTG1_DP_L8") (pintype "bidirectional"))
    )
    (net (code "155") (name "/VCC_SOC") (class "Default")
      (node (ref "C100") (pin "2") (pinfunction "2_2") (pintype "passive"))
      (node (ref "C103") (pin "2") (pinfunction "2_2") (pintype "passive"))
      (node (ref "C34") (pin "1") (pinfunction "1_1") (pintype "passive"))
      (node (ref "C38") (pin "1") (pinfunction "1_1") (pintype "passive"))
      (node (ref "C45") (pin "1") (pinfunction "1_1") (pintype "passive"))
      (node (ref "C46") (pin "2") (pinfunction "2_2") (pintype "passive"))
      (node (ref "C47") (pin "1") (pinfunction "1_1") (pintype "passive"))
      (node (ref "C48") (pin "1") (pinfunction "1_1") (pintype "passive"))
      (node (ref "C49") (pin "2") (pinfunction "2_2") (pintype "passive"))
      (node (ref "C87") (pin "2") (pinfunction "2_2") (pintype "passive"))
      (node (ref "C94") (pin "2") (pinfunction "2_2") (pintype "passive"))
      (node (ref "C97") (pin "2") (pinfunction "2_2") (pintype "passive"))
      (node (ref "C98") (pin "2") (pinfunction "2_2") (pintype "passive"))
      (node (ref "IC8") (pin "F6") (pinfunction "VDD_SOC_IN_1_F6") (pintype "bidirectional"))
      (node (ref "IC8") (pin "F7") (pinfunction "VDD_SOC_IN_2_F7") (pintype "bidirectional"))
      (node (ref "IC8") (pin "F8") (pinfunction "VDD_SOC_IN_3_F8") (pintype "bidirectional"))
      (node (ref "IC8") (pin "F9") (pinfunction "VDD_SOC_IN_4_F9") (pintype "bidirectional"))
      (node (ref "IC8") (pin "G6") (pinfunction "VDD_SOC_IN_5_G6") (pintype "bidirectional"))
      (node (ref "IC8") (pin "G9") (pinfunction "VDD_SOC_IN_6_G9") (pintype "bidirectional"))
      (node (ref "IC8") (pin "H6") (pinfunction "VDD_SOC_IN_7_H6") (pintype "bidirectional"))
      (node (ref "IC8") (pin "H9") (pinfunction "VDD_SOC_IN_8_H9") (pintype "bidirectional"))
      (node (ref "IC8") (pin "J5") (pinfunction "DCDC_SENSE_J5") (pintype "bidirectional"))
      (node (ref "IC8") (pin "J9") (pinfunction "VDD_SOC_IN_9_J9") (pintype "bidirectional"))
      (node (ref "L5") (pin "1") (pinfunction "1_1") (pintype "passive"))
    )
    (net (code "156") (name "/VDDA") (class "Default")
      (node (ref "C51") (pin "1") (pinfunction "1_1") (pintype "passive"))
      (node (ref "C52") (pin "2") (pinfunction "2_2") (pintype "passive"))
      (node (ref "J4") (pin "4") (pinfunction "4_4") (pintype "bidirectional"))
      (node (ref "L4") (pin "1") (pinfunction "1_1") (pintype "passive"))
    )
    (net (code "157") (name "/VDDA_ADC_3P3") (class "Default")
      (node (ref "C59") (pin "1") (pinfunction "1_1") (pintype "passive"))
      (node (ref "C60") (pin "2") (pinfunction "2_2") (pintype "passive"))
      (node (ref "C61") (pin "2") (pinfunction "2_2") (pintype "passive"))
      (node (ref "IC8") (pin "N14") (pinfunction "VDDA_ADC_3P3_N14") (pintype "bidirectional"))
      (node (ref "L6") (pin "1") (pinfunction "1_1") (pintype "passive"))
    )
    (net (code "158") (name "/VDD_HIGH_CAP") (class "Default")
      (node (ref "C101") (pin "2") (pinfunction "2_2") (pintype "passive"))
      (node (ref "C102") (pin "1") (pinfunction "1_1") (pintype "passive"))
      (node (ref "IC8") (pin "P8") (pinfunction "VDD_HIGH_CAP_P8") (pintype "bidirectional"))
    )
    (net (code "159") (name "/VDD_SNVS") (class "Default")
      (node (ref "C2") (pin "2") (pinfunction "2_2") (pintype "passive"))
      (node (ref "C69") (pin "1") (pinfunction "1_1") (pintype "passive"))
      (node (ref "IC8") (pin "M9") (pinfunction "VDD_SNVS_IN_M9") (pintype "bidirectional"))
      (node (ref "U1") (pin "1") (pinfunction "VOUT_1") (pintype "bidirectional"))
    )
    (net (code "160") (name "/VDD_SNVS_CAP") (class "Default")
      (node (ref "C70") (pin "1") (pinfunction "1_1") (pintype "passive"))
      (node (ref "IC8") (pin "M10") (pinfunction "VDD_SNVS_CAP_M10") (pintype "bidirectional"))
    )
    (net (code "161") (name "/VDD_USB_CAP") (class "Default")
      (node (ref "C71") (pin "1") (pinfunction "1_1") (pintype "passive"))
      (node (ref "C72") (pin "2") (pinfunction "2_2") (pintype "passive"))
      (node (ref "C73") (pin "2") (pinfunction "2_2") (pintype "passive"))
      (node (ref "IC8") (pin "K8") (pinfunction "VDD_USB_CAP_K8") (pintype "bidirectional"))
    )
    (net (code "162") (name "/WAKEUP") (class "Default")
      (node (ref "IC8") (pin "L6") (pinfunction "WAKEUP_L6") (pintype "bidirectional"))
      (node (ref "Q2") (pin "2") (pinfunction "S_2") (pintype "bidirectional"))
    )
    (net (code "163") (name "/WIFI_CLK") (class "Default")
      (node (ref "IC8") (pin "M13") (pinfunction "GPIO_AD_B1_09_M13") (pintype "bidirectional"))
      (node (ref "U3") (pin "20") (pinfunction "SDIO_CLK_20") (pintype "input"))
    )
    (net (code "164") (name "/WIFI_CMD") (class "Default")
      (node (ref "IC8") (pin "H13") (pinfunction "GPIO_AD_B1_08_H13") (pintype "bidirectional"))
      (node (ref "RN2") (pin "16") (pinfunction "16_16") (pintype "bidirectional"))
      (node (ref "U3") (pin "22") (pinfunction "SDIO_CMD_22") (pintype "bidirectional"))
    )
    (net (code "165") (name "/WIFI_D0") (class "Default")
      (node (ref "IC8") (pin "L12") (pinfunction "GPIO_AD_B1_04_L12") (pintype "bidirectional"))
      (node (ref "RN2") (pin "14") (pinfunction "14_14") (pintype "bidirectional"))
      (node (ref "U3") (pin "24") (pinfunction "SDIO_DATA_0_24") (pintype "bidirectional"))
    )
    (net (code "166") (name "/WIFI_D1") (class "Default")
      (node (ref "IC8") (pin "K12") (pinfunction "GPIO_AD_B1_05_K12") (pintype "bidirectional"))
      (node (ref "RN2") (pin "12") (pinfunction "12_12") (pintype "bidirectional"))
      (node (ref "U3") (pin "26") (pinfunction "SDIO_DATA_1_26") (pintype "bidirectional"))
    )
    (net (code "167") (name "/WIFI_D2") (class "Default")
      (node (ref "IC8") (pin "J12") (pinfunction "GPIO_AD_B1_06_J12") (pintype "bidirectional"))
      (node (ref "RN2") (pin "15") (pinfunction "15_15") (pintype "bidirectional"))
      (node (ref "U3") (pin "23") (pinfunction "SDIO_DATA_2_23") (pintype "bidirectional"))
    )
    (net (code "168") (name "/WIFI_D3") (class "Default")
      (node (ref "IC8") (pin "K10") (pinfunction "GPIO_AD_B1_07_K10") (pintype "bidirectional"))
      (node (ref "RN2") (pin "13") (pinfunction "13_13") (pintype "bidirectional"))
      (node (ref "U3") (pin "25") (pinfunction "SDIO_DATA_3_25") (pintype "bidirectional"))
    )
    (net (code "169") (name "/WL_H_WAKE") (class "Default")
      (node (ref "IC8") (pin "E11") (pinfunction "GPIO_B0_15_E11") (pintype "bidirectional"))
      (node (ref "U3") (pin "27") (pinfunction "WL_GPIO_0_HOST_WAKE_27") (pintype "bidirectional"))
    )
    (net (code "170") (name "/WL_REG_ON") (class "Default")
      (node (ref "IC8") (pin "E10") (pinfunction "GPIO_B0_14_E10") (pintype "bidirectional"))
      (node (ref "U3") (pin "28") (pinfunction "WL_REG_ON_28") (pintype "input"))
    )
    (net (code "171") (name "/XTALI") (class "Default")
      (node (ref "C106") (pin "1") (pinfunction "1_1") (pintype "passive"))
      (node (ref "IC8") (pin "P11") (pinfunction "XTALI_P11") (pintype "bidirectional"))
      (node (ref "R40") (pin "1") (pinfunction "1_1") (pintype "passive"))
      (node (ref "Y2") (pin "3") (pinfunction "CRYSTAL_2_3") (pintype "bidirectional"))
    )
    (net (code "172") (name "/XTALO") (class "Default")
      (node (ref "C105") (pin "1") (pinfunction "1_1") (pintype "passive"))
      (node (ref "IC8") (pin "N11") (pinfunction "XTALO_N11") (pintype "bidirectional"))
      (node (ref "Y2") (pin "1") (pinfunction "CRYSTAL_1_1") (pintype "bidirectional"))
    )
    (net (code "173") (name "GND") (class "Default")
      (node (ref "C1") (pin "1") (pinfunction "1_1") (pintype "passive"))
      (node (ref "C10") (pin "1") (pinfunction "1_1") (pintype "passive"))
      (node (ref "C100") (pin "1") (pinfunction "1_1") (pintype "passive"))
      (node (ref "C101") (pin "1") (pinfunction "1_1") (pintype "passive"))
      (node (ref "C102") (pin "2") (pinfunction "2_2") (pintype "passive"))
      (node (ref "C103") (pin "1") (pinfunction "1_1") (pintype "passive"))
      (node (ref "C104") (pin "1") (pinfunction "1_1") (pintype "passive"))
      (node (ref "C105") (pin "2") (pinfunction "2_2") (pintype "passive"))
      (node (ref "C106") (pin "2") (pinfunction "2_2") (pintype "passive"))
      (node (ref "C107") (pin "2") (pinfunction "2_2") (pintype "passive"))
      (node (ref "C108") (pin "1") (pinfunction "1_1") (pintype "passive"))
      (node (ref "C109") (pin "2") (pinfunction "2_2") (pintype "passive"))
      (node (ref "C11") (pin "1") (pinfunction "1_1") (pintype "passive"))
      (node (ref "C110") (pin "1") (pinfunction "1_1") (pintype "passive"))
      (node (ref "C12") (pin "2") (pinfunction "2_2") (pintype "passive"))
      (node (ref "C13") (pin "2") (pinfunction "2_2") (pintype "passive"))
      (node (ref "C14") (pin "2") (pinfunction "2_2") (pintype "passive"))
      (node (ref "C15") (pin "2") (pinfunction "2_2") (pintype "passive"))
      (node (ref "C16") (pin "2") (pinfunction "2_2") (pintype "passive"))
      (node (ref "C17") (pin "1") (pinfunction "1_1") (pintype "passive"))
      (node (ref "C18") (pin "1") (pinfunction "1_1") (pintype "passive"))
      (node (ref "C19") (pin "2") (pinfunction "2_2") (pintype "passive"))
      (node (ref "C2") (pin "1") (pinfunction "1_1") (pintype "passive"))
      (node (ref "C20") (pin "2") (pinfunction "2_2") (pintype "passive"))
      (node (ref "C21") (pin "1") (pinfunction "1_1") (pintype "passive"))
      (node (ref "C22") (pin "2") (pinfunction "2_2") (pintype "passive"))
      (node (ref "C23") (pin "1") (pinfunction "1_1") (pintype "passive"))
      (node (ref "C24") (pin "2") (pinfunction "2_2") (pintype "passive"))
      (node (ref "C25") (pin "1") (pinfunction "1_1") (pintype "passive"))
      (node (ref "C26") (pin "2") (pinfunction "2_2") (pintype "passive"))
      (node (ref "C27") (pin "1") (pinfunction "1_1") (pintype "passive"))
      (node (ref "C28") (pin "2") (pinfunction "2_2") (pintype "passive"))
      (node (ref "C29") (pin "2") (pinfunction "2_2") (pintype "passive"))
      (node (ref "C3") (pin "1") (pinfunction "1_1") (pintype "passive"))
      (node (ref "C30") (pin "2") (pinfunction "2_2") (pintype "passive"))
      (node (ref "C31") (pin "1") (pinfunction "1_1") (pintype "passive"))
      (node (ref "C32") (pin "2") (pinfunction "2_2") (pintype "passive"))
      (node (ref "C33") (pin "1") (pinfunction "1_1") (pintype "passive"))
      (node (ref "C34") (pin "2") (pinfunction "2_2") (pintype "passive"))
      (node (ref "C35") (pin "1") (pinfunction "1_1") (pintype "passive"))
      (node (ref "C36") (pin "2") (pinfunction "2_2") (pintype "passive"))
      (node (ref "C37") (pin "2") (pinfunction "2_2") (pintype "passive"))
      (node (ref "C38") (pin "2") (pinfunction "2_2") (pintype "passive"))
      (node (ref "C39") (pin "1") (pinfunction "1_1") (pintype "passive"))
      (node (ref "C4") (pin "1") (pinfunction "1_1") (pintype "passive"))
      (node (ref "C40") (pin "1") (pinfunction "1_1") (pintype "passive"))
      (node (ref "C41") (pin "1") (pinfunction "1_1") (pintype "passive"))
      (node (ref "C42") (pin "1") (pinfunction "1_1") (pintype "passive"))
      (node (ref "C43") (pin "2") (pinfunction "2_2") (pintype "passive"))
      (node (ref "C44") (pin "1") (pinfunction "1_1") (pintype "passive"))
      (node (ref "C45") (pin "2") (pinfunction "2_2") (pintype "passive"))
      (node (ref "C46") (pin "1") (pinfunction "1_1") (pintype "passive"))
      (node (ref "C47") (pin "2") (pinfunction "2_2") (pintype "passive"))
      (node (ref "C48") (pin "2") (pinfunction "2_2") (pintype "passive"))
      (node (ref "C49") (pin "1") (pinfunction "1_1") (pintype "passive"))
      (node (ref "C5") (pin "1") (pinfunction "1_1") (pintype "passive"))
      (node (ref "C50") (pin "2") (pinfunction "2_2") (pintype "passive"))
      (node (ref "C51") (pin "2") (pinfunction "2_2") (pintype "passive"))
      (node (ref "C52") (pin "1") (pinfunction "1_1") (pintype "passive"))
      (node (ref "C53") (pin "2") (pinfunction "2_2") (pintype "passive"))
      (node (ref "C54") (pin "2") (pinfunction "2_2") (pintype "passive"))
      (node (ref "C55") (pin "2") (pinfunction "2_2") (pintype "passive"))
      (node (ref "C56") (pin "2") (pinfunction "2_2") (pintype "passive"))
      (node (ref "C57") (pin "1") (pinfunction "1_1") (pintype "passive"))
      (node (ref "C58") (pin "1") (pinfunction "1_1") (pintype "passive"))
      (node (ref "C59") (pin "2") (pinfunction "2_2") (pintype "passive"))
      (node (ref "C6") (pin "2") (pinfunction "2_2") (pintype "passive"))
      (node (ref "C60") (pin "1") (pinfunction "1_1") (pintype "passive"))
      (node (ref "C61") (pin "1") (pinfunction "1_1") (pintype "passive"))
      (node (ref "C62") (pin "2") (pinfunction "2_2") (pintype "passive"))
      (node (ref "C63") (pin "2") (pinfunction "2_2") (pintype "passive"))
      (node (ref "C64") (pin "2") (pinfunction "2_2") (pintype "passive"))
      (node (ref "C65") (pin "1") (pinfunction "1_1") (pintype "passive"))
      (node (ref "C66") (pin "1") (pinfunction "1_1") (pintype "passive"))
      (node (ref "C67") (pin "2") (pinfunction "2_2") (pintype "passive"))
      (node (ref "C68") (pin "1") (pinfunction "1_1") (pintype "passive"))
      (node (ref "C69") (pin "2") (pinfunction "2_2") (pintype "passive"))
      (node (ref "C7") (pin "2") (pinfunction "2_2") (pintype "passive"))
      (node (ref "C70") (pin "2") (pinfunction "2_2") (pintype "passive"))
      (node (ref "C71") (pin "2") (pinfunction "2_2") (pintype "passive"))
      (node (ref "C72") (pin "1") (pinfunction "1_1") (pintype "passive"))
      (node (ref "C73") (pin "1") (pinfunction "1_1") (pintype "passive"))
      (node (ref "C74") (pin "2") (pinfunction "2_2") (pintype "passive"))
      (node (ref "C75") (pin "2") (pinfunction "2_2") (pintype "passive"))
      (node (ref "C76") (pin "2") (pinfunction "2_2") (pintype "passive"))
      (node (ref "C77") (pin "2") (pinfunction "2_2") (pintype "bidirectional"))
      (node (ref "C78") (pin "2") (pinfunction "2_2") (pintype "bidirectional"))
      (node (ref "C79") (pin "2") (pinfunction "2_2") (pintype "passive"))
      (node (ref "C8") (pin "1") (pinfunction "1_1") (pintype "passive"))
      (node (ref "C80") (pin "2") (pinfunction "2_2") (pintype "passive"))
      (node (ref "C81") (pin "1") (pinfunction "1_1") (pintype "passive"))
      (node (ref "C82") (pin "2") (pinfunction "2_2") (pintype "passive"))
      (node (ref "C83") (pin "1") (pinfunction "1_1") (pintype "passive"))
      (node (ref "C84") (pin "2") (pinfunction "2_2") (pintype "passive"))
      (node (ref "C85") (pin "2") (pinfunction "2_2") (pintype "passive"))
      (node (ref "C86") (pin "1") (pinfunction "1_1") (pintype "passive"))
      (node (ref "C87") (pin "1") (pinfunction "1_1") (pintype "passive"))
      (node (ref "C88") (pin "2") (pinfunction "2_2") (pintype "passive"))
      (node (ref "C89") (pin "2") (pinfunction "2_2") (pintype "passive"))
      (node (ref "C9") (pin "1") (pinfunction "1_1") (pintype "passive"))
      (node (ref "C90") (pin "1") (pinfunction "1_1") (pintype "passive"))
      (node (ref "C91") (pin "1") (pinfunction "1_1") (pintype "passive"))
      (node (ref "C92") (pin "1") (pinfunction "1_1") (pintype "passive"))
      (node (ref "C93") (pin "1") (pinfunction "1_1") (pintype "passive"))
      (node (ref "C94") (pin "1") (pinfunction "1_1") (pintype "passive"))
      (node (ref "C95") (pin "1") (pinfunction "1_1") (pintype "passive"))
      (node (ref "C96") (pin "2") (pinfunction "2_2") (pintype "passive"))
      (node (ref "C97") (pin "1") (pinfunction "1_1") (pintype "passive"))
      (node (ref "C98") (pin "1") (pinfunction "1_1") (pintype "passive"))
      (node (ref "C99") (pin "1") (pinfunction "1_1") (pintype "passive"))
      (node (ref "CN1") (pin "2") (pinfunction "1_2") (pintype "passive"))
      (node (ref "D10") (pin "2") (pinfunction "2_2") (pintype "bidirectional"))
      (node (ref "D2") (pin "2") (pinfunction "2_2") (pintype "bidirectional"))
      (node (ref "D4") (pin "2") (pinfunction "2_2") (pintype "bidirectional"))
      (node (ref "D5") (pin "2") (pinfunction "2_2") (pintype "bidirectional"))
      (node (ref "D6") (pin "2") (pinfunction "2_2") (pintype "bidirectional"))
      (node (ref "D7") (pin "2") (pinfunction "2_2") (pintype "bidirectional"))
      (node (ref "D8") (pin "2") (pinfunction "2_2") (pintype "bidirectional"))
      (node (ref "D9") (pin "2") (pinfunction "2_2") (pintype "bidirectional"))
      (node (ref "FL1") (pin "5") (pinfunction "GND_1_5") (pintype "bidirectional"))
      (node (ref "FL1") (pin "8") (pinfunction "GND_2_8") (pintype "bidirectional"))
      (node (ref "FL2") (pin "13") (pinfunction "EP_13") (pintype "bidirectional"))
      (node (ref "FL3") (pin "13") (pinfunction "EP_13") (pintype "bidirectional"))
      (node (ref "FL4") (pin "13") (pinfunction "EP_13") (pintype "bidirectional"))
      (node (ref "FL5") (pin "13") (pinfunction "EP_13") (pintype "bidirectional"))
      (node (ref "IC1") (pin "1") (pinfunction "GND_1_1") (pintype "bidirectional"))
      (node (ref "IC1") (pin "4") (pinfunction "~{ON}_4") (pintype "bidirectional"))
      (node (ref "IC1") (pin "5") (pinfunction "GND_2_5") (pintype "bidirectional"))
      (node (ref "IC2") (pin "2") (pinfunction "GND_2") (pintype "bidirectional"))
      (node (ref "IC3") (pin "A1") (pinfunction "VSS_1_A1") (pintype "bidirectional"))
      (node (ref "IC3") (pin "A3") (pinfunction "VSSQ_1_A3") (pintype "bidirectional"))
      (node (ref "IC3") (pin "B7") (pinfunction "VSSQ_2_B7") (pintype "bidirectional"))
      (node (ref "IC3") (pin "C3") (pinfunction "VSSQ_3_C3") (pintype "bidirectional"))
      (node (ref "IC3") (pin "D7") (pinfunction "VSSQ_4_D7") (pintype "bidirectional"))
      (node (ref "IC3") (pin "E3") (pinfunction "VSS_2_E3") (pintype "bidirectional"))
      (node (ref "IC3") (pin "J1") (pinfunction "VSS_3_J1") (pintype "bidirectional"))
      (node (ref "IC4") (pin "4") (pinfunction "GND_4") (pintype "bidirectional"))
      (node (ref "IC4") (pin "9") (pinfunction "EP_9") (pintype "bidirectional"))
      (node (ref "IC5") (pin "4") (pinfunction "GND_4") (pintype "bidirectional"))
      (node (ref "IC5") (pin "9") (pinfunction "EP_9") (pintype "bidirectional"))
      (node (ref "IC6") (pin "4") (pinfunction "GND_4") (pintype "bidirectional"))
      (node (ref "IC6") (pin "9") (pinfunction "EP_9") (pintype "bidirectional"))
      (node (ref "IC7") (pin "3") (pinfunction "GND_3") (pintype "bidirectional"))
      (node (ref "IC8") (pin "A1") (pinfunction "VSS_1_A1") (pintype "bidirectional"))
      (node (ref "IC8") (pin "A14") (pinfunction "VSS_2_A14") (pintype "bidirectional"))
      (node (ref "IC8") (pin "B10") (pinfunction "VSS_4_B10") (pintype "bidirectional"))
      (node (ref "IC8") (pin "B5") (pinfunction "VSS_3_B5") (pintype "bidirectional"))
      (node (ref "IC8") (pin "E13") (pinfunction "VSS_6_E13") (pintype "bidirectional"))
      (node (ref "IC8") (pin "E2") (pinfunction "VSS_5_E2") (pintype "bidirectional"))
      (node (ref "IC8") (pin "G7") (pinfunction "VSS_7_G7") (pintype "bidirectional"))
      (node (ref "IC8") (pin "G8") (pinfunction "VSS_8_G8") (pintype "bidirectional"))
      (node (ref "IC8") (pin "H7") (pinfunction "VSS_9_H7") (pintype "bidirectional"))
      (node (ref "IC8") (pin "H8") (pinfunction "VSS_10_H8") (pintype "bidirectional"))
      (node (ref "IC8") (pin "J7") (pinfunction "VSS_11_J7") (pintype "bidirectional"))
      (node (ref "IC8") (pin "J8") (pinfunction "VSS_12_J8") (pintype "bidirectional"))
      (node (ref "IC8") (pin "K13") (pinfunction "VSS_14_K13") (pintype "bidirectional"))
      (node (ref "IC8") (pin "K2") (pinfunction "VSS_13_K2") (pintype "bidirectional"))
      (node (ref "IC8") (pin "K6") (pinfunction "TEST_MODE_K6") (pintype "bidirectional"))
      (node (ref "IC8") (pin "K9") (pinfunction "NGND_KEL0_K9") (pintype "bidirectional"))
      (node (ref "IC8") (pin "L9") (pinfunction "VSS_15_L9") (pintype "bidirectional"))
      (node (ref "IC8") (pin "N1") (pinfunction "DCDC_GND_1_N1") (pintype "bidirectional"))
      (node (ref "IC8") (pin "N2") (pinfunction "DCDC_GND_2_N2") (pintype "bidirectional"))
      (node (ref "IC8") (pin "N5") (pinfunction "VSS_16_N5") (pintype "bidirectional"))
      (node (ref "IC8") (pin "N8") (pinfunction "VSS_17_N8") (pintype "bidirectional"))
      (node (ref "IC8") (pin "P1") (pinfunction "VSS_18_P1") (pintype "bidirectional"))
      (node (ref "IC8") (pin "P14") (pinfunction "VSS_19_P14") (pintype "bidirectional"))
      (node (ref "IC9") (pin "22") (pinfunction "GND_1_22") (pintype "bidirectional"))
      (node (ref "IC9") (pin "25") (pinfunction "GND_2_25") (pintype "bidirectional"))
      (node (ref "J1") (pin "A1_B12") (pinfunction "GND_A1_B12") (pintype "power_in"))
      (node (ref "J1") (pin "B1_A12") (pinfunction "GND_B1_A12") (pintype "power_in"))
      (node (ref "J3") (pin "1") (pinfunction "1_1") (pintype "passive"))
      (node (ref "J4") (pin "19") (pinfunction "19_19") (pintype "bidirectional"))
      (node (ref "J4") (pin "27") (pinfunction "27_27") (pintype "bidirectional"))
      (node (ref "J4") (pin "5") (pinfunction "5_5") (pintype "bidirectional"))
      (node (ref "J5") (pin "CD$2") (pinfunction "CD_POL_CD$2") (pintype "power_in"))
      (node (ref "J5") (pin "G$1") (pinfunction "SHD_G$1") (pintype "power_in"))
      (node (ref "J5") (pin "G$2") (pinfunction "SHD_G$2") (pintype "power_in"))
      (node (ref "J5") (pin "G$3") (pinfunction "SHD_G$3") (pintype "power_in"))
      (node (ref "J5") (pin "G$4") (pinfunction "SHD_G$4") (pintype "power_in"))
      (node (ref "J5") (pin "P$6") (pinfunction "VSS_P$6") (pintype "power_in"))
      (node (ref "J6") (pin "1") (pinfunction "1_1") (pintype "passive"))
      (node (ref "J7") (pin "2") (pinfunction "GND_1_2") (pintype "bidirectional"))
      (node (ref "J7") (pin "3") (pinfunction "GND_2_3") (pintype "bidirectional"))
      (node (ref "J8") (pin "3") (pinfunction "3_3") (pintype "passive"))
      (node (ref "J8") (pin "5") (pinfunction "5_5") (pintype "passive"))
      (node (ref "Q6") (pin "1") (pinfunction "G_1") (pintype "bidirectional"))
      (node (ref "R10") (pin "2") (pinfunction "2_2") (pintype "passive"))
      (node (ref "R11") (pin "2") (pinfunction "2_2") (pintype "passive"))
      (node (ref "R12") (pin "2") (pinfunction "2_2") (pintype "passive"))
      (node (ref "R27") (pin "2") (pinfunction "2_2") (pintype "passive"))
      (node (ref "R37") (pin "2") (pinfunction "2_2") (pintype "passive"))
      (node (ref "R38") (pin "2") (pinfunction "2_2") (pintype "passive"))
      (node (ref "R40") (pin "2") (pinfunction "2_2") (pintype "passive"))
      (node (ref "R41") (pin "2") (pinfunction "2_2") (pintype "passive"))
      (node (ref "R6") (pin "2") (pinfunction "2_2") (pintype "passive"))
      (node (ref "R7") (pin "2") (pinfunction "2_2") (pintype "passive"))
      (node (ref "R8") (pin "1") (pinfunction "1_1") (pintype "passive"))
      (node (ref "R9") (pin "2") (pinfunction "2_2") (pintype "passive"))
      (node (ref "U1") (pin "2") (pinfunction "GND_2") (pintype "bidirectional"))
      (node (ref "U1") (pin "EP") (pinfunction "GND_EP") (pintype "bidirectional"))
      (node (ref "U2") (pin "15") (pinfunction "SYSOFF_15") (pintype "input"))
      (node (ref "U2") (pin "17") (pinfunction "EXP_17") (pintype "power_in"))
      (node (ref "U2") (pin "4") (pinfunction "~{CE}_4") (pintype "input"))
      (node (ref "U2") (pin "6") (pinfunction "EN1_6") (pintype "input"))
      (node (ref "U2") (pin "8") (pinfunction "VSS_8") (pintype "power_in"))
      (node (ref "U3") (pin "1") (pinfunction "GND_1") (pintype "power_in"))
      (node (ref "U3") (pin "12") (pinfunction "GND_12") (pintype "power_in"))
      (node (ref "U3") (pin "19") (pinfunction "GND_19") (pintype "power_in"))
      (node (ref "U3") (pin "21") (pinfunction "GND_21") (pintype "power_in"))
      (node (ref "U3") (pin "29") (pinfunction "GND_29") (pintype "power_in"))
      (node (ref "U3") (pin "32") (pinfunction "GND_(SR_PVSS)_32") (pintype "power_in"))
      (node (ref "U3") (pin "33") (pinfunction "GND_(SR_PVSS)_33") (pintype "power_in"))
      (node (ref "U3") (pin "35") (pinfunction "GND_35") (pintype "power_in"))
      (node (ref "U3") (pin "37") (pinfunction "LPO_IN_(32KHZ)_37") (pintype "input"))
      (node (ref "U3") (pin "4") (pinfunction "~{BT_UART_CTS_N}_4") (pintype "input"))
      (node (ref "U3") (pin "40") (pinfunction "GND_40") (pintype "power_in"))
      (node (ref "U3") (pin "42") (pinfunction "GND_42") (pintype "power_in"))
      (node (ref "U3") (pin "43") (pinfunction "GND_43") (pintype "power_in"))
      (node (ref "U3") (pin "44") (pinfunction "GND_44") (pintype "power_in"))
      (node (ref "U3") (pin "45") (pinfunction "GND_45") (pintype "power_in"))
      (node (ref "U3") (pin "46") (pinfunction "GND_46") (pintype "power_in"))
      (node (ref "Y2") (pin "2") (pinfunction "NC_1_2") (pintype "bidirectional"))
      (node (ref "Y2") (pin "4") (pinfunction "NC_2_4") (pintype "bidirectional"))
    )
    (net (code "174") (name "Net-(ANT1-FEED)") (class "Default")
      (node (ref "ANT1") (pin "1") (pinfunction "FEED_1") (pintype "input"))
      (node (ref "C78") (pin "1") (pinfunction "1_1") (pintype "bidirectional"))
      (node (ref "L7") (pin "1") (pinfunction "1_1") (pintype "passive"))
    )
    (net (code "175") (name "Net-(C110-Pad2)") (class "Default")
      (node (ref "C110") (pin "2") (pinfunction "2_2") (pintype "passive"))
      (node (ref "J1") (pin "S1") (pinfunction "SHELL_GND_S1") (pintype "power_in"))
      (node (ref "J1") (pin "S2") (pinfunction "SHELL_GND_S2") (pintype "power_in"))
      (node (ref "J1") (pin "S3") (pinfunction "SHELL_GND_S3") (pintype "power_in"))
      (node (ref "J1") (pin "S4") (pinfunction "SHELL_GND_S4") (pintype "power_in"))
      (node (ref "R41") (pin "1") (pinfunction "1_1") (pintype "passive"))
    )
    (net (code "176") (name "Net-(CN1-2)") (class "Default")
      (node (ref "C8") (pin "2") (pinfunction "2_2") (pintype "passive"))
      (node (ref "CN1") (pin "1") (pinfunction "2_1") (pintype "passive"))
      (node (ref "D2") (pin "1") (pinfunction "1_1") (pintype "bidirectional"))
      (node (ref "U2") (pin "2") (pinfunction "BAT_2_2") (pintype "bidirectional"))
      (node (ref "U2") (pin "3") (pinfunction "BAT_3_3") (pintype "bidirectional"))
    )
    (net (code "177") (name "Net-(D1-BLUE)") (class "Default")
      (node (ref "D1") (pin "1") (pinfunction "BLUE_1") (pintype "passive"))
      (node (ref "R5") (pin "2") (pinfunction "2_2") (pintype "passive"))
    )
    (net (code "178") (name "Net-(D3-BLUE)") (class "Default")
      (node (ref "D3") (pin "1") (pinfunction "BLUE_1") (pintype "passive"))
      (node (ref "R19") (pin "2") (pinfunction "2_2") (pintype "passive"))
    )
    (net (code "179") (name "Net-(D3-GREEN)") (class "Default")
      (node (ref "D3") (pin "2") (pinfunction "GREEN_2") (pintype "passive"))
      (node (ref "R20") (pin "2") (pinfunction "2_2") (pintype "passive"))
    )
    (net (code "180") (name "Net-(D3-RED)") (class "Default")
      (node (ref "D3") (pin "3") (pinfunction "RED_3") (pintype "passive"))
      (node (ref "R21") (pin "2") (pinfunction "2_2") (pintype "passive"))
    )
    (net (code "181") (name "Net-(FL1-D+_1)") (class "Default")
      (node (ref "FL1") (pin "3") (pinfunction "D+_1_3") (pintype "bidirectional"))
      (node (ref "J1") (pin "A7") (pinfunction "DN1_A7") (pintype "bidirectional"))
      (node (ref "J1") (pin "B7") (pinfunction "DN2_B7") (pintype "bidirectional"))
    )
    (net (code "182") (name "Net-(FL1-D-_1)") (class "Default")
      (node (ref "FL1") (pin "2") (pinfunction "D-_1_2") (pintype "bidirectional"))
      (node (ref "J1") (pin "A6") (pinfunction "DP1_A6") (pintype "bidirectional"))
      (node (ref "J1") (pin "B6") (pinfunction "DP2_B6") (pintype "bidirectional"))
    )
    (net (code "183") (name "Net-(FL1-ID)") (class "Default")
      (node (ref "FL1") (pin "4") (pinfunction "ID_4") (pintype "bidirectional"))
      (node (ref "J1") (pin "A4_B9") (pinfunction "VBUS_A4_B9") (pintype "power_in"))
      (node (ref "J1") (pin "B4_A9") (pinfunction "VBUS_B4_A9") (pintype "power_in"))
      (node (ref "L1") (pin "1") (pinfunction "1_1") (pintype "passive"))
    )
    (net (code "184") (name "Net-(FL2-OUTPUT_1)") (class "Default")
      (node (ref "FL2") (pin "12") (pinfunction "OUTPUT_1_12") (pintype "bidirectional"))
      (node (ref "J2") (pin "8") (pinfunction "8_8") (pintype "passive"))
    )
    (net (code "185") (name "Net-(FL2-OUTPUT_2)") (class "Default")
      (node (ref "FL2") (pin "11") (pinfunction "OUTPUT_2_11") (pintype "bidirectional"))
      (node (ref "J2") (pin "7") (pinfunction "7_7") (pintype "passive"))
    )
    (net (code "186") (name "Net-(FL2-OUTPUT_3)") (class "Default")
      (node (ref "FL2") (pin "10") (pinfunction "OUTPUT_3_10") (pintype "bidirectional"))
      (node (ref "J2") (pin "6") (pinfunction "6_6") (pintype "passive"))
    )
    (net (code "187") (name "Net-(FL2-OUTPUT_4)") (class "Default")
      (node (ref "FL2") (pin "9") (pinfunction "OUTPUT_4_9") (pintype "bidirectional"))
      (node (ref "J2") (pin "5") (pinfunction "5_5") (pintype "passive"))
    )
    (net (code "188") (name "Net-(FL2-OUTPUT_5)") (class "Default")
      (node (ref "FL2") (pin "8") (pinfunction "OUTPUT_5_8") (pintype "bidirectional"))
      (node (ref "J2") (pin "4") (pinfunction "4_4") (pintype "passive"))
    )
    (net (code "189") (name "Net-(FL2-OUTPUT_6)") (class "Default")
      (node (ref "FL2") (pin "7") (pinfunction "OUTPUT_6_7") (pintype "bidirectional"))
      (node (ref "J2") (pin "3") (pinfunction "3_3") (pintype "passive"))
    )
    (net (code "190") (name "Net-(FL4-OUTPUT_1)") (class "Default")
      (node (ref "FL4") (pin "12") (pinfunction "OUTPUT_1_12") (pintype "bidirectional"))
      (node (ref "J2") (pin "2") (pinfunction "2_2") (pintype "passive"))
    )
    (net (code "191") (name "Net-(FL5-OUTPUT_6)") (class "Default")
      (node (ref "FL5") (pin "7") (pinfunction "OUTPUT_6_7") (pintype "bidirectional"))
      (node (ref "J8") (pin "9") (pinfunction "9_9") (pintype "passive"))
    )
    (net (code "192") (name "Net-(IC1-ST)") (class "Default")
      (node (ref "IC1") (pin "8") (pinfunction "ST_8") (pintype "bidirectional"))
      (node (ref "R5") (pin "1") (pinfunction "1_1") (pintype "passive"))
    )
    (net (code "193") (name "Net-(IC1-VIN2)") (class "Default")
      (node (ref "C5") (pin "2") (pinfunction "2_2") (pintype "passive"))
      (node (ref "IC1") (pin "6") (pinfunction "VIN2_6") (pintype "bidirectional"))
      (node (ref "Q6") (pin "2") (pinfunction "S_2") (pintype "bidirectional"))
    )
    (net (code "194") (name "Net-(IC2-EN)") (class "Default")
      (node (ref "IC2") (pin "5") (pinfunction "EN_5") (pintype "bidirectional"))
      (node (ref "Q1") (pin "3") (pinfunction "D_3") (pintype "bidirectional"))
      (node (ref "R3") (pin "1") (pinfunction "1_1") (pintype "passive"))
    )
    (net (code "195") (name "Net-(IC2-FB)") (class "Default")
      (node (ref "IC2") (pin "1") (pinfunction "FB_1") (pintype "bidirectional"))
      (node (ref "R2") (pin "1") (pinfunction "1_1") (pintype "passive"))
      (node (ref "R8") (pin "2") (pinfunction "2_2") (pintype "passive"))
    )
    (net (code "196") (name "Net-(IC2-SW)") (class "Default")
      (node (ref "IC2") (pin "4") (pinfunction "SW_4") (pintype "bidirectional"))
      (node (ref "L2") (pin "1") (pinfunction "1_1") (pintype "passive"))
    )
    (net (code "197") (name "Net-(IC9-LED0_{slash}_ANEN_SPEED)") (class "Default")
      (node (ref "IC9") (pin "23") (pinfunction "LED0_/_ANEN_SPEED_23") (pintype "bidirectional"))
      (node (ref "R35") (pin "1") (pinfunction "1_1") (pintype "passive"))
    )
    (net (code "198") (name "Net-(IC9-REXT)") (class "Default")
      (node (ref "IC9") (pin "9") (pinfunction "REXT_9") (pintype "bidirectional"))
      (node (ref "R38") (pin "1") (pinfunction "1_1") (pintype "passive"))
    )
    (net (code "199") (name "Net-(IC9-VDDA_3.3)") (class "Default")
      (node (ref "C81") (pin "2") (pinfunction "2_2") (pintype "passive"))
      (node (ref "C82") (pin "1") (pinfunction "1_1") (pintype "passive"))
      (node (ref "C85") (pin "1") (pinfunction "1_1") (pintype "passive"))
      (node (ref "IC9") (pin "2") (pinfunction "VDDA_3.3_2") (pintype "bidirectional"))
      (node (ref "L8") (pin "1") (pinfunction "1_1") (pintype "passive"))
    )
    (net (code "200") (name "Net-(IC9-VDD_1.2)") (class "Default")
      (node (ref "C83") (pin "2") (pinfunction "2_2") (pintype "passive"))
      (node (ref "C84") (pin "1") (pinfunction "1_1") (pintype "passive"))
      (node (ref "IC9") (pin "1") (pinfunction "VDD_1.2_1") (pintype "bidirectional"))
    )
    (net (code "201") (name "Net-(J1-CC1)") (class "Default")
      (node (ref "J1") (pin "A5") (pinfunction "CC1_A5") (pintype "bidirectional"))
      (node (ref "R6") (pin "1") (pinfunction "1_1") (pintype "passive"))
    )
    (net (code "202") (name "Net-(J1-CC2)") (class "Default")
      (node (ref "J1") (pin "B5") (pinfunction "CC2_B5") (pintype "bidirectional"))
      (node (ref "R7") (pin "1") (pinfunction "1_1") (pintype "passive"))
    )
    (net (code "203") (name "Net-(J7-SIGNAL)") (class "Default")
      (node (ref "C77") (pin "1") (pinfunction "1_1") (pintype "bidirectional"))
      (node (ref "J7") (pin "1") (pinfunction "SIGNAL_1") (pintype "bidirectional"))
      (node (ref "L7") (pin "2") (pinfunction "2_2") (pintype "passive"))
      (node (ref "U3") (pin "41") (pinfunction "ANT_41") (pintype "passive"))
    )
    (net (code "204") (name "Net-(U2-ILIM)") (class "Default")
      (node (ref "R10") (pin "1") (pinfunction "1_1") (pintype "passive"))
      (node (ref "U2") (pin "12") (pinfunction "ILIM_12") (pintype "input"))
    )
    (net (code "205") (name "Net-(U2-ISET)") (class "Default")
      (node (ref "R12") (pin "1") (pinfunction "1_1") (pintype "passive"))
      (node (ref "U2") (pin "16") (pinfunction "ISET_16") (pintype "bidirectional"))
    )
    (net (code "206") (name "Net-(U2-TMR)") (class "Default")
      (node (ref "R11") (pin "1") (pinfunction "1_1") (pintype "passive"))
      (node (ref "U2") (pin "14") (pinfunction "TMR_14") (pintype "input"))
    )
    (net (code "207") (name "Net-(U2-TS)") (class "Default")
      (node (ref "R9") (pin "1") (pinfunction "1_1") (pintype "passive"))
      (node (ref "U2") (pin "1") (pinfunction "TS_1") (pintype "input"))
    )
    (net (code "208") (name "Net-(U2-~{CHG})") (class "Default")
      (node (ref "R1") (pin "1") (pinfunction "1_1") (pintype "passive"))
      (node (ref "U2") (pin "9") (pinfunction "~{CHG}_9") (pintype "output"))
    )
    (net (code "209") (name "Net-(U2-~{PGOOD})") (class "Default")
      (node (ref "R4") (pin "1") (pinfunction "1_1") (pintype "passive"))
      (node (ref "U2") (pin "7") (pinfunction "~{PGOOD}_7") (pintype "output"))
    )
    (net (code "210") (name "Net-(U3-SR_VLX)") (class "Default")
      (node (ref "L9") (pin "1") (pinfunction "1_1") (pintype "passive"))
      (node (ref "U3") (pin "34") (pinfunction "SR_VLX_34") (pintype "output"))
    )
    (net (code "211") (name "Net-(U3-VIN_LDO)") (class "Default")
      (node (ref "C74") (pin "1") (pinfunction "1_1") (pintype "passive"))
      (node (ref "C91") (pin "2") (pinfunction "2_2") (pintype "passive"))
      (node (ref "L9") (pin "2") (pinfunction "2_2") (pintype "passive"))
      (node (ref "U3") (pin "31") (pinfunction "VIN_LDO_31") (pintype "power_in"))
    )
    (net (code "212") (name "RAW") (class "Default")
      (node (ref "C1") (pin "2") (pinfunction "2_2") (pintype "passive"))
      (node (ref "C4") (pin "2") (pinfunction "2_2") (pintype "passive"))
      (node (ref "C6") (pin "1") (pinfunction "1_1") (pintype "passive"))
      (node (ref "D1") (pin "4") (pinfunction "ANODE_4") (pintype "passive"))
      (node (ref "D5") (pin "1") (pinfunction "1_1") (pintype "bidirectional"))
      (node (ref "IC1") (pin "2") (pinfunction "VOUT_1_2") (pintype "bidirectional"))
      (node (ref "IC1") (pin "7") (pinfunction "VOUT_2_7") (pintype "bidirectional"))
      (node (ref "IC2") (pin "3") (pinfunction "VIN_3") (pintype "bidirectional"))
      (node (ref "J3") (pin "2") (pinfunction "2_2") (pintype "passive"))
      (node (ref "Q1") (pin "1") (pinfunction "G_1") (pintype "bidirectional"))
      (node (ref "Q2") (pin "1") (pinfunction "G_1") (pintype "bidirectional"))
      (node (ref "Q3") (pin "1") (pinfunction "G_1") (pintype "bidirectional"))
      (node (ref "R22") (pin "2") (pinfunction "2_2") (pintype "passive"))
      (node (ref "R23") (pin "2") (pinfunction "2_2") (pintype "passive"))
      (node (ref "R3") (pin "2") (pinfunction "2_2") (pintype "passive"))
      (node (ref "U1") (pin "3") (pinfunction "EN_3") (pintype "bidirectional"))
      (node (ref "U1") (pin "4") (pinfunction "VIN_4") (pintype "bidirectional"))
    )
    (net (code "213") (name "VBUS") (class "Default")
      (node (ref "C88") (pin "1") (pinfunction "1_1") (pintype "passive"))
      (node (ref "C9") (pin "2") (pinfunction "2_2") (pintype "passive"))
      (node (ref "C95") (pin "2") (pinfunction "2_2") (pintype "passive"))
      (node (ref "FL1") (pin "1") (pinfunction "VBUS_1") (pintype "bidirectional"))
      (node (ref "IC8") (pin "N6") (pinfunction "USB_OTG1_VBUS_N6") (pintype "bidirectional"))
      (node (ref "L1") (pin "2") (pinfunction "2_2") (pintype "passive"))
      (node (ref "U2") (pin "13") (pinfunction "IN_13") (pintype "input"))
    )
    (net (code "214") (name "VCC") (class "Default")
      (node (ref "C108") (pin "2") (pinfunction "2_2") (pintype "passive"))
      (node (ref "C109") (pin "1") (pinfunction "1_1") (pintype "passive"))
      (node (ref "C11") (pin "2") (pinfunction "2_2") (pintype "passive"))
      (node (ref "C12") (pin "1") (pinfunction "1_1") (pintype "passive"))
      (node (ref "C13") (pin "1") (pinfunction "1_1") (pintype "passive"))
      (node (ref "C14") (pin "1") (pinfunction "1_1") (pintype "passive"))
      (node (ref "C15") (pin "1") (pinfunction "1_1") (pintype "passive"))
      (node (ref "C16") (pin "1") (pinfunction "1_1") (pintype "passive"))
      (node (ref "C17") (pin "2") (pinfunction "2_2") (pintype "passive"))
      (node (ref "C18") (pin "2") (pinfunction "2_2") (pintype "passive"))
      (node (ref "C19") (pin "1") (pinfunction "1_1") (pintype "passive"))
      (node (ref "C20") (pin "1") (pinfunction "1_1") (pintype "passive"))
      (node (ref "C21") (pin "2") (pinfunction "2_2") (pintype "passive"))
      (node (ref "C22") (pin "1") (pinfunction "1_1") (pintype "passive"))
      (node (ref "C23") (pin "2") (pinfunction "2_2") (pintype "passive"))
      (node (ref "C24") (pin "1") (pinfunction "1_1") (pintype "passive"))
      (node (ref "C25") (pin "2") (pinfunction "2_2") (pintype "passive"))
      (node (ref "C26") (pin "1") (pinfunction "1_1") (pintype "passive"))
      (node (ref "C27") (pin "2") (pinfunction "2_2") (pintype "passive"))
      (node (ref "C28") (pin "1") (pinfunction "1_1") (pintype "passive"))
      (node (ref "C29") (pin "1") (pinfunction "1_1") (pintype "passive"))
      (node (ref "C30") (pin "1") (pinfunction "1_1") (pintype "passive"))
      (node (ref "C31") (pin "2") (pinfunction "2_2") (pintype "passive"))
      (node (ref "C32") (pin "1") (pinfunction "1_1") (pintype "passive"))
      (node (ref "C33") (pin "2") (pinfunction "2_2") (pintype "passive"))
      (node (ref "C35") (pin "2") (pinfunction "2_2") (pintype "passive"))
      (node (ref "C36") (pin "1") (pinfunction "1_1") (pintype "passive"))
      (node (ref "C37") (pin "1") (pinfunction "1_1") (pintype "passive"))
      (node (ref "C39") (pin "2") (pinfunction "2_2") (pintype "passive"))
      (node (ref "C40") (pin "2") (pinfunction "2_2") (pintype "passive"))
      (node (ref "C41") (pin "2") (pinfunction "2_2") (pintype "passive"))
      (node (ref "C42") (pin "2") (pinfunction "2_2") (pintype "passive"))
      (node (ref "C43") (pin "1") (pinfunction "1_1") (pintype "passive"))
      (node (ref "C44") (pin "2") (pinfunction "2_2") (pintype "passive"))
      (node (ref "C50") (pin "1") (pinfunction "1_1") (pintype "passive"))
      (node (ref "C53") (pin "1") (pinfunction "1_1") (pintype "passive"))
      (node (ref "C54") (pin "1") (pinfunction "1_1") (pintype "passive"))
      (node (ref "C55") (pin "1") (pinfunction "1_1") (pintype "passive"))
      (node (ref "C56") (pin "1") (pinfunction "1_1") (pintype "passive"))
      (node (ref "C57") (pin "2") (pinfunction "2_2") (pintype "passive"))
      (node (ref "C58") (pin "2") (pinfunction "2_2") (pintype "passive"))
      (node (ref "C64") (pin "1") (pinfunction "1_1") (pintype "passive"))
      (node (ref "C66") (pin "2") (pinfunction "2_2") (pintype "passive"))
      (node (ref "C67") (pin "1") (pinfunction "1_1") (pintype "passive"))
      (node (ref "C68") (pin "2") (pinfunction "2_2") (pintype "passive"))
      (node (ref "C7") (pin "1") (pinfunction "1_1") (pintype "passive"))
      (node (ref "C75") (pin "1") (pinfunction "1_1") (pintype "passive"))
      (node (ref "C76") (pin "1") (pinfunction "1_1") (pintype "passive"))
      (node (ref "C86") (pin "2") (pinfunction "2_2") (pintype "passive"))
      (node (ref "C89") (pin "1") (pinfunction "1_1") (pintype "passive"))
      (node (ref "C90") (pin "2") (pinfunction "2_2") (pintype "passive"))
      (node (ref "C92") (pin "2") (pinfunction "2_2") (pintype "passive"))
      (node (ref "C93") (pin "2") (pinfunction "2_2") (pintype "passive"))
      (node (ref "C96") (pin "1") (pinfunction "1_1") (pintype "passive"))
      (node (ref "C99") (pin "2") (pinfunction "2_2") (pintype "passive"))
      (node (ref "D10") (pin "1") (pinfunction "1_1") (pintype "bidirectional"))
      (node (ref "D3") (pin "4") (pinfunction "ANODE_4") (pintype "passive"))
      (node (ref "D4") (pin "1") (pinfunction "1_1") (pintype "bidirectional"))
      (node (ref "D6") (pin "1") (pinfunction "1_1") (pintype "bidirectional"))
      (node (ref "IC2") (pin "6") (pinfunction "OUT_6") (pintype "bidirectional"))
      (node (ref "IC3") (pin "A7") (pinfunction "VDDQ_1_A7") (pintype "bidirectional"))
      (node (ref "IC3") (pin "A9") (pinfunction "VDD_1_A9") (pintype "bidirectional"))
      (node (ref "IC3") (pin "B3") (pinfunction "VDDQ_2_B3") (pintype "bidirectional"))
      (node (ref "IC3") (pin "C7") (pinfunction "VDDQ_3_C7") (pintype "bidirectional"))
      (node (ref "IC3") (pin "D3") (pinfunction "VDDQ_4_D3") (pintype "bidirectional"))
      (node (ref "IC3") (pin "E7") (pinfunction "VDD_2_E7") (pintype "bidirectional"))
      (node (ref "IC3") (pin "J9") (pinfunction "VDD_3_J9") (pintype "bidirectional"))
      (node (ref "IC4") (pin "8") (pinfunction "VCC_8") (pintype "bidirectional"))
      (node (ref "IC5") (pin "8") (pinfunction "VCC_8") (pintype "bidirectional"))
      (node (ref "IC6") (pin "8") (pinfunction "VCC_8") (pintype "bidirectional"))
      (node (ref "IC7") (pin "6") (pinfunction "VDD_6") (pintype "bidirectional"))
      (node (ref "IC8") (pin "E6") (pinfunction "NVCC_EMC_1_E6") (pintype "bidirectional"))
      (node (ref "IC8") (pin "E9") (pinfunction "NVCC_GPIO_1_E9") (pintype "bidirectional"))
      (node (ref "IC8") (pin "F10") (pinfunction "NVCC_GPIO_2_F10") (pintype "bidirectional"))
      (node (ref "IC8") (pin "F5") (pinfunction "NVCC_EMC_2_F5") (pintype "bidirectional"))
      (node (ref "IC8") (pin "J10") (pinfunction "NVCC_GPIO_3_J10") (pintype "bidirectional"))
      (node (ref "IC8") (pin "J6") (pinfunction "NVCC_SD0_J6") (pintype "bidirectional"))
      (node (ref "IC8") (pin "K4") (pinfunction "DCDC_IN_Q_K4") (pintype "bidirectional"))
      (node (ref "IC8") (pin "K5") (pinfunction "NVCC_SD1_K5") (pintype "bidirectional"))
      (node (ref "IC8") (pin "L1") (pinfunction "DCDC_IN_1_L1") (pintype "bidirectional"))
      (node (ref "IC8") (pin "L2") (pinfunction "DCDC_IN_2_L2") (pintype "bidirectional"))
      (node (ref "IC8") (pin "P12") (pinfunction "VDD_HIGH_IN_P12") (pintype "bidirectional"))
      (node (ref "IC9") (pin "14") (pinfunction "VDDIO_14") (pintype "bidirectional"))
      (node (ref "J2") (pin "1") (pinfunction "1_1") (pintype "passive"))
      (node (ref "J4") (pin "10") (pinfunction "10_10") (pintype "bidirectional"))
      (node (ref "J4") (pin "2") (pinfunction "2_2") (pintype "bidirectional"))
      (node (ref "J4") (pin "20") (pinfunction "20_20") (pintype "bidirectional"))
      (node (ref "J4") (pin "30") (pinfunction "30_30") (pintype "bidirectional"))
      (node (ref "J4") (pin "36") (pinfunction "36_36") (pintype "bidirectional"))
      (node (ref "J5") (pin "P$4") (pinfunction "VDD_P$4") (pintype "power_in"))
      (node (ref "J8") (pin "1") (pinfunction "1_1") (pintype "passive"))
      (node (ref "L2") (pin "2") (pinfunction "2_2") (pintype "passive"))
      (node (ref "L4") (pin "2") (pinfunction "2_2") (pintype "passive"))
      (node (ref "L6") (pin "2") (pinfunction "2_2") (pintype "passive"))
      (node (ref "L8") (pin "2") (pinfunction "2_2") (pintype "passive"))
      (node (ref "Q4") (pin "1") (pinfunction "G_1") (pintype "bidirectional"))
      (node (ref "Q5") (pin "1") (pinfunction "G_1") (pintype "bidirectional"))
      (node (ref "R13") (pin "1") (pinfunction "1_1") (pintype "passive"))
      (node (ref "R14") (pin "1") (pinfunction "1_1") (pintype "passive"))
      (node (ref "R15") (pin "2") (pinfunction "2_2") (pintype "passive"))
      (node (ref "R16") (pin "2") (pinfunction "2_2") (pintype "passive"))
      (node (ref "R17") (pin "2") (pinfunction "2_2") (pintype "passive"))
      (node (ref "R18") (pin "1") (pinfunction "1_1") (pintype "passive"))
      (node (ref "R2") (pin "2") (pinfunction "2_2") (pintype "passive"))
      (node (ref "R24") (pin "2") (pinfunction "2_2") (pintype "passive"))
      (node (ref "R25") (pin "2") (pinfunction "2_2") (pintype "passive"))
      (node (ref "R26") (pin "2") (pinfunction "2_2") (pintype "passive"))
      (node (ref "R28") (pin "2") (pinfunction "2_2") (pintype "passive"))
      (node (ref "R29") (pin "2") (pinfunction "2_2") (pintype "passive"))
      (node (ref "R30") (pin "2") (pinfunction "2_2") (pintype "passive"))
      (node (ref "R31") (pin "2") (pinfunction "2_2") (pintype "passive"))
      (node (ref "R32") (pin "2") (pinfunction "2_2") (pintype "passive"))
      (node (ref "R33") (pin "1") (pinfunction "1_1") (pintype "passive"))
      (node (ref "R34") (pin "2") (pinfunction "2_2") (pintype "passive"))
      (node (ref "R36") (pin "2") (pinfunction "2_2") (pintype "passive"))
      (node (ref "R39") (pin "2") (pinfunction "2_2") (pintype "passive"))
      (node (ref "RN1") (pin "1") (pinfunction "1_1") (pintype "bidirectional"))
      (node (ref "RN1") (pin "2") (pinfunction "2_2") (pintype "bidirectional"))
      (node (ref "RN1") (pin "3") (pinfunction "3_3") (pintype "bidirectional"))
      (node (ref "RN1") (pin "4") (pinfunction "4_4") (pintype "bidirectional"))
      (node (ref "RN1") (pin "5") (pinfunction "5_5") (pintype "bidirectional"))
      (node (ref "RN1") (pin "6") (pinfunction "6_6") (pintype "bidirectional"))
      (node (ref "RN1") (pin "7") (pinfunction "7_7") (pintype "bidirectional"))
      (node (ref "RN1") (pin "8") (pinfunction "8_8") (pintype "bidirectional"))
      (node (ref "RN2") (pin "1") (pinfunction "1_1") (pintype "bidirectional"))
      (node (ref "RN2") (pin "2") (pinfunction "2_2") (pintype "bidirectional"))
      (node (ref "RN2") (pin "3") (pinfunction "3_3") (pintype "bidirectional"))
      (node (ref "RN2") (pin "4") (pinfunction "4_4") (pintype "bidirectional"))
      (node (ref "RN2") (pin "5") (pinfunction "5_5") (pintype "bidirectional"))
      (node (ref "RN2") (pin "6") (pinfunction "6_6") (pintype "bidirectional"))
      (node (ref "RN2") (pin "7") (pinfunction "7_7") (pintype "bidirectional"))
      (node (ref "RN2") (pin "8") (pinfunction "8_8") (pintype "bidirectional"))
      (node (ref "U3") (pin "30") (pinfunction "VBAT_30") (pintype "power_in"))
      (node (ref "U3") (pin "36") (pinfunction "VIO_36") (pintype "power_in"))
    )
    (net (code "215") (name "VIN") (class "Default")
      (node (ref "D7") (pin "1") (pinfunction "1_1") (pintype "bidirectional"))
      (node (ref "J6") (pin "2") (pinfunction "2_2") (pintype "passive"))
      (node (ref "Q6") (pin "3") (pinfunction "D_3") (pintype "bidirectional"))
    )
    (net (code "216") (name "V_BATT") (class "Default")
      (node (ref "C10") (pin "2") (pinfunction "2_2") (pintype "passive"))
      (node (ref "C3") (pin "2") (pinfunction "2_2") (pintype "passive"))
      (node (ref "IC1") (pin "3") (pinfunction "VIN1_3") (pintype "bidirectional"))
      (node (ref "U2") (pin "10") (pinfunction "OUT_10_10") (pintype "output"))
      (node (ref "U2") (pin "11") (pinfunction "OUT_11_11") (pintype "output"))
      (node (ref "U2") (pin "5") (pinfunction "EN2_5") (pintype "input"))
    )
    (net (code "217") (name "unconnected-(ANT1-NC-Pad2)") (class "Default")
      (node (ref "ANT1") (pin "2") (pinfunction "NC_2") (pintype "no_connect"))
    )
    (net (code "218") (name "unconnected-(FL1-Pad9)") (class "Default")
      (node (ref "FL1") (pin "9") (pinfunction "9_9") (pintype "bidirectional"))
    )
    (net (code "219") (name "unconnected-(FL1-Pad10)") (class "Default")
      (node (ref "FL1") (pin "10") (pinfunction "10_10") (pintype "bidirectional"))
    )
    (net (code "220") (name "unconnected-(FL1-Pad11)") (class "Default")
      (node (ref "FL1") (pin "11") (pinfunction "11_11") (pintype "bidirectional"))
    )
    (net (code "221") (name "unconnected-(FL1-Pad12)") (class "Default")
      (node (ref "FL1") (pin "12") (pinfunction "12_12") (pintype "bidirectional"))
    )
    (net (code "222") (name "unconnected-(H1-MOUNT-PadB2,8)") (class "Default")
      (node (ref "H1") (pin "B2,8") (pinfunction "MOUNT_B2,8") (pintype "passive"))
    )
    (net (code "223") (name "unconnected-(H2-MOUNT-PadB2,8)") (class "Default")
      (node (ref "H2") (pin "B2,8") (pinfunction "MOUNT_B2,8") (pintype "passive"))
    )
    (net (code "224") (name "unconnected-(IC3-NC-PadE2)") (class "Default")
      (node (ref "IC3") (pin "E2") (pinfunction "NC_E2") (pintype "no_connect"))
    )
    (net (code "225") (name "unconnected-(IC4-NC_1-Pad1)") (class "Default")
      (node (ref "IC4") (pin "1") (pinfunction "NC_1_1") (pintype "bidirectional"))
    )
    (net (code "226") (name "unconnected-(IC4-NC_2-Pad2)") (class "Default")
      (node (ref "IC4") (pin "2") (pinfunction "NC_2_2") (pintype "bidirectional"))
    )
    (net (code "227") (name "unconnected-(IC4-NC_3-Pad3)") (class "Default")
      (node (ref "IC4") (pin "3") (pinfunction "NC_3_3") (pintype "bidirectional"))
    )
    (net (code "228") (name "unconnected-(IC4-NC_4-Pad7)") (class "Default")
      (node (ref "IC4") (pin "7") (pinfunction "NC_4_7") (pintype "bidirectional"))
    )
    (net (code "229") (name "unconnected-(IC7-NC-Pad2)") (class "Default")
      (node (ref "IC7") (pin "2") (pinfunction "NC_2") (pintype "no_connect"))
    )
    (net (code "230") (name "unconnected-(IC8-CCM_CLK1_N-PadP13)") (class "Default")
      (node (ref "IC8") (pin "P13") (pinfunction "CCM_CLK1_N_P13") (pintype "bidirectional"))
    )
    (net (code "231") (name "unconnected-(IC8-CCM_CLK1_P-PadN13)") (class "Default")
      (node (ref "IC8") (pin "N13") (pinfunction "CCM_CLK1_P_N13") (pintype "bidirectional"))
    )
    (net (code "232") (name "unconnected-(IC8-GPANAIO-PadN10)") (class "Default")
      (node (ref "IC8") (pin "N10") (pinfunction "GPANAIO_N10") (pintype "bidirectional"))
    )
    (net (code "233") (name "unconnected-(IC8-USB_OTG1_CHD_B-PadN12)") (class "Default")
      (node (ref "IC8") (pin "N12") (pinfunction "USB_OTG1_CHD_B_N12") (pintype "bidirectional"))
    )
    (net (code "234") (name "unconnected-(IC8-USB_OTG2_DN-PadN7)") (class "Default")
      (node (ref "IC8") (pin "N7") (pinfunction "USB_OTG2_DN_N7") (pintype "bidirectional"))
    )
    (net (code "235") (name "unconnected-(IC8-USB_OTG2_DP-PadP7)") (class "Default")
      (node (ref "IC8") (pin "P7") (pinfunction "USB_OTG2_DP_P7") (pintype "bidirectional"))
    )
    (net (code "236") (name "unconnected-(IC8-USB_OTG2_VBUS-PadP6)") (class "Default")
      (node (ref "IC8") (pin "P6") (pinfunction "USB_OTG2_VBUS_P6") (pintype "bidirectional"))
    )
    (net (code "237") (name "unconnected-(IC9-REF_CLK-Pad16)") (class "Default")
      (node (ref "IC9") (pin "16") (pinfunction "REF_CLK_16") (pintype "bidirectional"))
    )
    (net (code "238") (name "unconnected-(IC9-XO-Pad7)") (class "Default")
      (node (ref "IC9") (pin "7") (pinfunction "XO_7") (pintype "bidirectional"))
    )
    (net (code "239") (name "unconnected-(J1-SBU1-PadA8)") (class "Default")
      (node (ref "J1") (pin "A8") (pinfunction "SBU1_A8") (pintype "bidirectional"))
    )
    (net (code "240") (name "unconnected-(J1-SBU2-PadB8)") (class "Default")
      (node (ref "J1") (pin "B8") (pinfunction "SBU2_B8") (pintype "bidirectional"))
    )
    (net (code "241") (name "unconnected-(J4-Pad1)") (class "Default")
      (node (ref "J4") (pin "1") (pinfunction "1_1") (pintype "bidirectional"))
    )
    (net (code "242") (name "unconnected-(J4-Pad3)") (class "Default")
      (node (ref "J4") (pin "3") (pinfunction "3_3") (pintype "bidirectional"))
    )
    (net (code "243") (name "unconnected-(J4-Pad6)") (class "Default")
      (node (ref "J4") (pin "6") (pinfunction "6_6") (pintype "bidirectional"))
    )
    (net (code "244") (name "unconnected-(J4-Pad7)") (class "Default")
      (node (ref "J4") (pin "7") (pinfunction "7_7") (pintype "bidirectional"))
    )
    (net (code "245") (name "unconnected-(J4-Pad8)") (class "Default")
      (node (ref "J4") (pin "8") (pinfunction "8_8") (pintype "bidirectional"))
    )
    (net (code "246") (name "unconnected-(J4-Pad9)") (class "Default")
      (node (ref "J4") (pin "9") (pinfunction "9_9") (pintype "bidirectional"))
    )
    (net (code "247") (name "unconnected-(J8-Pad7)") (class "Default")
      (node (ref "J8") (pin "7") (pinfunction "7_7") (pintype "passive"))
    )
    (net (code "248") (name "unconnected-(RN1-Pad15)") (class "Default")
      (node (ref "RN1") (pin "15") (pinfunction "15_15") (pintype "bidirectional"))
    )
    (net (code "249") (name "unconnected-(RN1-Pad16)") (class "Default")
      (node (ref "RN1") (pin "16") (pinfunction "16_16") (pintype "bidirectional"))
    )
    (net (code "250") (name "unconnected-(RN2-Pad9)") (class "Default")
      (node (ref "RN2") (pin "9") (pinfunction "9_9") (pintype "bidirectional"))
    )
    (net (code "251") (name "unconnected-(RN2-Pad10)") (class "Default")
      (node (ref "RN2") (pin "10") (pinfunction "10_10") (pintype "bidirectional"))
    )
    (net (code "252") (name "unconnected-(RN2-Pad11)") (class "Default")
      (node (ref "RN2") (pin "11") (pinfunction "11_11") (pintype "bidirectional"))
    )
    (net (code "253") (name "unconnected-(U3-BT_GPIO_3-Pad6)") (class "Default")
      (node (ref "U3") (pin "6") (pinfunction "BT_GPIO_3_6") (pintype "bidirectional"))
    )
    (net (code "254") (name "unconnected-(U3-BT_GPIO_4-Pad7)") (class "Default")
      (node (ref "U3") (pin "7") (pinfunction "BT_GPIO_4_7") (pintype "bidirectional"))
    )
    (net (code "255") (name "unconnected-(U3-BT_GPIO_5-Pad13)") (class "Default")
      (node (ref "U3") (pin "13") (pinfunction "BT_GPIO_5_13") (pintype "bidirectional"))
    )
    (net (code "256") (name "unconnected-(U3-BT_I2S_DO-Pad16)") (class "Default")
      (node (ref "U3") (pin "16") (pinfunction "BT_I2S_DO_16") (pintype "bidirectional"))
    )
    (net (code "257") (name "unconnected-(U3-BT_PCM_CLK-Pad11)") (class "Default")
      (node (ref "U3") (pin "11") (pinfunction "BT_PCM_CLK_11") (pintype "bidirectional"))
    )
    (net (code "258") (name "unconnected-(U3-BT_PCM_IN-Pad9)") (class "Default")
      (node (ref "U3") (pin "9") (pinfunction "BT_PCM_IN_9") (pintype "input"))
    )
    (net (code "259") (name "unconnected-(U3-BT_PCM_OUT-Pad10)") (class "Default")
      (node (ref "U3") (pin "10") (pinfunction "BT_PCM_OUT_10") (pintype "output"))
    )
    (net (code "260") (name "unconnected-(U3-BT_PCM_SYNC-Pad8)") (class "Default")
      (node (ref "U3") (pin "8") (pinfunction "BT_PCM_SYNC_8") (pintype "bidirectional"))
    )
    (net (code "261") (name "unconnected-(U3-WL_GPIO_1-Pad18)") (class "Default")
      (node (ref "U3") (pin "18") (pinfunction "WL_GPIO_1_18") (pintype "bidirectional"))
    )
    (net (code "262") (name "unconnected-(U3-WL_GPIO_2-Pad17)") (class "Default")
      (node (ref "U3") (pin "17") (pinfunction "WL_GPIO_2_17") (pintype "bidirectional"))
    )
    (net (code "263") (name "unconnected-(U3-WL_GPIO_4-Pad15)") (class "Default")
      (node (ref "U3") (pin "15") (pinfunction "WL_GPIO_4_15") (pintype "bidirectional"))
    )
    (net (code "264") (name "unconnected-(U3-~{BT_UART_RTS_N}-Pad5)") (class "Default")
      (node (ref "U3") (pin "5") (pinfunction "~{BT_UART_RTS_N}_5") (pintype "output"))
    )
  )
)
